# BM8L.net
KiCad netlist of a schematic drawn in EAGLE
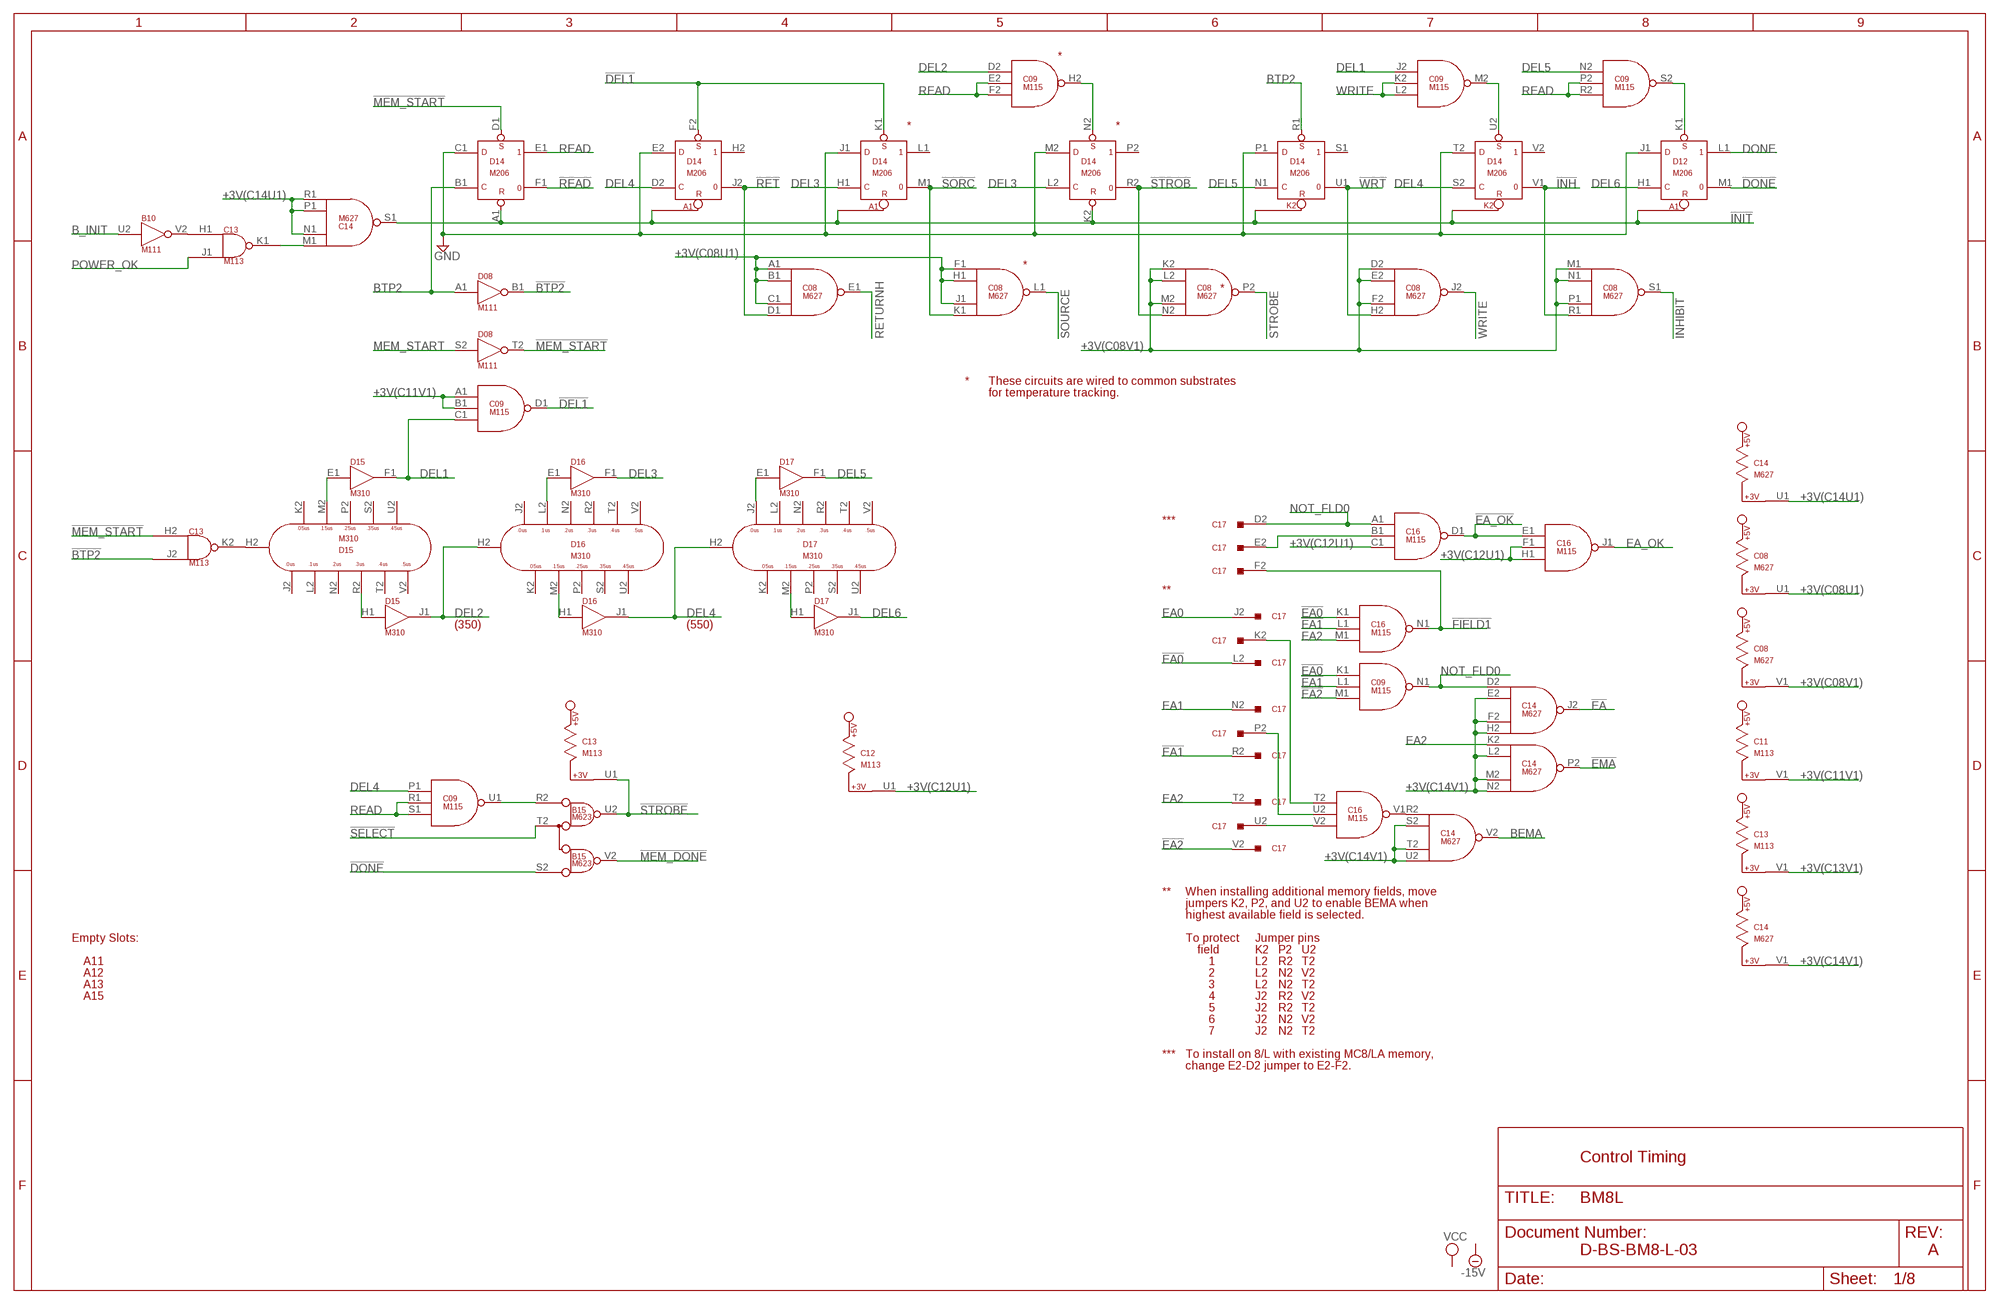
[diagram p0: schematic, sheet 1]
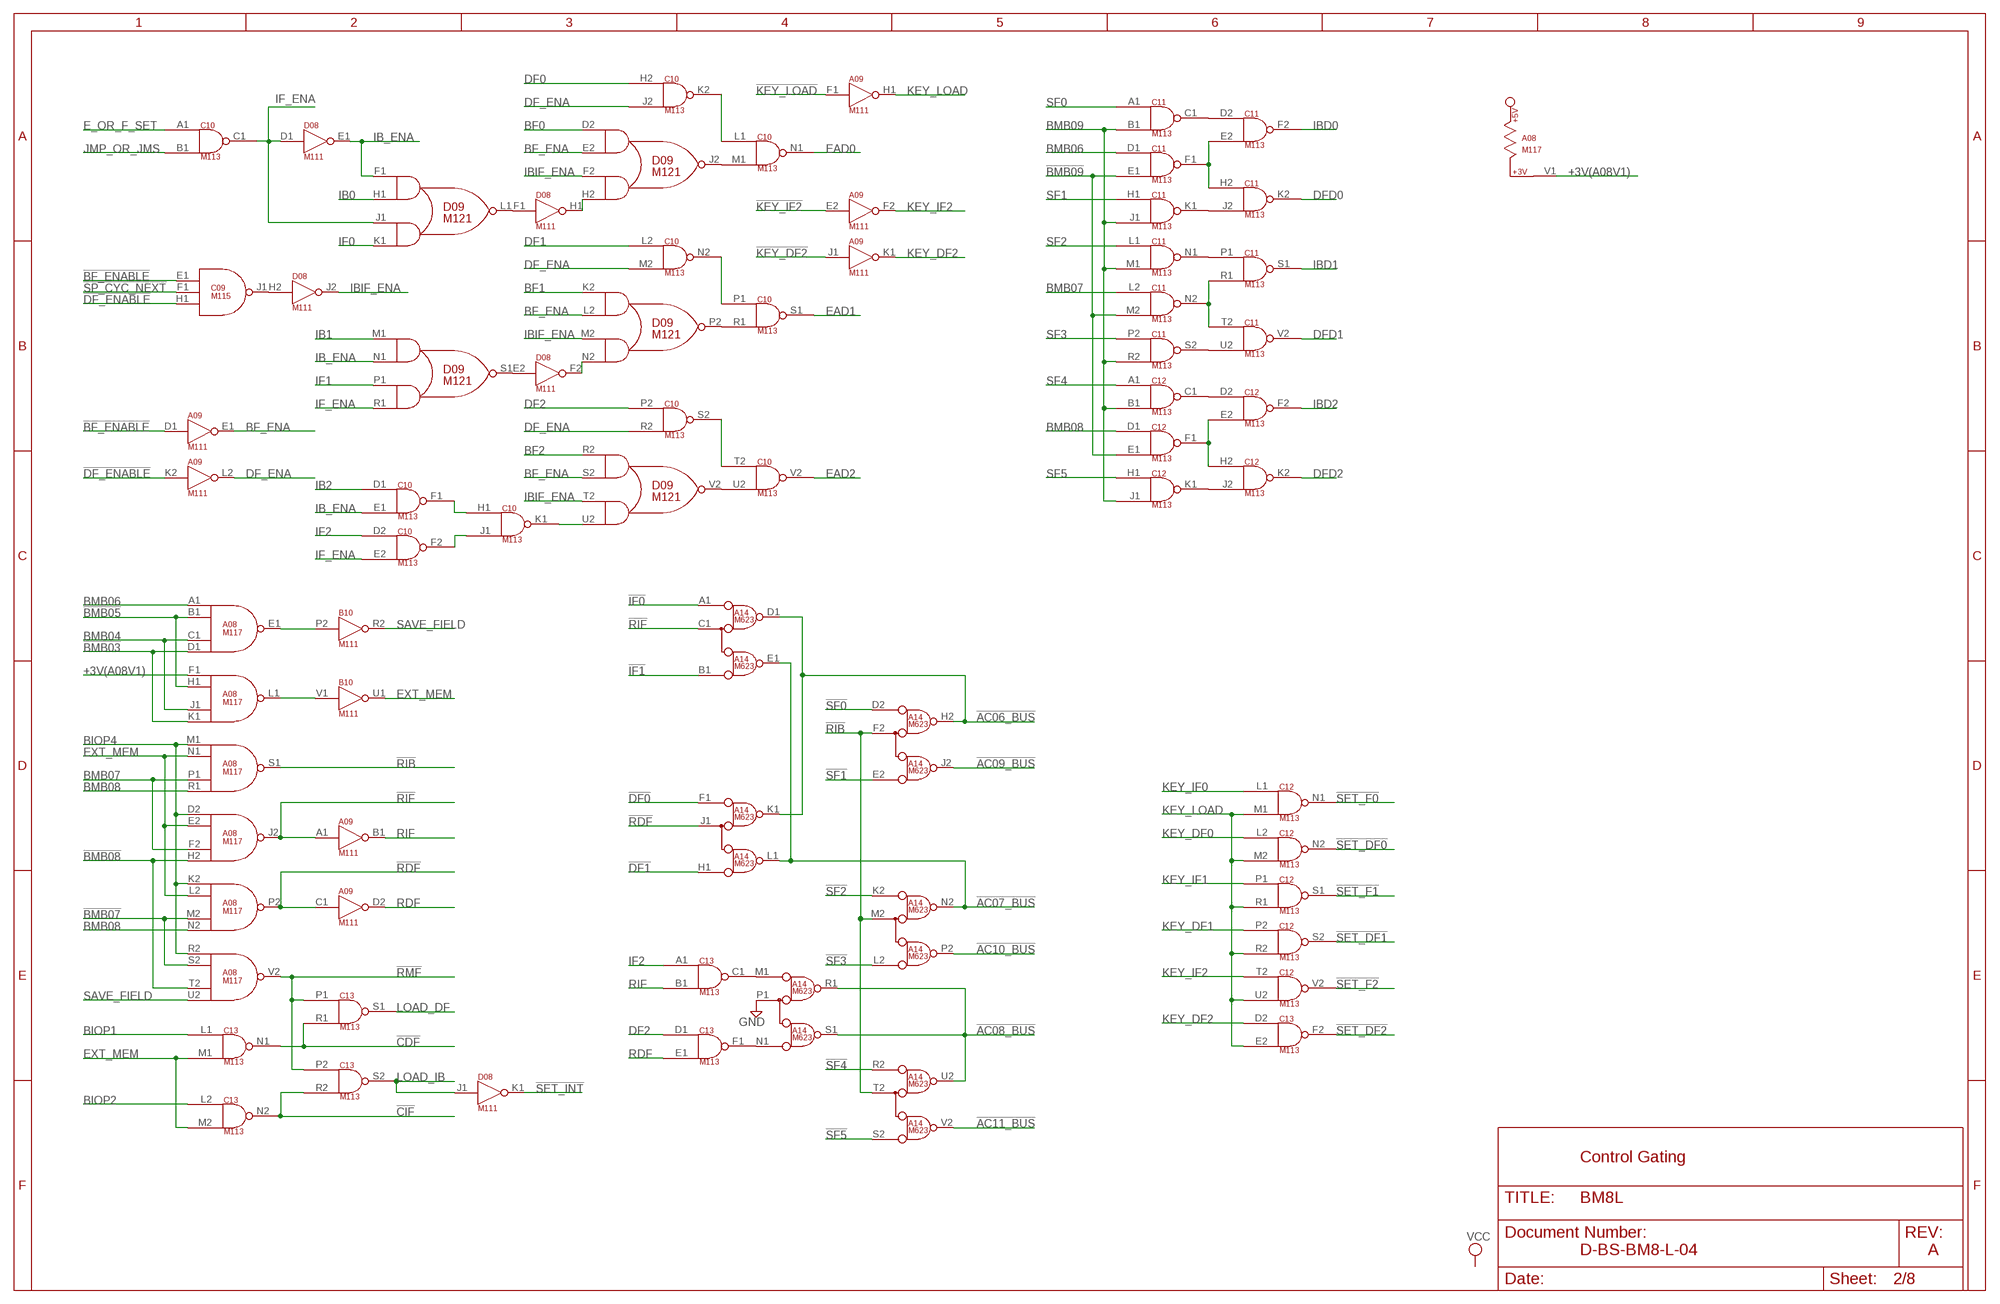
[diagram p1: schematic, sheet 2]
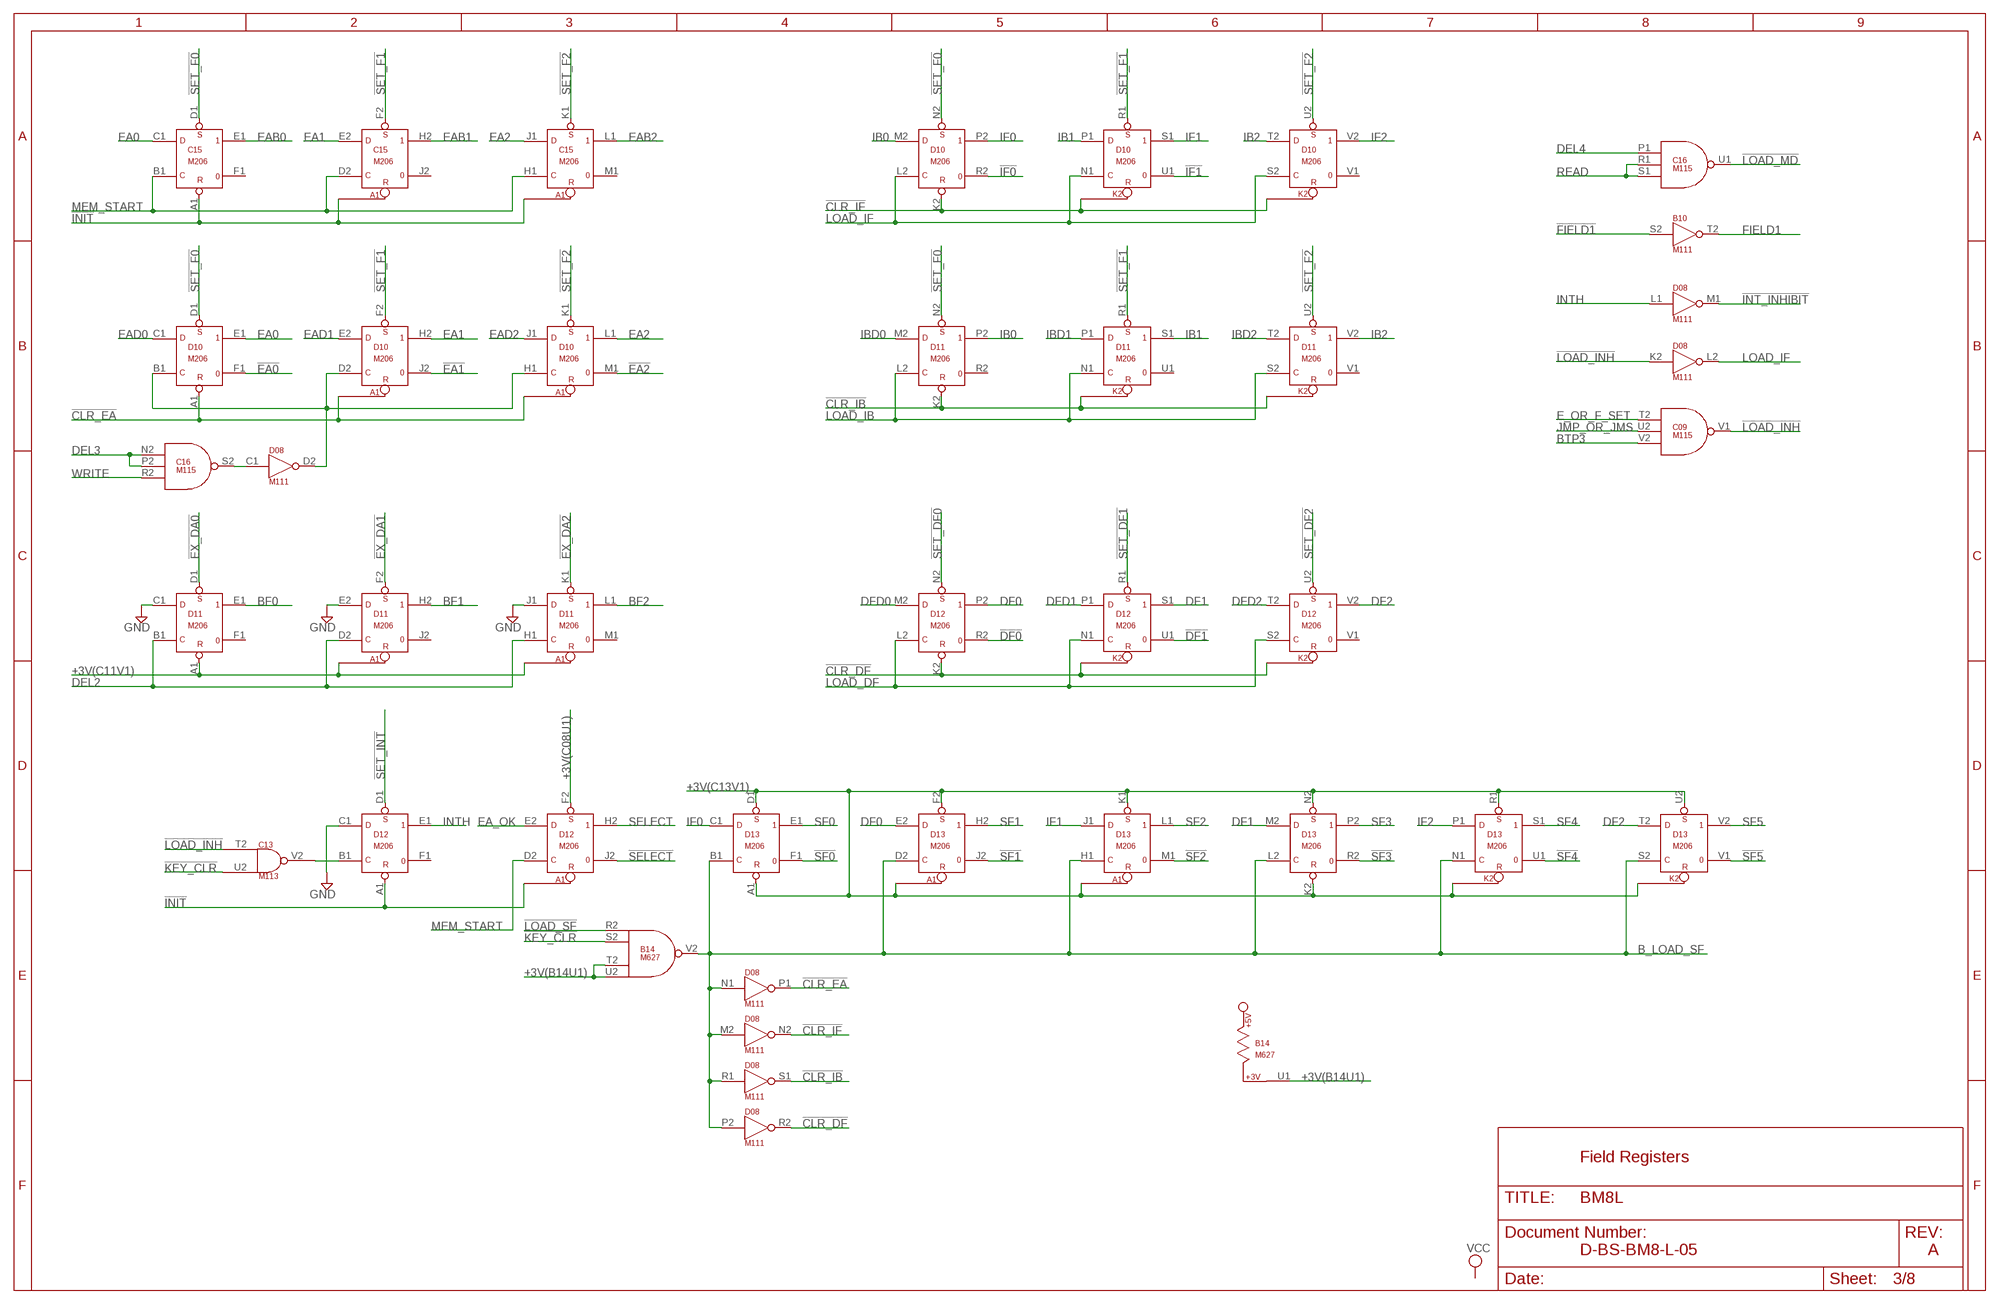
[diagram p2: schematic, sheet 3]
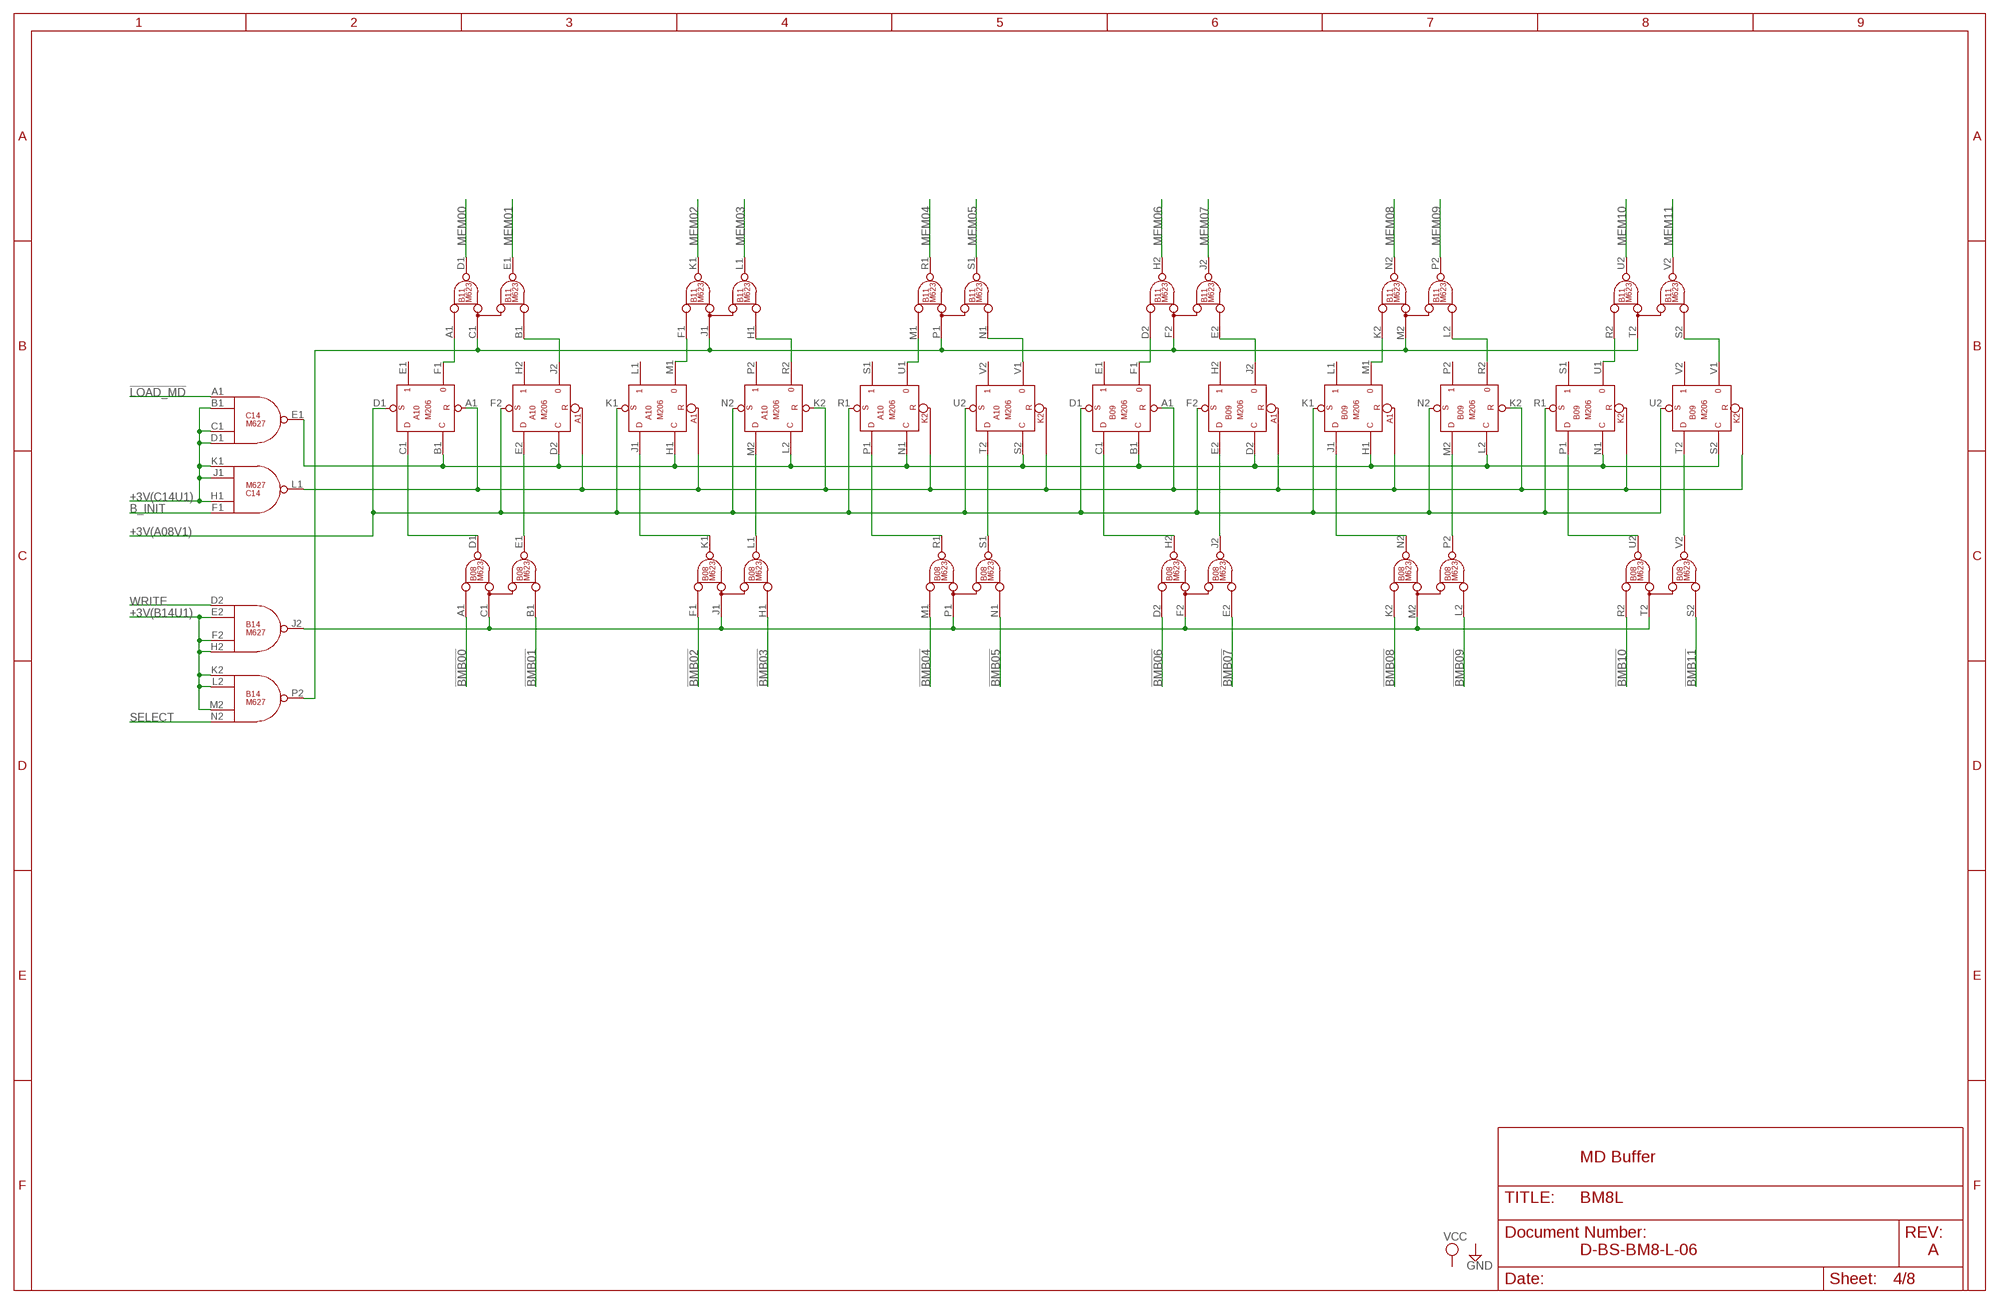
[diagram p3: schematic, sheet 4]
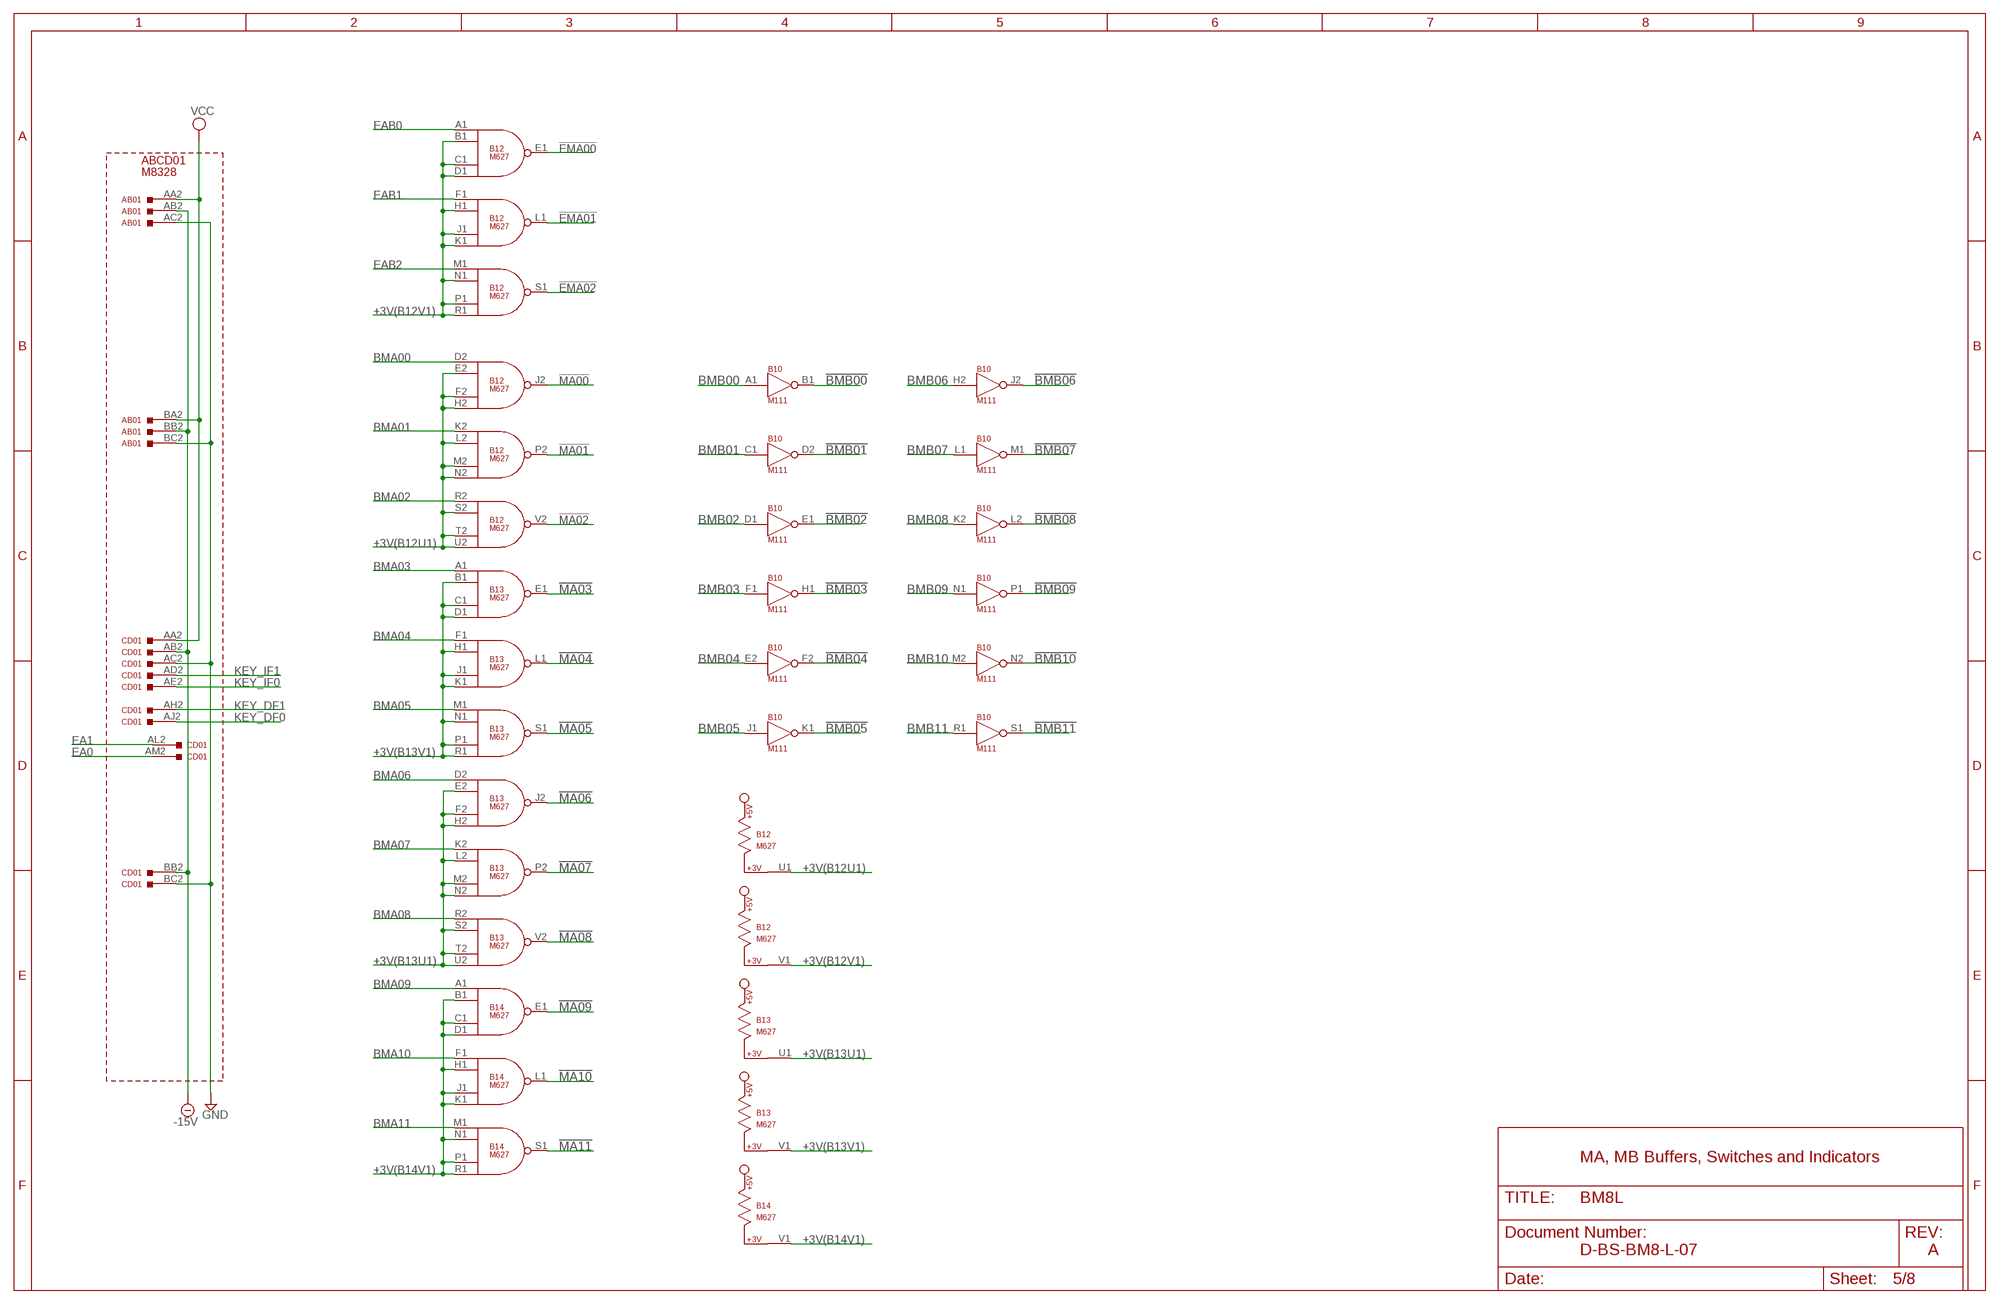
[diagram p4: schematic, sheet 5]
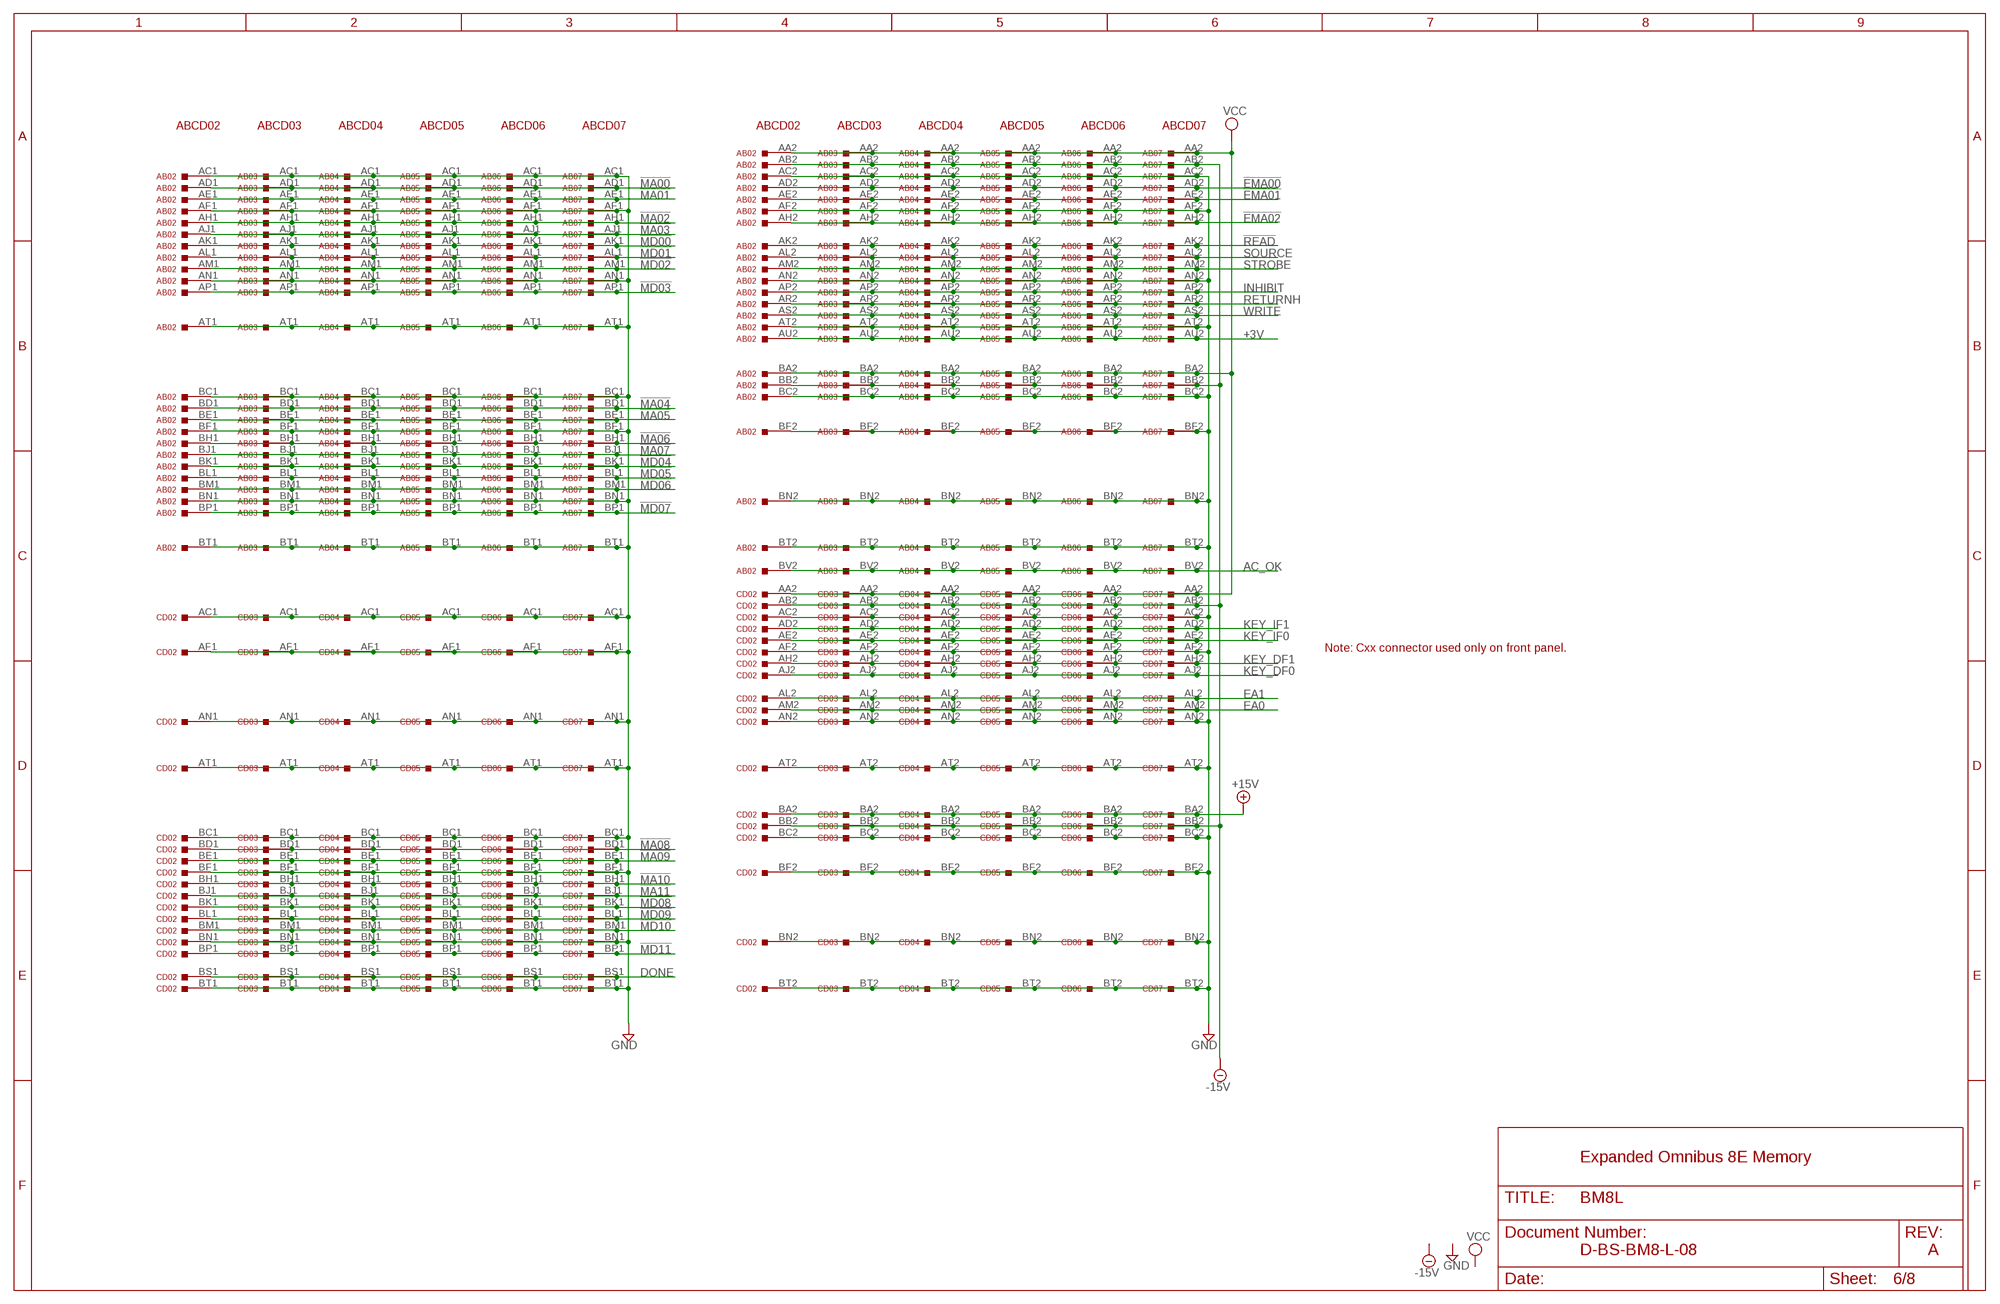
[diagram p5: schematic, sheet 6]
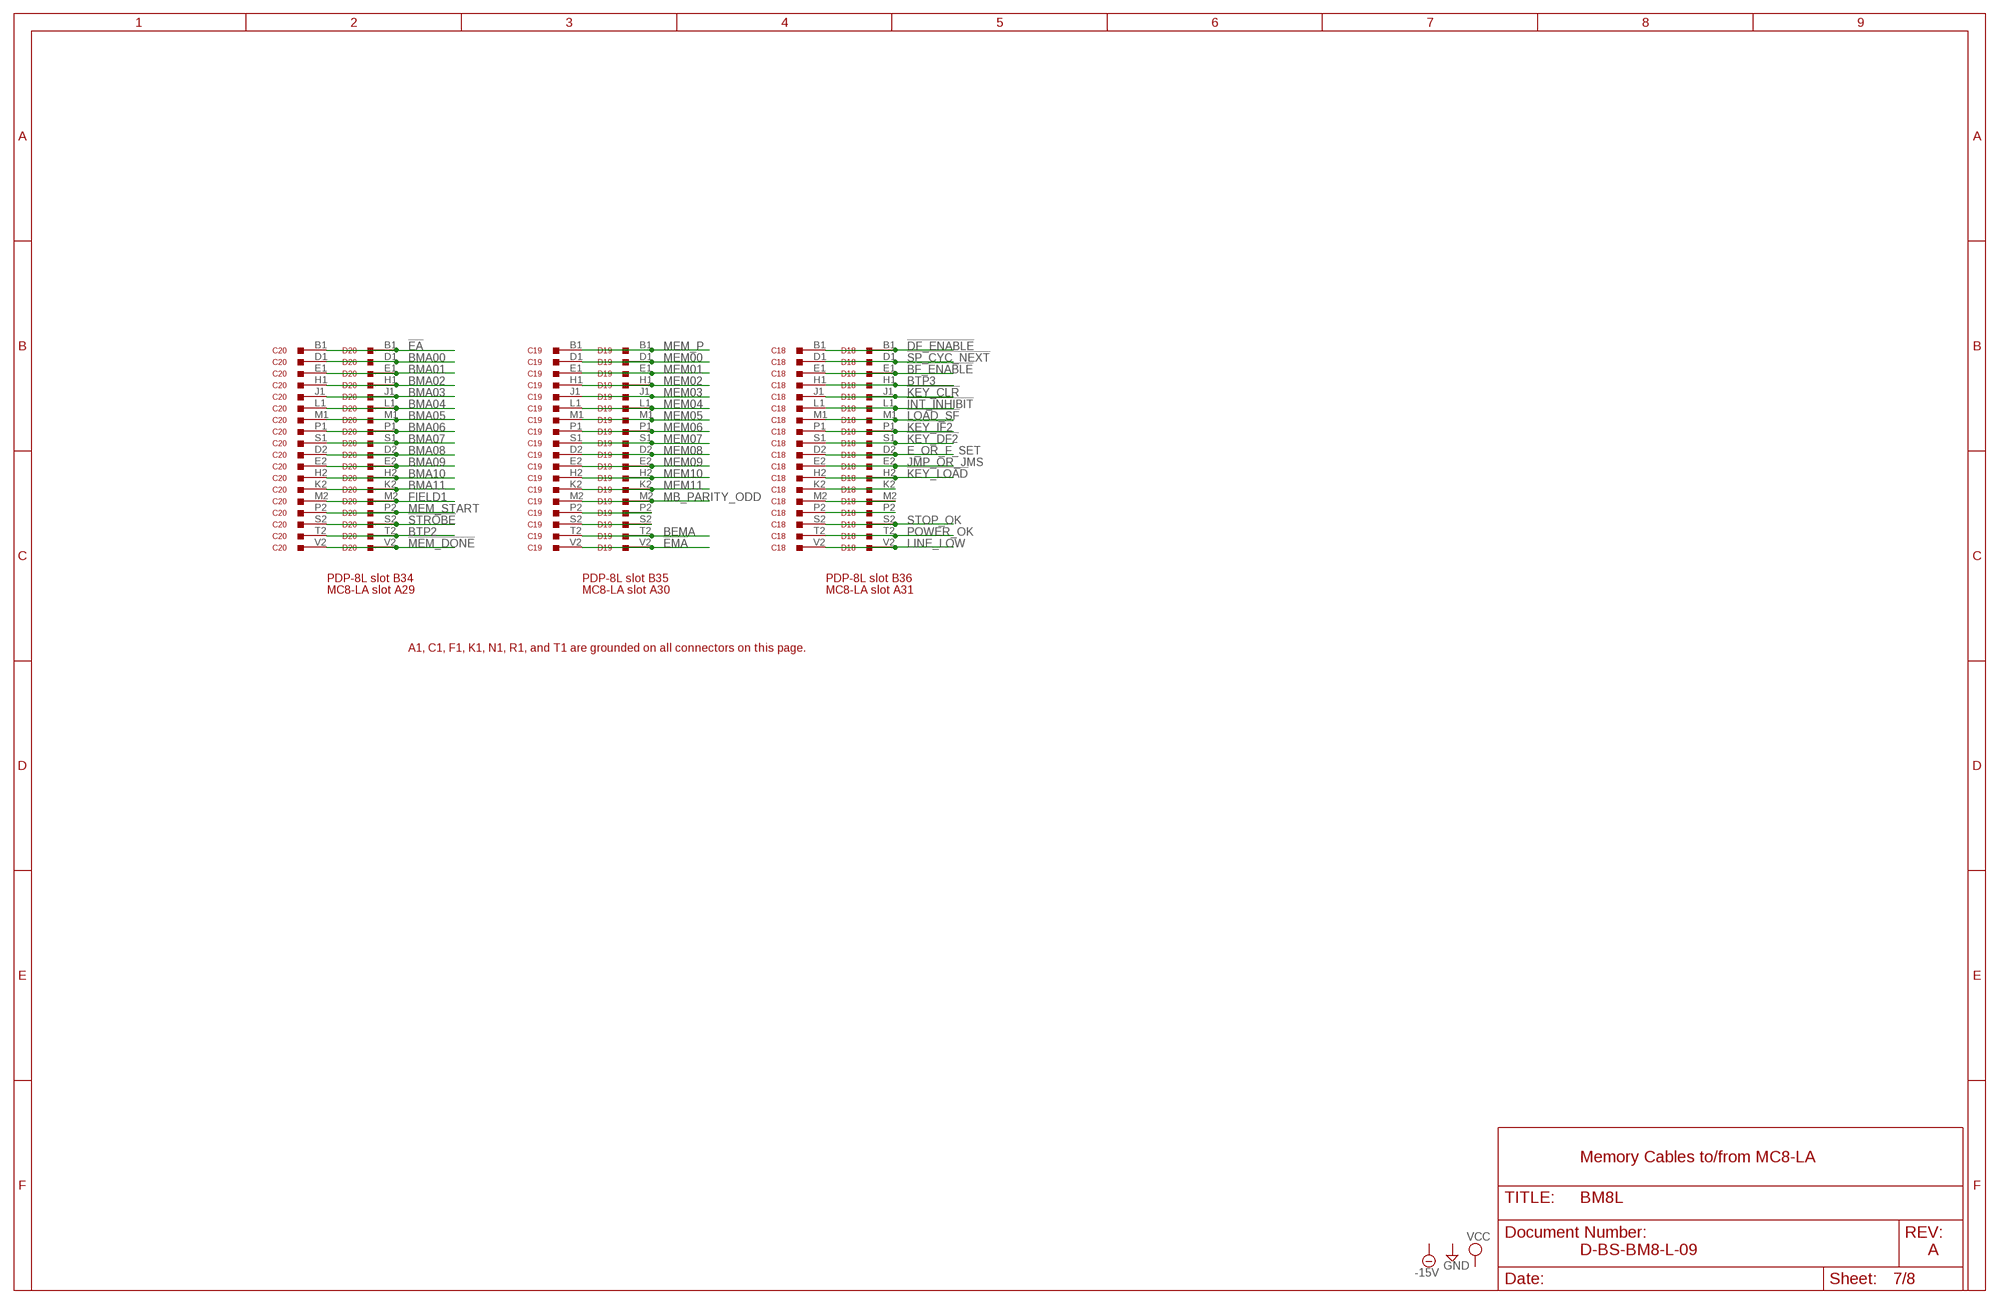
[diagram p6: schematic, sheet 7]
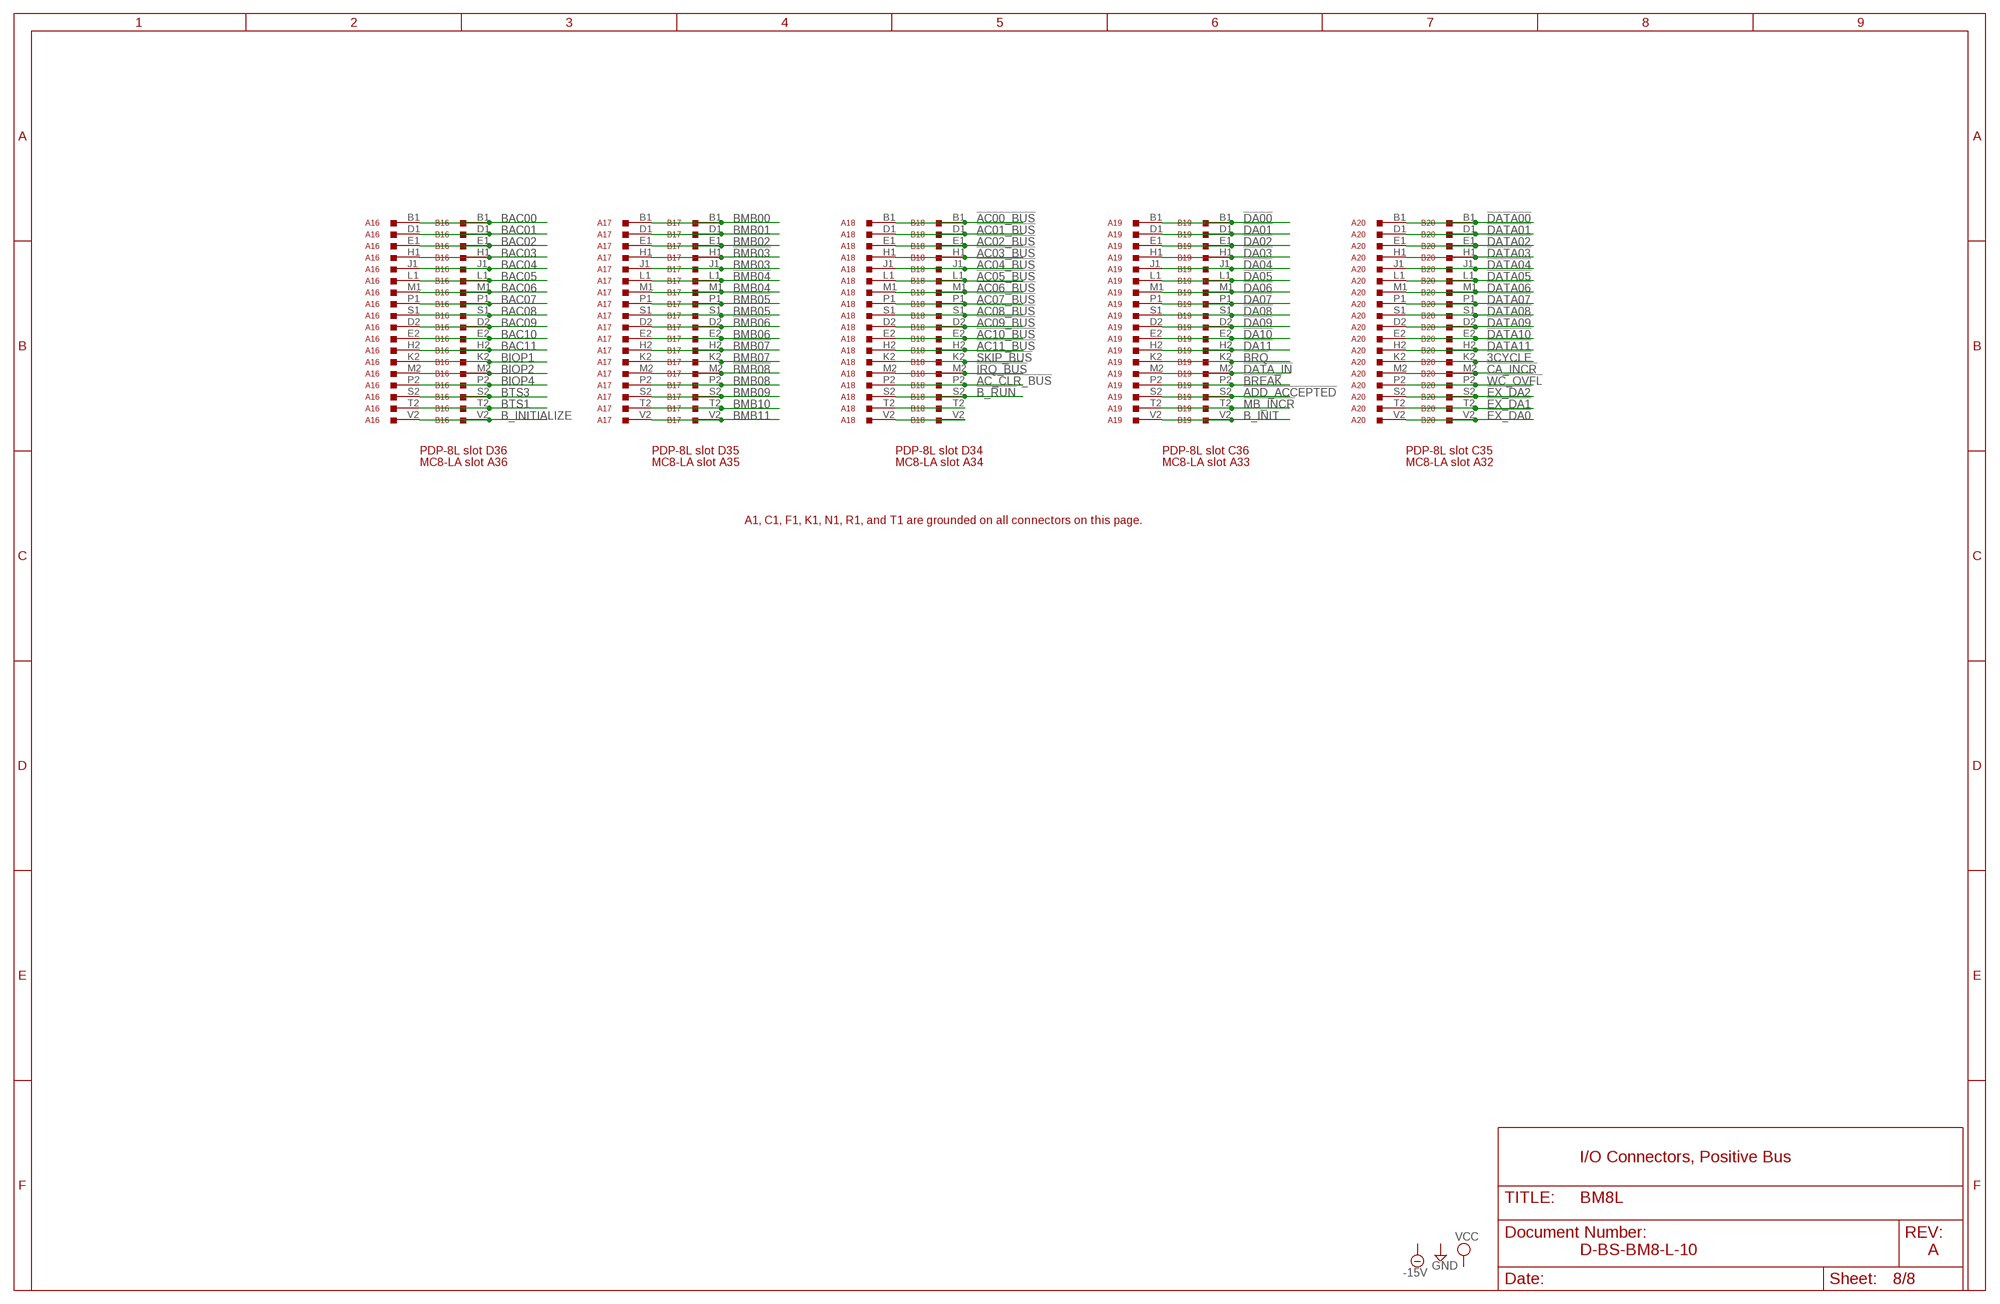
[diagram p7: schematic, sheet 8]

(export (version "E")
  (design (tool "Eeschema 10.0.6"))
  (components
    (comp (ref "B10")
      (value "M111")
      (footprint "eagle-import:H807")
      (libsource (lib "eagle-import") (part "M111"))
    )
    (comp (ref "B14")
      (value "M627")
      (footprint "eagle-import:H807")
      (libsource (lib "eagle-import") (part "M627"))
    )
    (comp (ref "C09")
      (value "M115")
      (footprint "eagle-import:H807")
      (libsource (lib "eagle-import") (part "M115"))
    )
    (comp (ref "C13")
      (value "M113")
      (footprint "eagle-import:H807")
      (libsource (lib "eagle-import") (part "M113"))
    )
    (comp (ref "C15")
      (value "M206")
      (footprint "eagle-import:H807")
      (libsource (lib "eagle-import") (part "M206X"))
    )
    (comp (ref "C16")
      (value "M115")
      (footprint "eagle-import:H807")
      (libsource (lib "eagle-import") (part "M115"))
    )
    (comp (ref "D08")
      (value "M111")
      (footprint "eagle-import:H807")
      (libsource (lib "eagle-import") (part "M111"))
    )
    (comp (ref "D10")
      (value "M206")
      (footprint "eagle-import:H807")
      (libsource (lib "eagle-import") (part "M206X"))
    )
    (comp (ref "D11")
      (value "M206")
      (footprint "eagle-import:H807")
      (libsource (lib "eagle-import") (part "M206X"))
    )
    (comp (ref "D12")
      (value "M206")
      (footprint "eagle-import:H807")
      (libsource (lib "eagle-import") (part "M206X"))
    )
    (comp (ref "D13")
      (value "M206")
      (footprint "eagle-import:H807")
      (libsource (lib "eagle-import") (part "M206X"))
    )
    (comp (ref "A16")
      (value "M903")
      (footprint "eagle-import:H807")
      (libsource (lib "eagle-import") (part "M903"))
    )
    (comp (ref "A17")
      (value "M903")
      (footprint "eagle-import:H807")
      (libsource (lib "eagle-import") (part "M903"))
    )
    (comp (ref "A18")
      (value "M903")
      (footprint "eagle-import:H807")
      (libsource (lib "eagle-import") (part "M903"))
    )
    (comp (ref "A19")
      (value "M903")
      (footprint "eagle-import:H807")
      (libsource (lib "eagle-import") (part "M903"))
    )
    (comp (ref "A20")
      (value "M903")
      (footprint "eagle-import:H807")
      (libsource (lib "eagle-import") (part "M903"))
    )
    (comp (ref "B16")
      (value "M903")
      (footprint "eagle-import:H807")
      (libsource (lib "eagle-import") (part "M903"))
    )
    (comp (ref "B17")
      (value "M903")
      (footprint "eagle-import:H807")
      (libsource (lib "eagle-import") (part "M903"))
    )
    (comp (ref "B18")
      (value "M903")
      (footprint "eagle-import:H807")
      (libsource (lib "eagle-import") (part "M903"))
    )
    (comp (ref "B19")
      (value "M903")
      (footprint "eagle-import:H807")
      (libsource (lib "eagle-import") (part "M903"))
    )
    (comp (ref "B20")
      (value "M903")
      (footprint "eagle-import:H807")
      (libsource (lib "eagle-import") (part "M903"))
    )
    (comp (ref "AB02")
      (value "M935")
      (footprint "eagle-import:H807-2")
      (libsource (lib "eagle-import") (part "W971"))
    )
    (comp (ref "AB03")
      (value "M935")
      (footprint "eagle-import:H807-2")
      (libsource (lib "eagle-import") (part "W971"))
    )
    (comp (ref "AB04")
      (value "M935")
      (footprint "eagle-import:H807-2")
      (libsource (lib "eagle-import") (part "W971"))
    )
    (comp (ref "AB05")
      (value "M935")
      (footprint "eagle-import:H807-2")
      (libsource (lib "eagle-import") (part "W971"))
    )
    (comp (ref "AB06")
      (value "M935")
      (footprint "eagle-import:H807-2")
      (libsource (lib "eagle-import") (part "W971"))
    )
    (comp (ref "AB07")
      (value "M849")
      (footprint "eagle-import:H807-2")
      (libsource (lib "eagle-import") (part "W971"))
    )
    (comp (ref "CD02")
      (value "M935")
      (footprint "eagle-import:H807-2")
      (libsource (lib "eagle-import") (part "W971"))
    )
    (comp (ref "CD03")
      (value "M935")
      (footprint "eagle-import:H807-2")
      (libsource (lib "eagle-import") (part "W971"))
    )
    (comp (ref "CD04")
      (value "M935")
      (footprint "eagle-import:H807-2")
      (libsource (lib "eagle-import") (part "W971"))
    )
    (comp (ref "CD05")
      (value "M935")
      (footprint "eagle-import:H807-2")
      (libsource (lib "eagle-import") (part "W971"))
    )
    (comp (ref "CD06")
      (value "M935")
      (footprint "eagle-import:H807-2")
      (libsource (lib "eagle-import") (part "W971"))
    )
    (comp (ref "CD07")
      (value "M849")
      (footprint "eagle-import:H807-2")
      (libsource (lib "eagle-import") (part "W971"))
    )
    (comp (ref "AB01")
      (value "M935")
      (footprint "eagle-import:H807-2")
      (libsource (lib "eagle-import") (part "W971"))
    )
    (comp (ref "B12")
      (value "M627")
      (footprint "eagle-import:H807")
      (libsource (lib "eagle-import") (part "M627"))
    )
    (comp (ref "B13")
      (value "M627")
      (footprint "eagle-import:H807")
      (libsource (lib "eagle-import") (part "M627"))
    )
    (comp (ref "CD01")
      (value "M935")
      (footprint "eagle-import:H807-2")
      (libsource (lib "eagle-import") (part "W971"))
    )
    (comp (ref "A11")
      (value "EMPTY")
      (footprint "eagle-import:H807")
      (libsource (lib "eagle-import") (part "EMPTY"))
    )
    (comp (ref "A12")
      (value "EMPTY")
      (footprint "eagle-import:H807")
      (libsource (lib "eagle-import") (part "EMPTY"))
    )
    (comp (ref "A13")
      (value "EMPTY")
      (footprint "eagle-import:H807")
      (libsource (lib "eagle-import") (part "EMPTY"))
    )
    (comp (ref "A15")
      (value "EMPTY")
      (footprint "eagle-import:H807")
      (libsource (lib "eagle-import") (part "EMPTY"))
    )
    (comp (ref "B15")
      (value "M623")
      (footprint "eagle-import:H807")
      (libsource (lib "eagle-import") (part "M623"))
    )
    (comp (ref "C08")
      (value "M627")
      (footprint "eagle-import:H807")
      (libsource (lib "eagle-import") (part "M627"))
    )
    (comp (ref "C11")
      (value "M113")
      (footprint "eagle-import:H807")
      (libsource (lib "eagle-import") (part "M113"))
    )
    (comp (ref "C12")
      (value "M113")
      (footprint "eagle-import:H807")
      (libsource (lib "eagle-import") (part "M113"))
    )
    (comp (ref "C14")
      (value "M627")
      (footprint "eagle-import:H807")
      (libsource (lib "eagle-import") (part "M627"))
    )
    (comp (ref "C17")
      (value "M990")
      (footprint "eagle-import:H807")
      (libsource (lib "eagle-import") (part "W023"))
    )
    (comp (ref "D14")
      (value "M206")
      (footprint "eagle-import:H807")
      (libsource (lib "eagle-import") (part "M206X"))
    )
    (comp (ref "D15")
      (value "M310")
      (footprint "eagle-import:H807")
      (libsource (lib "eagle-import") (part "M310"))
    )
    (comp (ref "D16")
      (value "M310")
      (footprint "eagle-import:H807")
      (libsource (lib "eagle-import") (part "M310"))
    )
    (comp (ref "D17")
      (value "M310")
      (footprint "eagle-import:H807")
      (libsource (lib "eagle-import") (part "M310"))
    )
    (comp (ref "C18")
      (value "M903")
      (footprint "eagle-import:H807")
      (libsource (lib "eagle-import") (part "M903"))
    )
    (comp (ref "C19")
      (value "M903")
      (footprint "eagle-import:H807")
      (libsource (lib "eagle-import") (part "M903"))
    )
    (comp (ref "C20")
      (value "M903")
      (footprint "eagle-import:H807")
      (libsource (lib "eagle-import") (part "M903"))
    )
    (comp (ref "D18")
      (value "M903")
      (footprint "eagle-import:H807")
      (libsource (lib "eagle-import") (part "M903"))
    )
    (comp (ref "D19")
      (value "M903")
      (footprint "eagle-import:H807")
      (libsource (lib "eagle-import") (part "M903"))
    )
    (comp (ref "D20")
      (value "M903")
      (footprint "eagle-import:H807")
      (libsource (lib "eagle-import") (part "M903"))
    )
    (comp (ref "A10")
      (value "M206")
      (footprint "eagle-import:H807")
      (libsource (lib "eagle-import") (part "M206X"))
    )
    (comp (ref "B08")
      (value "M623")
      (footprint "eagle-import:H807")
      (libsource (lib "eagle-import") (part "M623"))
    )
    (comp (ref "B09")
      (value "M206")
      (footprint "eagle-import:H807")
      (libsource (lib "eagle-import") (part "M206X"))
    )
    (comp (ref "B11")
      (value "M623")
      (footprint "eagle-import:H807")
      (libsource (lib "eagle-import") (part "M623"))
    )
    (comp (ref "A08")
      (value "M117")
      (footprint "eagle-import:H807")
      (libsource (lib "eagle-import") (part "M117"))
    )
    (comp (ref "A09")
      (value "M111")
      (footprint "eagle-import:H807")
      (libsource (lib "eagle-import") (part "M111"))
    )
    (comp (ref "A14")
      (value "M623")
      (footprint "eagle-import:H807")
      (libsource (lib "eagle-import") (part "M623"))
    )
    (comp (ref "C10")
      (value "M113")
      (footprint "eagle-import:H807")
      (libsource (lib "eagle-import") (part "M113"))
    )
    (comp (ref "D09")
      (value "M121")
      (footprint "eagle-import:H807")
      (libsource (lib "eagle-import") (part "M121"))
    )
  )
  (nets
    (net (code "1") (name "+3V") (class "Default")
      (node (ref "AB02") (pin "AU2") (pinfunction "P$2_AU2") (pintype "bidirectional"))
      (node (ref "AB03") (pin "AU2") (pinfunction "P$2_AU2") (pintype "bidirectional"))
      (node (ref "AB04") (pin "AU2") (pinfunction "P$2_AU2") (pintype "bidirectional"))
      (node (ref "AB05") (pin "AU2") (pinfunction "P$2_AU2") (pintype "bidirectional"))
      (node (ref "AB06") (pin "AU2") (pinfunction "P$2_AU2") (pintype "bidirectional"))
      (node (ref "AB07") (pin "AU2") (pinfunction "P$2_AU2") (pintype "bidirectional"))
    )
    (net (code "2") (name "+3V(A08V1)") (class "Default")
      (node (ref "A08") (pin "F1") (pinfunction "IN1_F1") (pintype "input"))
      (node (ref "A08") (pin "V1") (pinfunction "P$1_V1") (pintype "passive"))
      (node (ref "A10") (pin "D1") (pinfunction "S_D1") (pintype "input"))
      (node (ref "A10") (pin "F2") (pinfunction "S_F2") (pintype "input"))
      (node (ref "A10") (pin "K1") (pinfunction "S_K1") (pintype "input"))
      (node (ref "A10") (pin "N2") (pinfunction "S_N2") (pintype "input"))
      (node (ref "A10") (pin "R1") (pinfunction "S_R1") (pintype "input"))
      (node (ref "A10") (pin "U2") (pinfunction "S_U2") (pintype "input"))
      (node (ref "B09") (pin "D1") (pinfunction "S_D1") (pintype "input"))
      (node (ref "B09") (pin "F2") (pinfunction "S_F2") (pintype "input"))
      (node (ref "B09") (pin "K1") (pinfunction "S_K1") (pintype "input"))
      (node (ref "B09") (pin "N2") (pinfunction "S_N2") (pintype "input"))
      (node (ref "B09") (pin "R1") (pinfunction "S_R1") (pintype "input"))
      (node (ref "B09") (pin "U2") (pinfunction "S_U2") (pintype "input"))
    )
    (net (code "3") (name "+3V(B12U1)") (class "Default")
      (node (ref "B12") (pin "E2") (pinfunction "IN2_E2") (pintype "input"))
      (node (ref "B12") (pin "F2") (pinfunction "IN3_F2") (pintype "input"))
      (node (ref "B12") (pin "H2") (pinfunction "IN4_H2") (pintype "input"))
      (node (ref "B12") (pin "L2") (pinfunction "IN2_L2") (pintype "input"))
      (node (ref "B12") (pin "M2") (pinfunction "IN3_M2") (pintype "input"))
      (node (ref "B12") (pin "N2") (pinfunction "IN4_N2") (pintype "input"))
      (node (ref "B12") (pin "S2") (pinfunction "IN2_S2") (pintype "input"))
      (node (ref "B12") (pin "T2") (pinfunction "IN3_T2") (pintype "input"))
      (node (ref "B12") (pin "U1") (pinfunction "P$1_U1") (pintype "passive"))
      (node (ref "B12") (pin "U2") (pinfunction "IN4_U2") (pintype "input"))
    )
    (net (code "4") (name "+3V(B12V1)") (class "Default")
      (node (ref "B12") (pin "B1") (pinfunction "IN2_B1") (pintype "input"))
      (node (ref "B12") (pin "C1") (pinfunction "IN3_C1") (pintype "input"))
      (node (ref "B12") (pin "D1") (pinfunction "IN4_D1") (pintype "input"))
      (node (ref "B12") (pin "H1") (pinfunction "IN2_H1") (pintype "input"))
      (node (ref "B12") (pin "J1") (pinfunction "IN3_J1") (pintype "input"))
      (node (ref "B12") (pin "K1") (pinfunction "IN4_K1") (pintype "input"))
      (node (ref "B12") (pin "N1") (pinfunction "IN2_N1") (pintype "input"))
      (node (ref "B12") (pin "P1") (pinfunction "IN3_P1") (pintype "input"))
      (node (ref "B12") (pin "R1") (pinfunction "IN4_R1") (pintype "input"))
      (node (ref "B12") (pin "V1") (pinfunction "P$1_V1") (pintype "passive"))
    )
    (net (code "5") (name "+3V(B13U1)") (class "Default")
      (node (ref "B13") (pin "E2") (pinfunction "IN2_E2") (pintype "input"))
      (node (ref "B13") (pin "F2") (pinfunction "IN3_F2") (pintype "input"))
      (node (ref "B13") (pin "H2") (pinfunction "IN4_H2") (pintype "input"))
      (node (ref "B13") (pin "L2") (pinfunction "IN2_L2") (pintype "input"))
      (node (ref "B13") (pin "M2") (pinfunction "IN3_M2") (pintype "input"))
      (node (ref "B13") (pin "N2") (pinfunction "IN4_N2") (pintype "input"))
      (node (ref "B13") (pin "S2") (pinfunction "IN2_S2") (pintype "input"))
      (node (ref "B13") (pin "T2") (pinfunction "IN3_T2") (pintype "input"))
      (node (ref "B13") (pin "U1") (pinfunction "P$1_U1") (pintype "passive"))
      (node (ref "B13") (pin "U2") (pinfunction "IN4_U2") (pintype "input"))
    )
    (net (code "6") (name "+3V(B13V1)") (class "Default")
      (node (ref "B13") (pin "B1") (pinfunction "IN2_B1") (pintype "input"))
      (node (ref "B13") (pin "C1") (pinfunction "IN3_C1") (pintype "input"))
      (node (ref "B13") (pin "D1") (pinfunction "IN4_D1") (pintype "input"))
      (node (ref "B13") (pin "H1") (pinfunction "IN2_H1") (pintype "input"))
      (node (ref "B13") (pin "J1") (pinfunction "IN3_J1") (pintype "input"))
      (node (ref "B13") (pin "K1") (pinfunction "IN4_K1") (pintype "input"))
      (node (ref "B13") (pin "N1") (pinfunction "IN2_N1") (pintype "input"))
      (node (ref "B13") (pin "P1") (pinfunction "IN3_P1") (pintype "input"))
      (node (ref "B13") (pin "R1") (pinfunction "IN4_R1") (pintype "input"))
      (node (ref "B13") (pin "V1") (pinfunction "P$1_V1") (pintype "passive"))
    )
    (net (code "7") (name "+3V(B14U1)") (class "Default")
      (node (ref "B14") (pin "E2") (pinfunction "IN2_E2") (pintype "input"))
      (node (ref "B14") (pin "F2") (pinfunction "IN3_F2") (pintype "input"))
      (node (ref "B14") (pin "H2") (pinfunction "IN4_H2") (pintype "input"))
      (node (ref "B14") (pin "K2") (pinfunction "IN1_K2") (pintype "input"))
      (node (ref "B14") (pin "L2") (pinfunction "IN2_L2") (pintype "input"))
      (node (ref "B14") (pin "M2") (pinfunction "IN3_M2") (pintype "input"))
      (node (ref "B14") (pin "T2") (pinfunction "IN3_T2") (pintype "input"))
      (node (ref "B14") (pin "U1") (pinfunction "P$1_U1") (pintype "passive"))
      (node (ref "B14") (pin "U2") (pinfunction "IN4_U2") (pintype "input"))
    )
    (net (code "8") (name "+3V(B14V1)") (class "Default")
      (node (ref "B14") (pin "B1") (pinfunction "IN2_B1") (pintype "input"))
      (node (ref "B14") (pin "C1") (pinfunction "IN3_C1") (pintype "input"))
      (node (ref "B14") (pin "D1") (pinfunction "IN4_D1") (pintype "input"))
      (node (ref "B14") (pin "H1") (pinfunction "IN2_H1") (pintype "input"))
      (node (ref "B14") (pin "J1") (pinfunction "IN3_J1") (pintype "input"))
      (node (ref "B14") (pin "K1") (pinfunction "IN4_K1") (pintype "input"))
      (node (ref "B14") (pin "N1") (pinfunction "IN2_N1") (pintype "input"))
      (node (ref "B14") (pin "P1") (pinfunction "IN3_P1") (pintype "input"))
      (node (ref "B14") (pin "R1") (pinfunction "IN4_R1") (pintype "input"))
      (node (ref "B14") (pin "V1") (pinfunction "P$1_V1") (pintype "passive"))
    )
    (net (code "9") (name "+3V(C08U1)") (class "Default")
      (node (ref "C08") (pin "A1") (pinfunction "IN1_A1") (pintype "input"))
      (node (ref "C08") (pin "B1") (pinfunction "IN2_B1") (pintype "input"))
      (node (ref "C08") (pin "C1") (pinfunction "IN3_C1") (pintype "input"))
      (node (ref "C08") (pin "F1") (pinfunction "IN1_F1") (pintype "input"))
      (node (ref "C08") (pin "H1") (pinfunction "IN2_H1") (pintype "input"))
      (node (ref "C08") (pin "J1") (pinfunction "IN3_J1") (pintype "input"))
      (node (ref "C08") (pin "U1") (pinfunction "P$1_U1") (pintype "passive"))
      (node (ref "D12") (pin "F2") (pinfunction "S_F2") (pintype "input"))
    )
    (net (code "10") (name "+3V(C08V1)") (class "Default")
      (node (ref "C08") (pin "D2") (pinfunction "IN1_D2") (pintype "input"))
      (node (ref "C08") (pin "E2") (pinfunction "IN2_E2") (pintype "input"))
      (node (ref "C08") (pin "F2") (pinfunction "IN3_F2") (pintype "input"))
      (node (ref "C08") (pin "K2") (pinfunction "IN1_K2") (pintype "input"))
      (node (ref "C08") (pin "L2") (pinfunction "IN2_L2") (pintype "input"))
      (node (ref "C08") (pin "M1") (pinfunction "IN1_M1") (pintype "input"))
      (node (ref "C08") (pin "M2") (pinfunction "IN3_M2") (pintype "input"))
      (node (ref "C08") (pin "N1") (pinfunction "IN2_N1") (pintype "input"))
      (node (ref "C08") (pin "P1") (pinfunction "IN3_P1") (pintype "input"))
      (node (ref "C08") (pin "V1") (pinfunction "P$1_V1") (pintype "passive"))
    )
    (net (code "11") (name "+3V(C11V1)") (class "Default")
      (node (ref "C09") (pin "A1") (pinfunction "IN1_A1") (pintype "input"))
      (node (ref "C09") (pin "B1") (pinfunction "IN2_B1") (pintype "input"))
      (node (ref "C11") (pin "V1") (pinfunction "P$1_V1") (pintype "passive"))
      (node (ref "D11") (pin "A1") (pinfunction "R_A1") (pintype "input"))
    )
    (net (code "12") (name "+3V(C12U1)") (class "Default")
      (node (ref "C12") (pin "U1") (pinfunction "P$1_U1") (pintype "passive"))
      (node (ref "C16") (pin "C1") (pinfunction "IN3_C1") (pintype "input"))
      (node (ref "C16") (pin "F1") (pinfunction "IN2_F1") (pintype "input"))
      (node (ref "C16") (pin "H1") (pinfunction "IN3_H1") (pintype "input"))
    )
    (net (code "13") (name "+3V(C13V1)") (class "Default")
      (node (ref "C13") (pin "V1") (pinfunction "P$1_V1") (pintype "passive"))
      (node (ref "D13") (pin "A1") (pinfunction "R_A1") (pintype "input"))
      (node (ref "D13") (pin "D1") (pinfunction "S_D1") (pintype "input"))
      (node (ref "D13") (pin "F2") (pinfunction "S_F2") (pintype "input"))
      (node (ref "D13") (pin "K1") (pinfunction "S_K1") (pintype "input"))
      (node (ref "D13") (pin "K2") (pinfunction "R_K2") (pintype "input"))
      (node (ref "D13") (pin "N2") (pinfunction "S_N2") (pintype "input"))
      (node (ref "D13") (pin "R1") (pinfunction "S_R1") (pintype "input"))
      (node (ref "D13") (pin "U2") (pinfunction "S_U2") (pintype "input"))
    )
    (net (code "14") (name "+3V(C14U1)") (class "Default")
      (node (ref "C14") (pin "B1") (pinfunction "IN2_B1") (pintype "input"))
      (node (ref "C14") (pin "C1") (pinfunction "IN3_C1") (pintype "input"))
      (node (ref "C14") (pin "D1") (pinfunction "IN4_D1") (pintype "input"))
      (node (ref "C14") (pin "H1") (pinfunction "IN2_H1") (pintype "input"))
      (node (ref "C14") (pin "J1") (pinfunction "IN3_J1") (pintype "input"))
      (node (ref "C14") (pin "K1") (pinfunction "IN4_K1") (pintype "input"))
      (node (ref "C14") (pin "N1") (pinfunction "IN2_N1") (pintype "input"))
      (node (ref "C14") (pin "P1") (pinfunction "IN3_P1") (pintype "input"))
      (node (ref "C14") (pin "R1") (pinfunction "IN4_R1") (pintype "input"))
      (node (ref "C14") (pin "U1") (pinfunction "P$1_U1") (pintype "passive"))
    )
    (net (code "15") (name "+3V(C14V1)") (class "Default")
      (node (ref "C14") (pin "E2") (pinfunction "IN2_E2") (pintype "input"))
      (node (ref "C14") (pin "F2") (pinfunction "IN3_F2") (pintype "input"))
      (node (ref "C14") (pin "H2") (pinfunction "IN4_H2") (pintype "input"))
      (node (ref "C14") (pin "L2") (pinfunction "IN2_L2") (pintype "input"))
      (node (ref "C14") (pin "M2") (pinfunction "IN3_M2") (pintype "input"))
      (node (ref "C14") (pin "N2") (pinfunction "IN4_N2") (pintype "input"))
      (node (ref "C14") (pin "S2") (pinfunction "IN2_S2") (pintype "input"))
      (node (ref "C14") (pin "T2") (pinfunction "IN3_T2") (pintype "input"))
      (node (ref "C14") (pin "U2") (pinfunction "IN4_U2") (pintype "input"))
      (node (ref "C14") (pin "V1") (pinfunction "P$1_V1") (pintype "passive"))
    )
    (net (code "16") (name "+15V") (class "Default")
      (node (ref "CD02") (pin "BA2") (pinfunction "P$2_BA2") (pintype "bidirectional"))
      (node (ref "CD03") (pin "BA2") (pinfunction "P$2_BA2") (pintype "bidirectional"))
      (node (ref "CD04") (pin "BA2") (pinfunction "P$2_BA2") (pintype "bidirectional"))
      (node (ref "CD05") (pin "BA2") (pinfunction "P$2_BA2") (pintype "bidirectional"))
      (node (ref "CD06") (pin "BA2") (pinfunction "P$2_BA2") (pintype "bidirectional"))
      (node (ref "CD07") (pin "BA2") (pinfunction "P$2_BA2") (pintype "bidirectional"))
    )
    (net (code "17") (name "-15V") (class "Default")
      (node (ref "AB01") (pin "AB2") (pinfunction "P$2_AB2") (pintype "bidirectional"))
      (node (ref "AB01") (pin "BB2") (pinfunction "P$2_BB2") (pintype "bidirectional"))
      (node (ref "AB02") (pin "AB2") (pinfunction "P$2_AB2") (pintype "bidirectional"))
      (node (ref "AB02") (pin "BB2") (pinfunction "P$2_BB2") (pintype "bidirectional"))
      (node (ref "AB03") (pin "AB2") (pinfunction "P$2_AB2") (pintype "bidirectional"))
      (node (ref "AB03") (pin "BB2") (pinfunction "P$2_BB2") (pintype "bidirectional"))
      (node (ref "AB04") (pin "AB2") (pinfunction "P$2_AB2") (pintype "bidirectional"))
      (node (ref "AB04") (pin "BB2") (pinfunction "P$2_BB2") (pintype "bidirectional"))
      (node (ref "AB05") (pin "AB2") (pinfunction "P$2_AB2") (pintype "bidirectional"))
      (node (ref "AB05") (pin "BB2") (pinfunction "P$2_BB2") (pintype "bidirectional"))
      (node (ref "AB06") (pin "AB2") (pinfunction "P$2_AB2") (pintype "bidirectional"))
      (node (ref "AB06") (pin "BB2") (pinfunction "P$2_BB2") (pintype "bidirectional"))
      (node (ref "AB07") (pin "AB2") (pinfunction "P$2_AB2") (pintype "bidirectional"))
      (node (ref "AB07") (pin "BB2") (pinfunction "P$2_BB2") (pintype "bidirectional"))
      (node (ref "CD01") (pin "AB2") (pinfunction "P$2_AB2") (pintype "bidirectional"))
      (node (ref "CD01") (pin "BB2") (pinfunction "P$2_BB2") (pintype "bidirectional"))
      (node (ref "CD02") (pin "AB2") (pinfunction "P$2_AB2") (pintype "bidirectional"))
      (node (ref "CD02") (pin "BB2") (pinfunction "P$2_BB2") (pintype "bidirectional"))
      (node (ref "CD03") (pin "AB2") (pinfunction "P$2_AB2") (pintype "bidirectional"))
      (node (ref "CD03") (pin "BB2") (pinfunction "P$2_BB2") (pintype "bidirectional"))
      (node (ref "CD04") (pin "AB2") (pinfunction "P$2_AB2") (pintype "bidirectional"))
      (node (ref "CD04") (pin "BB2") (pinfunction "P$2_BB2") (pintype "bidirectional"))
      (node (ref "CD05") (pin "AB2") (pinfunction "P$2_AB2") (pintype "bidirectional"))
      (node (ref "CD05") (pin "BB2") (pinfunction "P$2_BB2") (pintype "bidirectional"))
      (node (ref "CD06") (pin "AB2") (pinfunction "P$2_AB2") (pintype "bidirectional"))
      (node (ref "CD06") (pin "BB2") (pinfunction "P$2_BB2") (pintype "bidirectional"))
      (node (ref "CD07") (pin "AB2") (pinfunction "P$2_AB2") (pintype "bidirectional"))
      (node (ref "CD07") (pin "BB2") (pinfunction "P$2_BB2") (pintype "bidirectional"))
    )
    (net (code "18") (name "AC_OK") (class "Default")
      (node (ref "AB02") (pin "BV2") (pinfunction "P$2_BV2") (pintype "bidirectional"))
      (node (ref "AB03") (pin "BV2") (pinfunction "P$2_BV2") (pintype "bidirectional"))
      (node (ref "AB04") (pin "BV2") (pinfunction "P$2_BV2") (pintype "bidirectional"))
      (node (ref "AB05") (pin "BV2") (pinfunction "P$2_BV2") (pintype "bidirectional"))
      (node (ref "AB06") (pin "BV2") (pinfunction "P$2_BV2") (pintype "bidirectional"))
      (node (ref "AB07") (pin "BV2") (pinfunction "P$2_BV2") (pintype "bidirectional"))
    )
    (net (code "19") (name "BAC00") (class "Default")
      (node (ref "A16") (pin "B1") (pinfunction "P$2_B1") (pintype "bidirectional"))
      (node (ref "B16") (pin "B1") (pinfunction "P$2_B1") (pintype "bidirectional"))
    )
    (net (code "20") (name "BAC01") (class "Default")
      (node (ref "A16") (pin "D1") (pinfunction "P$2_D1") (pintype "bidirectional"))
      (node (ref "B16") (pin "D1") (pinfunction "P$2_D1") (pintype "bidirectional"))
    )
    (net (code "21") (name "BAC02") (class "Default")
      (node (ref "A16") (pin "E1") (pinfunction "P$2_E1") (pintype "bidirectional"))
      (node (ref "B16") (pin "E1") (pinfunction "P$2_E1") (pintype "bidirectional"))
    )
    (net (code "22") (name "BAC03") (class "Default")
      (node (ref "A16") (pin "H1") (pinfunction "P$2_H1") (pintype "bidirectional"))
      (node (ref "B16") (pin "H1") (pinfunction "P$2_H1") (pintype "bidirectional"))
    )
    (net (code "23") (name "BAC04") (class "Default")
      (node (ref "A16") (pin "J1") (pinfunction "P$2_J1") (pintype "bidirectional"))
      (node (ref "B16") (pin "J1") (pinfunction "P$2_J1") (pintype "bidirectional"))
    )
    (net (code "24") (name "BAC05") (class "Default")
      (node (ref "A16") (pin "L1") (pinfunction "P$2_L1") (pintype "bidirectional"))
      (node (ref "B16") (pin "L1") (pinfunction "P$2_L1") (pintype "bidirectional"))
    )
    (net (code "25") (name "BAC06") (class "Default")
      (node (ref "A16") (pin "M1") (pinfunction "P$2_M1") (pintype "bidirectional"))
      (node (ref "B16") (pin "M1") (pinfunction "P$2_M1") (pintype "bidirectional"))
    )
    (net (code "26") (name "BAC07") (class "Default")
      (node (ref "A16") (pin "P1") (pinfunction "P$2_P1") (pintype "bidirectional"))
      (node (ref "B16") (pin "P1") (pinfunction "P$2_P1") (pintype "bidirectional"))
    )
    (net (code "27") (name "BAC08") (class "Default")
      (node (ref "A16") (pin "S1") (pinfunction "P$2_S1") (pintype "bidirectional"))
      (node (ref "B16") (pin "S1") (pinfunction "P$2_S1") (pintype "bidirectional"))
    )
    (net (code "28") (name "BAC09") (class "Default")
      (node (ref "A16") (pin "D2") (pinfunction "P$2_D2") (pintype "bidirectional"))
      (node (ref "B16") (pin "D2") (pinfunction "P$2_D2") (pintype "bidirectional"))
    )
    (net (code "29") (name "BAC10") (class "Default")
      (node (ref "A16") (pin "E2") (pinfunction "P$2_E2") (pintype "bidirectional"))
      (node (ref "B16") (pin "E2") (pinfunction "P$2_E2") (pintype "bidirectional"))
    )
    (net (code "30") (name "BAC11") (class "Default")
      (node (ref "A16") (pin "H2") (pinfunction "P$2_H2") (pintype "bidirectional"))
      (node (ref "B16") (pin "H2") (pinfunction "P$2_H2") (pintype "bidirectional"))
    )
    (net (code "31") (name "BEMA") (class "Default")
      (node (ref "C14") (pin "V2") (pinfunction "OUT_V2") (pintype "output"))
      (node (ref "C19") (pin "T2") (pinfunction "P$2_T2") (pintype "bidirectional"))
      (node (ref "D19") (pin "T2") (pinfunction "P$2_T2") (pintype "bidirectional"))
    )
    (net (code "32") (name "BF0") (class "Default")
      (node (ref "D09") (pin "D2") (pinfunction "IN1A_D2") (pintype "input"))
      (node (ref "D11") (pin "E1") (pinfunction "1_E1") (pintype "output"))
    )
    (net (code "33") (name "BF1") (class "Default")
      (node (ref "D09") (pin "K2") (pinfunction "IN1A_K2") (pintype "input"))
      (node (ref "D11") (pin "H2") (pinfunction "1_H2") (pintype "output"))
    )
    (net (code "34") (name "BF2") (class "Default")
      (node (ref "D09") (pin "R2") (pinfunction "IN1A_R2") (pintype "input"))
      (node (ref "D11") (pin "L1") (pinfunction "1_L1") (pintype "output"))
    )
    (net (code "35") (name "BF_ENA") (class "Default")
      (node (ref "A09") (pin "E1") (pinfunction "OUT_E1") (pintype "output"))
      (node (ref "D09") (pin "E2") (pinfunction "IN1B_E2") (pintype "input"))
      (node (ref "D09") (pin "L2") (pinfunction "IN1B_L2") (pintype "input"))
      (node (ref "D09") (pin "S2") (pinfunction "IN1B_S2") (pintype "input"))
    )
    (net (code "36") (name "BIOP1") (class "Default")
      (node (ref "A16") (pin "K2") (pinfunction "P$2_K2") (pintype "bidirectional"))
      (node (ref "B16") (pin "K2") (pinfunction "P$2_K2") (pintype "bidirectional"))
      (node (ref "C13") (pin "L1") (pinfunction "IN1_L1") (pintype "input"))
    )
    (net (code "37") (name "BIOP2") (class "Default")
      (node (ref "A16") (pin "M2") (pinfunction "P$2_M2") (pintype "bidirectional"))
      (node (ref "B16") (pin "M2") (pinfunction "P$2_M2") (pintype "bidirectional"))
      (node (ref "C13") (pin "L2") (pinfunction "IN1_L2") (pintype "input"))
    )
    (net (code "38") (name "BIOP4") (class "Default")
      (node (ref "A08") (pin "D2") (pinfunction "IN1_D2") (pintype "input"))
      (node (ref "A08") (pin "K2") (pinfunction "IN1_K2") (pintype "input"))
      (node (ref "A08") (pin "M1") (pinfunction "IN1_M1") (pintype "input"))
      (node (ref "A08") (pin "R2") (pinfunction "IN1_R2") (pintype "input"))
      (node (ref "A16") (pin "P2") (pinfunction "P$2_P2") (pintype "bidirectional"))
      (node (ref "B16") (pin "P2") (pinfunction "P$2_P2") (pintype "bidirectional"))
    )
    (net (code "39") (name "BMA00") (class "Default")
      (node (ref "B12") (pin "D2") (pinfunction "IN1_D2") (pintype "input"))
      (node (ref "C20") (pin "D1") (pinfunction "P$2_D1") (pintype "bidirectional"))
      (node (ref "D20") (pin "D1") (pinfunction "P$2_D1") (pintype "bidirectional"))
    )
    (net (code "40") (name "BMA01") (class "Default")
      (node (ref "B12") (pin "K2") (pinfunction "IN1_K2") (pintype "input"))
      (node (ref "C20") (pin "E1") (pinfunction "P$2_E1") (pintype "bidirectional"))
      (node (ref "D20") (pin "E1") (pinfunction "P$2_E1") (pintype "bidirectional"))
    )
    (net (code "41") (name "BMA02") (class "Default")
      (node (ref "B12") (pin "R2") (pinfunction "IN1_R2") (pintype "input"))
      (node (ref "C20") (pin "H1") (pinfunction "P$2_H1") (pintype "bidirectional"))
      (node (ref "D20") (pin "H1") (pinfunction "P$2_H1") (pintype "bidirectional"))
    )
    (net (code "42") (name "BMA03") (class "Default")
      (node (ref "B13") (pin "A1") (pinfunction "IN1_A1") (pintype "input"))
      (node (ref "C20") (pin "J1") (pinfunction "P$2_J1") (pintype "bidirectional"))
      (node (ref "D20") (pin "J1") (pinfunction "P$2_J1") (pintype "bidirectional"))
    )
    (net (code "43") (name "BMA04") (class "Default")
      (node (ref "B13") (pin "F1") (pinfunction "IN1_F1") (pintype "input"))
      (node (ref "C20") (pin "L1") (pinfunction "P$2_L1") (pintype "bidirectional"))
      (node (ref "D20") (pin "L1") (pinfunction "P$2_L1") (pintype "bidirectional"))
    )
    (net (code "44") (name "BMA05") (class "Default")
      (node (ref "B13") (pin "M1") (pinfunction "IN1_M1") (pintype "input"))
      (node (ref "C20") (pin "M1") (pinfunction "P$2_M1") (pintype "bidirectional"))
      (node (ref "D20") (pin "M1") (pinfunction "P$2_M1") (pintype "bidirectional"))
    )
    (net (code "45") (name "BMA06") (class "Default")
      (node (ref "B13") (pin "D2") (pinfunction "IN1_D2") (pintype "input"))
      (node (ref "C20") (pin "P1") (pinfunction "P$2_P1") (pintype "bidirectional"))
      (node (ref "D20") (pin "P1") (pinfunction "P$2_P1") (pintype "bidirectional"))
    )
    (net (code "46") (name "BMA07") (class "Default")
      (node (ref "B13") (pin "K2") (pinfunction "IN1_K2") (pintype "input"))
      (node (ref "C20") (pin "S1") (pinfunction "P$2_S1") (pintype "bidirectional"))
      (node (ref "D20") (pin "S1") (pinfunction "P$2_S1") (pintype "bidirectional"))
    )
    (net (code "47") (name "BMA08") (class "Default")
      (node (ref "B13") (pin "R2") (pinfunction "IN1_R2") (pintype "input"))
      (node (ref "C20") (pin "D2") (pinfunction "P$2_D2") (pintype "bidirectional"))
      (node (ref "D20") (pin "D2") (pinfunction "P$2_D2") (pintype "bidirectional"))
    )
    (net (code "48") (name "BMA09") (class "Default")
      (node (ref "B14") (pin "A1") (pinfunction "IN1_A1") (pintype "input"))
      (node (ref "C20") (pin "E2") (pinfunction "P$2_E2") (pintype "bidirectional"))
      (node (ref "D20") (pin "E2") (pinfunction "P$2_E2") (pintype "bidirectional"))
    )
    (net (code "49") (name "BMA10") (class "Default")
      (node (ref "B14") (pin "F1") (pinfunction "IN1_F1") (pintype "input"))
      (node (ref "C20") (pin "H2") (pinfunction "P$2_H2") (pintype "bidirectional"))
      (node (ref "D20") (pin "H2") (pinfunction "P$2_H2") (pintype "bidirectional"))
    )
    (net (code "50") (name "BMA11") (class "Default")
      (node (ref "B14") (pin "M1") (pinfunction "IN1_M1") (pintype "input"))
      (node (ref "C20") (pin "K2") (pinfunction "P$2_K2") (pintype "bidirectional"))
      (node (ref "D20") (pin "K2") (pinfunction "P$2_K2") (pintype "bidirectional"))
    )
    (net (code "51") (name "BMB00") (class "Default")
      (node (ref "A17") (pin "B1") (pinfunction "P$2_B1") (pintype "bidirectional"))
      (node (ref "B10") (pin "A1") (pinfunction "IN_A1") (pintype "input"))
      (node (ref "B17") (pin "B1") (pinfunction "P$2_B1") (pintype "bidirectional"))
    )
    (net (code "52") (name "BMB01") (class "Default")
      (node (ref "A17") (pin "D1") (pinfunction "P$2_D1") (pintype "bidirectional"))
      (node (ref "B10") (pin "C1") (pinfunction "IN_C1") (pintype "input"))
      (node (ref "B17") (pin "D1") (pinfunction "P$2_D1") (pintype "bidirectional"))
    )
    (net (code "53") (name "BMB02") (class "Default")
      (node (ref "A17") (pin "E1") (pinfunction "P$2_E1") (pintype "bidirectional"))
      (node (ref "B10") (pin "D1") (pinfunction "IN_D1") (pintype "input"))
      (node (ref "B17") (pin "E1") (pinfunction "P$2_E1") (pintype "bidirectional"))
    )
    (net (code "54") (name "BMB03") (class "Default")
      (node (ref "A17") (pin "J1") (pinfunction "P$2_J1") (pintype "bidirectional"))
      (node (ref "B10") (pin "F1") (pinfunction "IN_F1") (pintype "input"))
      (node (ref "B17") (pin "J1") (pinfunction "P$2_J1") (pintype "bidirectional"))
    )
    (net (code "55") (name "BMB04") (class "Default")
      (node (ref "A08") (pin "C1") (pinfunction "IN3_C1") (pintype "input"))
      (node (ref "A08") (pin "J1") (pinfunction "IN3_J1") (pintype "input"))
      (node (ref "A17") (pin "M1") (pinfunction "P$2_M1") (pintype "bidirectional"))
      (node (ref "B10") (pin "E2") (pinfunction "IN_E2") (pintype "input"))
      (node (ref "B17") (pin "M1") (pinfunction "P$2_M1") (pintype "bidirectional"))
    )
    (net (code "56") (name "BMB05") (class "Default")
      (node (ref "A17") (pin "S1") (pinfunction "P$2_S1") (pintype "bidirectional"))
      (node (ref "B10") (pin "J1") (pinfunction "IN_J1") (pintype "input"))
      (node (ref "B17") (pin "S1") (pinfunction "P$2_S1") (pintype "bidirectional"))
    )
    (net (code "57") (name "BMB06") (class "Default")
      (node (ref "A08") (pin "A1") (pinfunction "IN1_A1") (pintype "input"))
      (node (ref "A17") (pin "E2") (pinfunction "P$2_E2") (pintype "bidirectional"))
      (node (ref "B10") (pin "H2") (pinfunction "IN_H2") (pintype "input"))
      (node (ref "B17") (pin "E2") (pinfunction "P$2_E2") (pintype "bidirectional"))
      (node (ref "C11") (pin "D1") (pinfunction "IN1_D1") (pintype "input"))
    )
    (net (code "58") (name "BMB07") (class "Default")
      (node (ref "A08") (pin "F2") (pinfunction "IN3_F2") (pintype "input"))
      (node (ref "A08") (pin "P1") (pinfunction "IN3_P1") (pintype "input"))
      (node (ref "A17") (pin "K2") (pinfunction "P$2_K2") (pintype "bidirectional"))
      (node (ref "B10") (pin "L1") (pinfunction "IN_L1") (pintype "input"))
      (node (ref "B17") (pin "K2") (pinfunction "P$2_K2") (pintype "bidirectional"))
      (node (ref "C11") (pin "L2") (pinfunction "IN1_L2") (pintype "input"))
    )
    (net (code "59") (name "BMB08") (class "Default")
      (node (ref "A08") (pin "N2") (pinfunction "IN4_N2") (pintype "input"))
      (node (ref "A08") (pin "R1") (pinfunction "IN4_R1") (pintype "input"))
      (node (ref "A17") (pin "P2") (pinfunction "P$2_P2") (pintype "bidirectional"))
      (node (ref "B10") (pin "K2") (pinfunction "IN_K2") (pintype "input"))
      (node (ref "B17") (pin "P2") (pinfunction "P$2_P2") (pintype "bidirectional"))
      (node (ref "C12") (pin "D1") (pinfunction "IN1_D1") (pintype "input"))
    )
    (net (code "60") (name "BMB09") (class "Default")
      (node (ref "A17") (pin "S2") (pinfunction "P$2_S2") (pintype "bidirectional"))
      (node (ref "B10") (pin "N1") (pinfunction "IN_N1") (pintype "input"))
      (node (ref "B17") (pin "S2") (pinfunction "P$2_S2") (pintype "bidirectional"))
      (node (ref "C11") (pin "B1") (pinfunction "IN2_B1") (pintype "input"))
      (node (ref "C11") (pin "J1") (pinfunction "IN2_J1") (pintype "input"))
      (node (ref "C11") (pin "M1") (pinfunction "IN2_M1") (pintype "input"))
      (node (ref "C11") (pin "R2") (pinfunction "IN2_R2") (pintype "input"))
      (node (ref "C12") (pin "B1") (pinfunction "IN2_B1") (pintype "input"))
      (node (ref "C12") (pin "J1") (pinfunction "IN2_J1") (pintype "input"))
    )
    (net (code "61") (name "BMB10") (class "Default")
      (node (ref "A17") (pin "T2") (pinfunction "P$2_T2") (pintype "bidirectional"))
      (node (ref "B10") (pin "M2") (pinfunction "IN_M2") (pintype "input"))
      (node (ref "B17") (pin "T2") (pinfunction "P$2_T2") (pintype "bidirectional"))
    )
    (net (code "62") (name "BMB11") (class "Default")
      (node (ref "A17") (pin "V2") (pinfunction "P$2_V2") (pintype "bidirectional"))
      (node (ref "B10") (pin "R1") (pinfunction "IN_R1") (pintype "input"))
      (node (ref "B17") (pin "V2") (pinfunction "P$2_V2") (pintype "bidirectional"))
    )
    (net (code "63") (name "BTP2") (class "Default")
      (node (ref "C20") (pin "T2") (pinfunction "P$2_T2") (pintype "bidirectional"))
      (node (ref "D08") (pin "A1") (pinfunction "IN_A1") (pintype "input"))
      (node (ref "D14") (pin "B1") (pinfunction "C_B1") (pintype "input"))
      (node (ref "D14") (pin "R1") (pinfunction "S_R1") (pintype "input"))
      (node (ref "D20") (pin "T2") (pinfunction "P$2_T2") (pintype "bidirectional"))
    )
    (net (code "64") (name "BTP3") (class "Default")
      (node (ref "C09") (pin "V2") (pinfunction "IN3_V2") (pintype "input"))
      (node (ref "C18") (pin "H1") (pinfunction "P$2_H1") (pintype "bidirectional"))
      (node (ref "D18") (pin "H1") (pinfunction "P$2_H1") (pintype "bidirectional"))
    )
    (net (code "65") (name "BTS1") (class "Default")
      (node (ref "A16") (pin "T2") (pinfunction "P$2_T2") (pintype "bidirectional"))
      (node (ref "B16") (pin "T2") (pinfunction "P$2_T2") (pintype "bidirectional"))
    )
    (net (code "66") (name "BTS3") (class "Default")
      (node (ref "A16") (pin "S2") (pinfunction "P$2_S2") (pintype "bidirectional"))
      (node (ref "B16") (pin "S2") (pinfunction "P$2_S2") (pintype "bidirectional"))
    )
    (net (code "67") (name "B_INIT") (class "Default")
      (node (ref "A19") (pin "V2") (pinfunction "P$2_V2") (pintype "bidirectional"))
      (node (ref "B10") (pin "U2") (pinfunction "IN_U2") (pintype "input"))
      (node (ref "B19") (pin "V2") (pinfunction "P$2_V2") (pintype "bidirectional"))
      (node (ref "C14") (pin "F1") (pinfunction "IN1_F1") (pintype "input"))
    )
    (net (code "68") (name "B_INITIALIZE") (class "Default")
      (node (ref "A16") (pin "V2") (pinfunction "P$2_V2") (pintype "bidirectional"))
      (node (ref "B16") (pin "V2") (pinfunction "P$2_V2") (pintype "bidirectional"))
    )
    (net (code "69") (name "B_LOAD_SF") (class "Default")
      (node (ref "B14") (pin "V2") (pinfunction "OUT_V2") (pintype "output"))
      (node (ref "D08") (pin "M2") (pinfunction "IN_M2") (pintype "input"))
      (node (ref "D08") (pin "N1") (pinfunction "IN_N1") (pintype "input"))
      (node (ref "D08") (pin "P2") (pinfunction "IN_P2") (pintype "input"))
      (node (ref "D08") (pin "R1") (pinfunction "IN_R1") (pintype "input"))
      (node (ref "D13") (pin "B1") (pinfunction "C_B1") (pintype "input"))
      (node (ref "D13") (pin "D2") (pinfunction "C_D2") (pintype "input"))
      (node (ref "D13") (pin "H1") (pinfunction "C_H1") (pintype "input"))
      (node (ref "D13") (pin "L2") (pinfunction "C_L2") (pintype "input"))
      (node (ref "D13") (pin "N1") (pinfunction "C_N1") (pintype "input"))
      (node (ref "D13") (pin "S2") (pinfunction "C_S2") (pintype "input"))
    )
    (net (code "70") (name "DEL1") (class "Default")
      (node (ref "C09") (pin "C1") (pinfunction "IN3_C1") (pintype "input"))
      (node (ref "C09") (pin "J2") (pinfunction "IN1_J2") (pintype "input"))
      (node (ref "D15") (pin "F1") (pinfunction "OUT_F1") (pintype "output"))
    )
    (net (code "71") (name "DEL2") (class "Default")
      (node (ref "C09") (pin "D2") (pinfunction "IN1_D2") (pintype "input"))
      (node (ref "D11") (pin "B1") (pinfunction "C_B1") (pintype "input"))
      (node (ref "D11") (pin "D2") (pinfunction "C_D2") (pintype "input"))
      (node (ref "D11") (pin "H1") (pinfunction "C_H1") (pintype "input"))
      (node (ref "D15") (pin "J1") (pinfunction "OUT_J1") (pintype "output"))
      (node (ref "D16") (pin "H2") (pinfunction "H2_H2") (pintype "input"))
    )
    (net (code "72") (name "DEL3") (class "Default")
      (node (ref "C16") (pin "N2") (pinfunction "IN1_N2") (pintype "input"))
      (node (ref "C16") (pin "P2") (pinfunction "IN2_P2") (pintype "input"))
      (node (ref "D14") (pin "H1") (pinfunction "C_H1") (pintype "input"))
      (node (ref "D14") (pin "L2") (pinfunction "C_L2") (pintype "input"))
      (node (ref "D16") (pin "F1") (pinfunction "OUT_F1") (pintype "output"))
    )
    (net (code "73") (name "DEL4") (class "Default")
      (node (ref "C09") (pin "P1") (pinfunction "IN1_P1") (pintype "input"))
      (node (ref "C16") (pin "P1") (pinfunction "IN1_P1") (pintype "input"))
      (node (ref "D14") (pin "D2") (pinfunction "C_D2") (pintype "input"))
      (node (ref "D14") (pin "S2") (pinfunction "C_S2") (pintype "input"))
      (node (ref "D16") (pin "J1") (pinfunction "OUT_J1") (pintype "output"))
      (node (ref "D17") (pin "H2") (pinfunction "H2_H2") (pintype "input"))
    )
    (net (code "74") (name "DEL5") (class "Default")
      (node (ref "C09") (pin "N2") (pinfunction "IN1_N2") (pintype "input"))
      (node (ref "D14") (pin "N1") (pinfunction "C_N1") (pintype "input"))
      (node (ref "D17") (pin "F1") (pinfunction "OUT_F1") (pintype "output"))
    )
    (net (code "75") (name "DEL6") (class "Default")
      (node (ref "D12") (pin "H1") (pinfunction "C_H1") (pintype "input"))
      (node (ref "D17") (pin "J1") (pinfunction "OUT_J1") (pintype "output"))
    )
    (net (code "76") (name "DF0") (class "Default")
      (node (ref "C10") (pin "H2") (pinfunction "IN1_H2") (pintype "input"))
      (node (ref "D12") (pin "P2") (pinfunction "1_P2") (pintype "output"))
      (node (ref "D13") (pin "E2") (pinfunction "D_E2") (pintype "input"))
    )
    (net (code "77") (name "DF1") (class "Default")
      (node (ref "C10") (pin "L2") (pinfunction "IN1_L2") (pintype "input"))
      (node (ref "D12") (pin "S1") (pinfunction "1_S1") (pintype "output"))
      (node (ref "D13") (pin "M2") (pinfunction "D_M2") (pintype "input"))
    )
    (net (code "78") (name "DF2") (class "Default")
      (node (ref "C10") (pin "P2") (pinfunction "IN1_P2") (pintype "input"))
      (node (ref "C13") (pin "D1") (pinfunction "IN1_D1") (pintype "input"))
      (node (ref "D12") (pin "V2") (pinfunction "1_V2") (pintype "output"))
      (node (ref "D13") (pin "T2") (pinfunction "D_T2") (pintype "input"))
    )
    (net (code "79") (name "DFD0") (class "Default")
      (node (ref "C11") (pin "K2") (pinfunction "OUT_K2") (pintype "output"))
      (node (ref "D12") (pin "M2") (pinfunction "D_M2") (pintype "input"))
    )
    (net (code "80") (name "DFD1") (class "Default")
      (node (ref "C11") (pin "V2") (pinfunction "OUT_V2") (pintype "output"))
      (node (ref "D12") (pin "P1") (pinfunction "D_P1") (pintype "input"))
    )
    (net (code "81") (name "DFD2") (class "Default")
      (node (ref "C12") (pin "K2") (pinfunction "OUT_K2") (pintype "output"))
      (node (ref "D12") (pin "T2") (pinfunction "D_T2") (pintype "input"))
    )
    (net (code "82") (name "DF_ENA") (class "Default")
      (node (ref "A09") (pin "L2") (pinfunction "OUT_L2") (pintype "output"))
      (node (ref "C10") (pin "J2") (pinfunction "IN2_J2") (pintype "input"))
      (node (ref "C10") (pin "M2") (pinfunction "IN2_M2") (pintype "input"))
      (node (ref "C10") (pin "R2") (pinfunction "IN2_R2") (pintype "input"))
    )
    (net (code "83") (name "DONE") (class "Default")
      (node (ref "CD02") (pin "BS1") (pinfunction "P$2_BS1") (pintype "bidirectional"))
      (node (ref "CD03") (pin "BS1") (pinfunction "P$2_BS1") (pintype "bidirectional"))
      (node (ref "CD04") (pin "BS1") (pinfunction "P$2_BS1") (pintype "bidirectional"))
      (node (ref "CD05") (pin "BS1") (pinfunction "P$2_BS1") (pintype "bidirectional"))
      (node (ref "CD06") (pin "BS1") (pinfunction "P$2_BS1") (pintype "bidirectional"))
      (node (ref "CD07") (pin "BS1") (pinfunction "P$2_BS1") (pintype "bidirectional"))
      (node (ref "D12") (pin "L1") (pinfunction "1_L1") (pintype "output"))
    )
    (net (code "84") (name "EA0") (class "Default")
      (node (ref "C15") (pin "C1") (pinfunction "D_C1") (pintype "input"))
      (node (ref "C17") (pin "J2") (pinfunction "P$2_J2") (pintype "bidirectional"))
      (node (ref "CD01") (pin "AM2") (pinfunction "P$2_AM2") (pintype "bidirectional"))
      (node (ref "CD02") (pin "AM2") (pinfunction "P$2_AM2") (pintype "bidirectional"))
      (node (ref "CD03") (pin "AM2") (pinfunction "P$2_AM2") (pintype "bidirectional"))
      (node (ref "CD04") (pin "AM2") (pinfunction "P$2_AM2") (pintype "bidirectional"))
      (node (ref "CD05") (pin "AM2") (pinfunction "P$2_AM2") (pintype "bidirectional"))
      (node (ref "CD06") (pin "AM2") (pinfunction "P$2_AM2") (pintype "bidirectional"))
      (node (ref "CD07") (pin "AM2") (pinfunction "P$2_AM2") (pintype "bidirectional"))
      (node (ref "D10") (pin "E1") (pinfunction "1_E1") (pintype "output"))
    )
    (net (code "85") (name "EA1") (class "Default")
      (node (ref "C15") (pin "E2") (pinfunction "D_E2") (pintype "input"))
      (node (ref "C17") (pin "N2") (pinfunction "P$2_N2") (pintype "bidirectional"))
      (node (ref "CD01") (pin "AL2") (pinfunction "P$2_AL2") (pintype "bidirectional"))
      (node (ref "CD02") (pin "AL2") (pinfunction "P$2_AL2") (pintype "bidirectional"))
      (node (ref "CD03") (pin "AL2") (pinfunction "P$2_AL2") (pintype "bidirectional"))
      (node (ref "CD04") (pin "AL2") (pinfunction "P$2_AL2") (pintype "bidirectional"))
      (node (ref "CD05") (pin "AL2") (pinfunction "P$2_AL2") (pintype "bidirectional"))
      (node (ref "CD06") (pin "AL2") (pinfunction "P$2_AL2") (pintype "bidirectional"))
      (node (ref "CD07") (pin "AL2") (pinfunction "P$2_AL2") (pintype "bidirectional"))
      (node (ref "D10") (pin "H2") (pinfunction "1_H2") (pintype "output"))
    )
    (net (code "86") (name "EA2") (class "Default")
      (node (ref "C14") (pin "K2") (pinfunction "IN1_K2") (pintype "input"))
      (node (ref "C15") (pin "J1") (pinfunction "D_J1") (pintype "input"))
      (node (ref "C16") (pin "M1") (pinfunction "IN3_M1") (pintype "input"))
      (node (ref "C17") (pin "T2") (pinfunction "P$2_T2") (pintype "bidirectional"))
      (node (ref "D10") (pin "L1") (pinfunction "1_L1") (pintype "output"))
    )
    (net (code "87") (name "EAB0") (class "Default")
      (node (ref "B12") (pin "A1") (pinfunction "IN1_A1") (pintype "input"))
      (node (ref "C15") (pin "E1") (pinfunction "1_E1") (pintype "output"))
    )
    (net (code "88") (name "EAB1") (class "Default")
      (node (ref "B12") (pin "F1") (pinfunction "IN1_F1") (pintype "input"))
      (node (ref "C15") (pin "H2") (pinfunction "1_H2") (pintype "output"))
    )
    (net (code "89") (name "EAB2") (class "Default")
      (node (ref "B12") (pin "M1") (pinfunction "IN1_M1") (pintype "input"))
      (node (ref "C15") (pin "L1") (pinfunction "1_L1") (pintype "output"))
    )
    (net (code "90") (name "EAD0") (class "Default")
      (node (ref "C10") (pin "N1") (pinfunction "OUT_N1") (pintype "output"))
      (node (ref "D10") (pin "C1") (pinfunction "D_C1") (pintype "input"))
    )
    (net (code "91") (name "EAD1") (class "Default")
      (node (ref "C10") (pin "S1") (pinfunction "OUT_S1") (pintype "output"))
      (node (ref "D10") (pin "E2") (pinfunction "D_E2") (pintype "input"))
    )
    (net (code "92") (name "EAD2") (class "Default")
      (node (ref "C10") (pin "V2") (pinfunction "OUT_V2") (pintype "output"))
      (node (ref "D10") (pin "J1") (pinfunction "D_J1") (pintype "input"))
    )
    (net (code "93") (name "EA_OK") (class "Default")
      (node (ref "C16") (pin "J1") (pinfunction "OUT_J1") (pintype "output"))
      (node (ref "D12") (pin "E2") (pinfunction "D_E2") (pintype "input"))
    )
    (net (code "94") (name "EXT_MEM") (class "Default")
      (node (ref "A08") (pin "E2") (pinfunction "IN2_E2") (pintype "input"))
      (node (ref "A08") (pin "L2") (pinfunction "IN2_L2") (pintype "input"))
      (node (ref "A08") (pin "N1") (pinfunction "IN2_N1") (pintype "input"))
      (node (ref "B10") (pin "U1") (pinfunction "OUT_U1") (pintype "output"))
      (node (ref "C13") (pin "M1") (pinfunction "IN2_M1") (pintype "input"))
      (node (ref "C13") (pin "M2") (pinfunction "IN2_M2") (pintype "input"))
    )
    (net (code "95") (name "E_OR_F_SET") (class "Default")
      (node (ref "C09") (pin "T2") (pinfunction "IN1_T2") (pintype "input"))
      (node (ref "C10") (pin "A1") (pinfunction "IN1_A1") (pintype "input"))
      (node (ref "C18") (pin "D2") (pinfunction "P$2_D2") (pintype "bidirectional"))
      (node (ref "D18") (pin "D2") (pinfunction "P$2_D2") (pintype "bidirectional"))
    )
    (net (code "96") (name "FIELD1") (class "Default")
      (node (ref "B10") (pin "T2") (pinfunction "OUT_T2") (pintype "output"))
      (node (ref "C20") (pin "M2") (pinfunction "P$2_M2") (pintype "bidirectional"))
      (node (ref "D20") (pin "M2") (pinfunction "P$2_M2") (pintype "bidirectional"))
    )
    (net (code "97") (name "GND") (class "Default")
      (node (ref "A14") (pin "P1") (pinfunction "C_P1") (pintype "input"))
      (node (ref "AB01") (pin "AC2") (pinfunction "P$2_AC2") (pintype "bidirectional"))
      (node (ref "AB01") (pin "BC2") (pinfunction "P$2_BC2") (pintype "bidirectional"))
      (node (ref "AB02") (pin "AC1") (pinfunction "P$2_AC1") (pintype "bidirectional"))
      (node (ref "AB02") (pin "AC2") (pinfunction "P$2_AC2") (pintype "bidirectional"))
      (node (ref "AB02") (pin "AF1") (pinfunction "P$2_AF1") (pintype "bidirectional"))
      (node (ref "AB02") (pin "AF2") (pinfunction "P$2_AF2") (pintype "bidirectional"))
      (node (ref "AB02") (pin "AN1") (pinfunction "P$2_AN1") (pintype "bidirectional"))
      (node (ref "AB02") (pin "AN2") (pinfunction "P$2_AN2") (pintype "bidirectional"))
      (node (ref "AB02") (pin "AT1") (pinfunction "P$2_AT1") (pintype "bidirectional"))
      (node (ref "AB02") (pin "AT2") (pinfunction "P$2_AT2") (pintype "bidirectional"))
      (node (ref "AB02") (pin "BC1") (pinfunction "P$2_BC1") (pintype "bidirectional"))
      (node (ref "AB02") (pin "BC2") (pinfunction "P$2_BC2") (pintype "bidirectional"))
      (node (ref "AB02") (pin "BF1") (pinfunction "P$2_BF1") (pintype "bidirectional"))
      (node (ref "AB02") (pin "BF2") (pinfunction "P$2_BF2") (pintype "bidirectional"))
      (node (ref "AB02") (pin "BN1") (pinfunction "P$2_BN1") (pintype "bidirectional"))
      (node (ref "AB02") (pin "BN2") (pinfunction "P$2_BN2") (pintype "bidirectional"))
      (node (ref "AB02") (pin "BT1") (pinfunction "P$2_BT1") (pintype "bidirectional"))
      (node (ref "AB02") (pin "BT2") (pinfunction "P$2_BT2") (pintype "bidirectional"))
      (node (ref "AB03") (pin "AC1") (pinfunction "P$2_AC1") (pintype "bidirectional"))
      (node (ref "AB03") (pin "AC2") (pinfunction "P$2_AC2") (pintype "bidirectional"))
      (node (ref "AB03") (pin "AF1") (pinfunction "P$2_AF1") (pintype "bidirectional"))
      (node (ref "AB03") (pin "AF2") (pinfunction "P$2_AF2") (pintype "bidirectional"))
      (node (ref "AB03") (pin "AN1") (pinfunction "P$2_AN1") (pintype "bidirectional"))
      (node (ref "AB03") (pin "AN2") (pinfunction "P$2_AN2") (pintype "bidirectional"))
      (node (ref "AB03") (pin "AT1") (pinfunction "P$2_AT1") (pintype "bidirectional"))
      (node (ref "AB03") (pin "AT2") (pinfunction "P$2_AT2") (pintype "bidirectional"))
      (node (ref "AB03") (pin "BC1") (pinfunction "P$2_BC1") (pintype "bidirectional"))
      (node (ref "AB03") (pin "BC2") (pinfunction "P$2_BC2") (pintype "bidirectional"))
      (node (ref "AB03") (pin "BF1") (pinfunction "P$2_BF1") (pintype "bidirectional"))
      (node (ref "AB03") (pin "BF2") (pinfunction "P$2_BF2") (pintype "bidirectional"))
      (node (ref "AB03") (pin "BN1") (pinfunction "P$2_BN1") (pintype "bidirectional"))
      (node (ref "AB03") (pin "BN2") (pinfunction "P$2_BN2") (pintype "bidirectional"))
      (node (ref "AB03") (pin "BT1") (pinfunction "P$2_BT1") (pintype "bidirectional"))
      (node (ref "AB03") (pin "BT2") (pinfunction "P$2_BT2") (pintype "bidirectional"))
      (node (ref "AB04") (pin "AC1") (pinfunction "P$2_AC1") (pintype "bidirectional"))
      (node (ref "AB04") (pin "AC2") (pinfunction "P$2_AC2") (pintype "bidirectional"))
      (node (ref "AB04") (pin "AF1") (pinfunction "P$2_AF1") (pintype "bidirectional"))
      (node (ref "AB04") (pin "AF2") (pinfunction "P$2_AF2") (pintype "bidirectional"))
      (node (ref "AB04") (pin "AN1") (pinfunction "P$2_AN1") (pintype "bidirectional"))
      (node (ref "AB04") (pin "AN2") (pinfunction "P$2_AN2") (pintype "bidirectional"))
      (node (ref "AB04") (pin "AT1") (pinfunction "P$2_AT1") (pintype "bidirectional"))
      (node (ref "AB04") (pin "AT2") (pinfunction "P$2_AT2") (pintype "bidirectional"))
      (node (ref "AB04") (pin "BC1") (pinfunction "P$2_BC1") (pintype "bidirectional"))
      (node (ref "AB04") (pin "BC2") (pinfunction "P$2_BC2") (pintype "bidirectional"))
      (node (ref "AB04") (pin "BF1") (pinfunction "P$2_BF1") (pintype "bidirectional"))
      (node (ref "AB04") (pin "BF2") (pinfunction "P$2_BF2") (pintype "bidirectional"))
      (node (ref "AB04") (pin "BN1") (pinfunction "P$2_BN1") (pintype "bidirectional"))
      (node (ref "AB04") (pin "BN2") (pinfunction "P$2_BN2") (pintype "bidirectional"))
      (node (ref "AB04") (pin "BT1") (pinfunction "P$2_BT1") (pintype "bidirectional"))
      (node (ref "AB04") (pin "BT2") (pinfunction "P$2_BT2") (pintype "bidirectional"))
      (node (ref "AB05") (pin "AC1") (pinfunction "P$2_AC1") (pintype "bidirectional"))
      (node (ref "AB05") (pin "AC2") (pinfunction "P$2_AC2") (pintype "bidirectional"))
      (node (ref "AB05") (pin "AF1") (pinfunction "P$2_AF1") (pintype "bidirectional"))
      (node (ref "AB05") (pin "AF2") (pinfunction "P$2_AF2") (pintype "bidirectional"))
      (node (ref "AB05") (pin "AN1") (pinfunction "P$2_AN1") (pintype "bidirectional"))
      (node (ref "AB05") (pin "AN2") (pinfunction "P$2_AN2") (pintype "bidirectional"))
      (node (ref "AB05") (pin "AT1") (pinfunction "P$2_AT1") (pintype "bidirectional"))
      (node (ref "AB05") (pin "AT2") (pinfunction "P$2_AT2") (pintype "bidirectional"))
      (node (ref "AB05") (pin "BC1") (pinfunction "P$2_BC1") (pintype "bidirectional"))
      (node (ref "AB05") (pin "BC2") (pinfunction "P$2_BC2") (pintype "bidirectional"))
      (node (ref "AB05") (pin "BF1") (pinfunction "P$2_BF1") (pintype "bidirectional"))
      (node (ref "AB05") (pin "BF2") (pinfunction "P$2_BF2") (pintype "bidirectional"))
      (node (ref "AB05") (pin "BN1") (pinfunction "P$2_BN1") (pintype "bidirectional"))
      (node (ref "AB05") (pin "BN2") (pinfunction "P$2_BN2") (pintype "bidirectional"))
      (node (ref "AB05") (pin "BT1") (pinfunction "P$2_BT1") (pintype "bidirectional"))
      (node (ref "AB05") (pin "BT2") (pinfunction "P$2_BT2") (pintype "bidirectional"))
      (node (ref "AB06") (pin "AC1") (pinfunction "P$2_AC1") (pintype "bidirectional"))
      (node (ref "AB06") (pin "AC2") (pinfunction "P$2_AC2") (pintype "bidirectional"))
      (node (ref "AB06") (pin "AF1") (pinfunction "P$2_AF1") (pintype "bidirectional"))
      (node (ref "AB06") (pin "AF2") (pinfunction "P$2_AF2") (pintype "bidirectional"))
      (node (ref "AB06") (pin "AN1") (pinfunction "P$2_AN1") (pintype "bidirectional"))
      (node (ref "AB06") (pin "AN2") (pinfunction "P$2_AN2") (pintype "bidirectional"))
      (node (ref "AB06") (pin "AT1") (pinfunction "P$2_AT1") (pintype "bidirectional"))
      (node (ref "AB06") (pin "AT2") (pinfunction "P$2_AT2") (pintype "bidirectional"))
      (node (ref "AB06") (pin "BC1") (pinfunction "P$2_BC1") (pintype "bidirectional"))
      (node (ref "AB06") (pin "BC2") (pinfunction "P$2_BC2") (pintype "bidirectional"))
      (node (ref "AB06") (pin "BF1") (pinfunction "P$2_BF1") (pintype "bidirectional"))
      (node (ref "AB06") (pin "BF2") (pinfunction "P$2_BF2") (pintype "bidirectional"))
      (node (ref "AB06") (pin "BN1") (pinfunction "P$2_BN1") (pintype "bidirectional"))
      (node (ref "AB06") (pin "BN2") (pinfunction "P$2_BN2") (pintype "bidirectional"))
      (node (ref "AB06") (pin "BT1") (pinfunction "P$2_BT1") (pintype "bidirectional"))
      (node (ref "AB06") (pin "BT2") (pinfunction "P$2_BT2") (pintype "bidirectional"))
      (node (ref "AB07") (pin "AC1") (pinfunction "P$2_AC1") (pintype "bidirectional"))
      (node (ref "AB07") (pin "AC2") (pinfunction "P$2_AC2") (pintype "bidirectional"))
      (node (ref "AB07") (pin "AF1") (pinfunction "P$2_AF1") (pintype "bidirectional"))
      (node (ref "AB07") (pin "AF2") (pinfunction "P$2_AF2") (pintype "bidirectional"))
      (node (ref "AB07") (pin "AN1") (pinfunction "P$2_AN1") (pintype "bidirectional"))
      (node (ref "AB07") (pin "AN2") (pinfunction "P$2_AN2") (pintype "bidirectional"))
      (node (ref "AB07") (pin "AT1") (pinfunction "P$2_AT1") (pintype "bidirectional"))
      (node (ref "AB07") (pin "AT2") (pinfunction "P$2_AT2") (pintype "bidirectional"))
      (node (ref "AB07") (pin "BC1") (pinfunction "P$2_BC1") (pintype "bidirectional"))
      (node (ref "AB07") (pin "BC2") (pinfunction "P$2_BC2") (pintype "bidirectional"))
      (node (ref "AB07") (pin "BF1") (pinfunction "P$2_BF1") (pintype "bidirectional"))
      (node (ref "AB07") (pin "BF2") (pinfunction "P$2_BF2") (pintype "bidirectional"))
      (node (ref "AB07") (pin "BN1") (pinfunction "P$2_BN1") (pintype "bidirectional"))
      (node (ref "AB07") (pin "BN2") (pinfunction "P$2_BN2") (pintype "bidirectional"))
      (node (ref "AB07") (pin "BT1") (pinfunction "P$2_BT1") (pintype "bidirectional"))
      (node (ref "AB07") (pin "BT2") (pinfunction "P$2_BT2") (pintype "bidirectional"))
      (node (ref "CD01") (pin "AC2") (pinfunction "P$2_AC2") (pintype "bidirectional"))
      (node (ref "CD01") (pin "BC2") (pinfunction "P$2_BC2") (pintype "bidirectional"))
      (node (ref "CD02") (pin "AC1") (pinfunction "P$2_AC1") (pintype "bidirectional"))
      (node (ref "CD02") (pin "AC2") (pinfunction "P$2_AC2") (pintype "bidirectional"))
      (node (ref "CD02") (pin "AF1") (pinfunction "P$2_AF1") (pintype "bidirectional"))
      (node (ref "CD02") (pin "AF2") (pinfunction "P$2_AF2") (pintype "bidirectional"))
      (node (ref "CD02") (pin "AN1") (pinfunction "P$2_AN1") (pintype "bidirectional"))
      (node (ref "CD02") (pin "AN2") (pinfunction "P$2_AN2") (pintype "bidirectional"))
      (node (ref "CD02") (pin "AT1") (pinfunction "P$2_AT1") (pintype "bidirectional"))
      (node (ref "CD02") (pin "AT2") (pinfunction "P$2_AT2") (pintype "bidirectional"))
      (node (ref "CD02") (pin "BC1") (pinfunction "P$2_BC1") (pintype "bidirectional"))
      (node (ref "CD02") (pin "BC2") (pinfunction "P$2_BC2") (pintype "bidirectional"))
      (node (ref "CD02") (pin "BF1") (pinfunction "P$2_BF1") (pintype "bidirectional"))
      (node (ref "CD02") (pin "BF2") (pinfunction "P$2_BF2") (pintype "bidirectional"))
      (node (ref "CD02") (pin "BN1") (pinfunction "P$2_BN1") (pintype "bidirectional"))
      (node (ref "CD02") (pin "BN2") (pinfunction "P$2_BN2") (pintype "bidirectional"))
      (node (ref "CD02") (pin "BT1") (pinfunction "P$2_BT1") (pintype "bidirectional"))
      (node (ref "CD02") (pin "BT2") (pinfunction "P$2_BT2") (pintype "bidirectional"))
      (node (ref "CD03") (pin "AC1") (pinfunction "P$2_AC1") (pintype "bidirectional"))
      (node (ref "CD03") (pin "AC2") (pinfunction "P$2_AC2") (pintype "bidirectional"))
      (node (ref "CD03") (pin "AF1") (pinfunction "P$2_AF1") (pintype "bidirectional"))
      (node (ref "CD03") (pin "AF2") (pinfunction "P$2_AF2") (pintype "bidirectional"))
      (node (ref "CD03") (pin "AN1") (pinfunction "P$2_AN1") (pintype "bidirectional"))
      (node (ref "CD03") (pin "AN2") (pinfunction "P$2_AN2") (pintype "bidirectional"))
      (node (ref "CD03") (pin "AT1") (pinfunction "P$2_AT1") (pintype "bidirectional"))
      (node (ref "CD03") (pin "AT2") (pinfunction "P$2_AT2") (pintype "bidirectional"))
      (node (ref "CD03") (pin "BC1") (pinfunction "P$2_BC1") (pintype "bidirectional"))
      (node (ref "CD03") (pin "BC2") (pinfunction "P$2_BC2") (pintype "bidirectional"))
      (node (ref "CD03") (pin "BF1") (pinfunction "P$2_BF1") (pintype "bidirectional"))
      (node (ref "CD03") (pin "BF2") (pinfunction "P$2_BF2") (pintype "bidirectional"))
      (node (ref "CD03") (pin "BN1") (pinfunction "P$2_BN1") (pintype "bidirectional"))
      (node (ref "CD03") (pin "BN2") (pinfunction "P$2_BN2") (pintype "bidirectional"))
      (node (ref "CD03") (pin "BT1") (pinfunction "P$2_BT1") (pintype "bidirectional"))
      (node (ref "CD03") (pin "BT2") (pinfunction "P$2_BT2") (pintype "bidirectional"))
      (node (ref "CD04") (pin "AC1") (pinfunction "P$2_AC1") (pintype "bidirectional"))
      (node (ref "CD04") (pin "AC2") (pinfunction "P$2_AC2") (pintype "bidirectional"))
      (node (ref "CD04") (pin "AF1") (pinfunction "P$2_AF1") (pintype "bidirectional"))
      (node (ref "CD04") (pin "AF2") (pinfunction "P$2_AF2") (pintype "bidirectional"))
      (node (ref "CD04") (pin "AN1") (pinfunction "P$2_AN1") (pintype "bidirectional"))
      (node (ref "CD04") (pin "AN2") (pinfunction "P$2_AN2") (pintype "bidirectional"))
      (node (ref "CD04") (pin "AT1") (pinfunction "P$2_AT1") (pintype "bidirectional"))
      (node (ref "CD04") (pin "AT2") (pinfunction "P$2_AT2") (pintype "bidirectional"))
      (node (ref "CD04") (pin "BC1") (pinfunction "P$2_BC1") (pintype "bidirectional"))
      (node (ref "CD04") (pin "BC2") (pinfunction "P$2_BC2") (pintype "bidirectional"))
      (node (ref "CD04") (pin "BF1") (pinfunction "P$2_BF1") (pintype "bidirectional"))
      (node (ref "CD04") (pin "BF2") (pinfunction "P$2_BF2") (pintype "bidirectional"))
      (node (ref "CD04") (pin "BN1") (pinfunction "P$2_BN1") (pintype "bidirectional"))
      (node (ref "CD04") (pin "BN2") (pinfunction "P$2_BN2") (pintype "bidirectional"))
      (node (ref "CD04") (pin "BT1") (pinfunction "P$2_BT1") (pintype "bidirectional"))
      (node (ref "CD04") (pin "BT2") (pinfunction "P$2_BT2") (pintype "bidirectional"))
      (node (ref "CD05") (pin "AC1") (pinfunction "P$2_AC1") (pintype "bidirectional"))
      (node (ref "CD05") (pin "AC2") (pinfunction "P$2_AC2") (pintype "bidirectional"))
      (node (ref "CD05") (pin "AF1") (pinfunction "P$2_AF1") (pintype "bidirectional"))
      (node (ref "CD05") (pin "AF2") (pinfunction "P$2_AF2") (pintype "bidirectional"))
      (node (ref "CD05") (pin "AN1") (pinfunction "P$2_AN1") (pintype "bidirectional"))
      (node (ref "CD05") (pin "AN2") (pinfunction "P$2_AN2") (pintype "bidirectional"))
      (node (ref "CD05") (pin "AT1") (pinfunction "P$2_AT1") (pintype "bidirectional"))
      (node (ref "CD05") (pin "AT2") (pinfunction "P$2_AT2") (pintype "bidirectional"))
      (node (ref "CD05") (pin "BC1") (pinfunction "P$2_BC1") (pintype "bidirectional"))
      (node (ref "CD05") (pin "BC2") (pinfunction "P$2_BC2") (pintype "bidirectional"))
      (node (ref "CD05") (pin "BF1") (pinfunction "P$2_BF1") (pintype "bidirectional"))
      (node (ref "CD05") (pin "BF2") (pinfunction "P$2_BF2") (pintype "bidirectional"))
      (node (ref "CD05") (pin "BN1") (pinfunction "P$2_BN1") (pintype "bidirectional"))
      (node (ref "CD05") (pin "BN2") (pinfunction "P$2_BN2") (pintype "bidirectional"))
      (node (ref "CD05") (pin "BT1") (pinfunction "P$2_BT1") (pintype "bidirectional"))
      (node (ref "CD05") (pin "BT2") (pinfunction "P$2_BT2") (pintype "bidirectional"))
      (node (ref "CD06") (pin "AC1") (pinfunction "P$2_AC1") (pintype "bidirectional"))
      (node (ref "CD06") (pin "AC2") (pinfunction "P$2_AC2") (pintype "bidirectional"))
      (node (ref "CD06") (pin "AF1") (pinfunction "P$2_AF1") (pintype "bidirectional"))
      (node (ref "CD06") (pin "AF2") (pinfunction "P$2_AF2") (pintype "bidirectional"))
      (node (ref "CD06") (pin "AN1") (pinfunction "P$2_AN1") (pintype "bidirectional"))
      (node (ref "CD06") (pin "AN2") (pinfunction "P$2_AN2") (pintype "bidirectional"))
      (node (ref "CD06") (pin "AT1") (pinfunction "P$2_AT1") (pintype "bidirectional"))
      (node (ref "CD06") (pin "AT2") (pinfunction "P$2_AT2") (pintype "bidirectional"))
      (node (ref "CD06") (pin "BC1") (pinfunction "P$2_BC1") (pintype "bidirectional"))
      (node (ref "CD06") (pin "BC2") (pinfunction "P$2_BC2") (pintype "bidirectional"))
      (node (ref "CD06") (pin "BF1") (pinfunction "P$2_BF1") (pintype "bidirectional"))
      (node (ref "CD06") (pin "BF2") (pinfunction "P$2_BF2") (pintype "bidirectional"))
      (node (ref "CD06") (pin "BN1") (pinfunction "P$2_BN1") (pintype "bidirectional"))
      (node (ref "CD06") (pin "BN2") (pinfunction "P$2_BN2") (pintype "bidirectional"))
      (node (ref "CD06") (pin "BT1") (pinfunction "P$2_BT1") (pintype "bidirectional"))
      (node (ref "CD06") (pin "BT2") (pinfunction "P$2_BT2") (pintype "bidirectional"))
      (node (ref "CD07") (pin "AC1") (pinfunction "P$2_AC1") (pintype "bidirectional"))
      (node (ref "CD07") (pin "AC2") (pinfunction "P$2_AC2") (pintype "bidirectional"))
      (node (ref "CD07") (pin "AF1") (pinfunction "P$2_AF1") (pintype "bidirectional"))
      (node (ref "CD07") (pin "AF2") (pinfunction "P$2_AF2") (pintype "bidirectional"))
      (node (ref "CD07") (pin "AN1") (pinfunction "P$2_AN1") (pintype "bidirectional"))
      (node (ref "CD07") (pin "AN2") (pinfunction "P$2_AN2") (pintype "bidirectional"))
      (node (ref "CD07") (pin "AT1") (pinfunction "P$2_AT1") (pintype "bidirectional"))
      (node (ref "CD07") (pin "AT2") (pinfunction "P$2_AT2") (pintype "bidirectional"))
      (node (ref "CD07") (pin "BC1") (pinfunction "P$2_BC1") (pintype "bidirectional"))
      (node (ref "CD07") (pin "BC2") (pinfunction "P$2_BC2") (pintype "bidirectional"))
      (node (ref "CD07") (pin "BF1") (pinfunction "P$2_BF1") (pintype "bidirectional"))
      (node (ref "CD07") (pin "BF2") (pinfunction "P$2_BF2") (pintype "bidirectional"))
      (node (ref "CD07") (pin "BN1") (pinfunction "P$2_BN1") (pintype "bidirectional"))
      (node (ref "CD07") (pin "BN2") (pinfunction "P$2_BN2") (pintype "bidirectional"))
      (node (ref "CD07") (pin "BT1") (pinfunction "P$2_BT1") (pintype "bidirectional"))
      (node (ref "CD07") (pin "BT2") (pinfunction "P$2_BT2") (pintype "bidirectional"))
      (node (ref "D11") (pin "C1") (pinfunction "D_C1") (pintype "input"))
      (node (ref "D11") (pin "E2") (pinfunction "D_E2") (pintype "input"))
      (node (ref "D11") (pin "J1") (pinfunction "D_J1") (pintype "input"))
      (node (ref "D12") (pin "C1") (pinfunction "D_C1") (pintype "input"))
      (node (ref "D12") (pin "J1") (pinfunction "D_J1") (pintype "input"))
      (node (ref "D14") (pin "C1") (pinfunction "D_C1") (pintype "input"))
      (node (ref "D14") (pin "E2") (pinfunction "D_E2") (pintype "input"))
      (node (ref "D14") (pin "J1") (pinfunction "D_J1") (pintype "input"))
      (node (ref "D14") (pin "M2") (pinfunction "D_M2") (pintype "input"))
      (node (ref "D14") (pin "P1") (pinfunction "D_P1") (pintype "input"))
      (node (ref "D14") (pin "T2") (pinfunction "D_T2") (pintype "input"))
    )
    (net (code "98") (name "IB0") (class "Default")
      (node (ref "D09") (pin "H1") (pinfunction "IN1B_H1") (pintype "input"))
      (node (ref "D10") (pin "M2") (pinfunction "D_M2") (pintype "input"))
      (node (ref "D11") (pin "P2") (pinfunction "1_P2") (pintype "output"))
    )
    (net (code "99") (name "IB1") (class "Default")
      (node (ref "D09") (pin "M1") (pinfunction "IN1A_M1") (pintype "input"))
      (node (ref "D10") (pin "P1") (pinfunction "D_P1") (pintype "input"))
      (node (ref "D11") (pin "S1") (pinfunction "1_S1") (pintype "output"))
    )
    (net (code "100") (name "IB2") (class "Default")
      (node (ref "C10") (pin "D1") (pinfunction "IN1_D1") (pintype "input"))
      (node (ref "D10") (pin "T2") (pinfunction "D_T2") (pintype "input"))
      (node (ref "D11") (pin "V2") (pinfunction "1_V2") (pintype "output"))
    )
    (net (code "101") (name "IBD0") (class "Default")
      (node (ref "C11") (pin "F2") (pinfunction "OUT_F2") (pintype "output"))
      (node (ref "D11") (pin "M2") (pinfunction "D_M2") (pintype "input"))
    )
    (net (code "102") (name "IBD1") (class "Default")
      (node (ref "C11") (pin "S1") (pinfunction "OUT_S1") (pintype "output"))
      (node (ref "D11") (pin "P1") (pinfunction "D_P1") (pintype "input"))
    )
    (net (code "103") (name "IBD2") (class "Default")
      (node (ref "C12") (pin "F2") (pinfunction "OUT_F2") (pintype "output"))
      (node (ref "D11") (pin "T2") (pinfunction "D_T2") (pintype "input"))
    )
    (net (code "104") (name "IBIF_ENA") (class "Default")
      (node (ref "D08") (pin "J2") (pinfunction "OUT_J2") (pintype "output"))
      (node (ref "D09") (pin "F2") (pinfunction "IN2A_F2") (pintype "input"))
      (node (ref "D09") (pin "M2") (pinfunction "IN2A_M2") (pintype "input"))
      (node (ref "D09") (pin "T2") (pinfunction "IN2A_T2") (pintype "input"))
    )
    (net (code "105") (name "IB_ENA") (class "Default")
      (node (ref "C10") (pin "E1") (pinfunction "IN2_E1") (pintype "input"))
      (node (ref "D08") (pin "E1") (pinfunction "OUT_E1") (pintype "output"))
      (node (ref "D09") (pin "F1") (pinfunction "IN1A_F1") (pintype "input"))
      (node (ref "D09") (pin "N1") (pinfunction "IN1B_N1") (pintype "input"))
    )
    (net (code "106") (name "IF0") (class "Default")
      (node (ref "D09") (pin "K1") (pinfunction "IN2B_K1") (pintype "input"))
      (node (ref "D10") (pin "P2") (pinfunction "1_P2") (pintype "output"))
      (node (ref "D13") (pin "C1") (pinfunction "D_C1") (pintype "input"))
    )
    (net (code "107") (name "IF1") (class "Default")
      (node (ref "D09") (pin "P1") (pinfunction "IN2A_P1") (pintype "input"))
      (node (ref "D10") (pin "S1") (pinfunction "1_S1") (pintype "output"))
      (node (ref "D13") (pin "J1") (pinfunction "D_J1") (pintype "input"))
    )
    (net (code "108") (name "IF2") (class "Default")
      (node (ref "C10") (pin "D2") (pinfunction "IN1_D2") (pintype "input"))
      (node (ref "C13") (pin "A1") (pinfunction "IN1_A1") (pintype "input"))
      (node (ref "D10") (pin "V2") (pinfunction "1_V2") (pintype "output"))
      (node (ref "D13") (pin "P1") (pinfunction "D_P1") (pintype "input"))
    )
    (net (code "109") (name "IF_ENA") (class "Default")
      (node (ref "C10") (pin "C1") (pinfunction "OUT_C1") (pintype "output"))
      (node (ref "C10") (pin "E2") (pinfunction "IN2_E2") (pintype "input"))
      (node (ref "D08") (pin "D1") (pinfunction "IN_D1") (pintype "input"))
      (node (ref "D09") (pin "J1") (pinfunction "IN2A_J1") (pintype "input"))
      (node (ref "D09") (pin "R1") (pinfunction "IN2B_R1") (pintype "input"))
    )
    (net (code "110") (name "INHIBIT") (class "Default")
      (node (ref "AB02") (pin "AP2") (pinfunction "P$2_AP2") (pintype "bidirectional"))
      (node (ref "AB03") (pin "AP2") (pinfunction "P$2_AP2") (pintype "bidirectional"))
      (node (ref "AB04") (pin "AP2") (pinfunction "P$2_AP2") (pintype "bidirectional"))
      (node (ref "AB05") (pin "AP2") (pinfunction "P$2_AP2") (pintype "bidirectional"))
      (node (ref "AB06") (pin "AP2") (pinfunction "P$2_AP2") (pintype "bidirectional"))
      (node (ref "AB07") (pin "AP2") (pinfunction "P$2_AP2") (pintype "bidirectional"))
      (node (ref "C08") (pin "S1") (pinfunction "OUT_S1") (pintype "output"))
    )
    (net (code "111") (name "INTH") (class "Default")
      (node (ref "D08") (pin "L1") (pinfunction "IN_L1") (pintype "input"))
      (node (ref "D12") (pin "E1") (pinfunction "1_E1") (pintype "output"))
    )
    (net (code "112") (name "JMP_OR_JMS") (class "Default")
      (node (ref "C09") (pin "U2") (pinfunction "IN2_U2") (pintype "input"))
      (node (ref "C10") (pin "B1") (pinfunction "IN2_B1") (pintype "input"))
      (node (ref "C18") (pin "E2") (pinfunction "P$2_E2") (pintype "bidirectional"))
      (node (ref "D18") (pin "E2") (pinfunction "P$2_E2") (pintype "bidirectional"))
    )
    (net (code "113") (name "KEY_DF0") (class "Default")
      (node (ref "C12") (pin "L2") (pinfunction "IN1_L2") (pintype "input"))
      (node (ref "CD01") (pin "AJ2") (pinfunction "P$2_AJ2") (pintype "bidirectional"))
      (node (ref "CD02") (pin "AJ2") (pinfunction "P$2_AJ2") (pintype "bidirectional"))
      (node (ref "CD03") (pin "AJ2") (pinfunction "P$2_AJ2") (pintype "bidirectional"))
      (node (ref "CD04") (pin "AJ2") (pinfunction "P$2_AJ2") (pintype "bidirectional"))
      (node (ref "CD05") (pin "AJ2") (pinfunction "P$2_AJ2") (pintype "bidirectional"))
      (node (ref "CD06") (pin "AJ2") (pinfunction "P$2_AJ2") (pintype "bidirectional"))
      (node (ref "CD07") (pin "AJ2") (pinfunction "P$2_AJ2") (pintype "bidirectional"))
    )
    (net (code "114") (name "KEY_DF1") (class "Default")
      (node (ref "C12") (pin "P2") (pinfunction "IN1_P2") (pintype "input"))
      (node (ref "CD01") (pin "AH2") (pinfunction "P$2_AH2") (pintype "bidirectional"))
      (node (ref "CD02") (pin "AH2") (pinfunction "P$2_AH2") (pintype "bidirectional"))
      (node (ref "CD03") (pin "AH2") (pinfunction "P$2_AH2") (pintype "bidirectional"))
      (node (ref "CD04") (pin "AH2") (pinfunction "P$2_AH2") (pintype "bidirectional"))
      (node (ref "CD05") (pin "AH2") (pinfunction "P$2_AH2") (pintype "bidirectional"))
      (node (ref "CD06") (pin "AH2") (pinfunction "P$2_AH2") (pintype "bidirectional"))
      (node (ref "CD07") (pin "AH2") (pinfunction "P$2_AH2") (pintype "bidirectional"))
    )
    (net (code "115") (name "KEY_DF2") (class "Default")
      (node (ref "A09") (pin "K1") (pinfunction "OUT_K1") (pintype "output"))
      (node (ref "C13") (pin "D2") (pinfunction "IN1_D2") (pintype "input"))
    )
    (net (code "116") (name "KEY_IF0") (class "Default")
      (node (ref "C12") (pin "L1") (pinfunction "IN1_L1") (pintype "input"))
      (node (ref "CD01") (pin "AE2") (pinfunction "P$2_AE2") (pintype "bidirectional"))
      (node (ref "CD02") (pin "AE2") (pinfunction "P$2_AE2") (pintype "bidirectional"))
      (node (ref "CD03") (pin "AE2") (pinfunction "P$2_AE2") (pintype "bidirectional"))
      (node (ref "CD04") (pin "AE2") (pinfunction "P$2_AE2") (pintype "bidirectional"))
      (node (ref "CD05") (pin "AE2") (pinfunction "P$2_AE2") (pintype "bidirectional"))
      (node (ref "CD06") (pin "AE2") (pinfunction "P$2_AE2") (pintype "bidirectional"))
      (node (ref "CD07") (pin "AE2") (pinfunction "P$2_AE2") (pintype "bidirectional"))
    )
    (net (code "117") (name "KEY_IF1") (class "Default")
      (node (ref "C12") (pin "P1") (pinfunction "IN1_P1") (pintype "input"))
      (node (ref "CD01") (pin "AD2") (pinfunction "P$2_AD2") (pintype "bidirectional"))
      (node (ref "CD02") (pin "AD2") (pinfunction "P$2_AD2") (pintype "bidirectional"))
      (node (ref "CD03") (pin "AD2") (pinfunction "P$2_AD2") (pintype "bidirectional"))
      (node (ref "CD04") (pin "AD2") (pinfunction "P$2_AD2") (pintype "bidirectional"))
      (node (ref "CD05") (pin "AD2") (pinfunction "P$2_AD2") (pintype "bidirectional"))
      (node (ref "CD06") (pin "AD2") (pinfunction "P$2_AD2") (pintype "bidirectional"))
      (node (ref "CD07") (pin "AD2") (pinfunction "P$2_AD2") (pintype "bidirectional"))
    )
    (net (code "118") (name "KEY_IF2") (class "Default")
      (node (ref "A09") (pin "F2") (pinfunction "OUT_F2") (pintype "output"))
      (node (ref "C12") (pin "T2") (pinfunction "IN1_T2") (pintype "input"))
    )
    (net (code "119") (name "KEY_LOAD") (class "Default")
      (node (ref "A09") (pin "H1") (pinfunction "OUT_H1") (pintype "output"))
      (node (ref "C12") (pin "M1") (pinfunction "IN2_M1") (pintype "input"))
      (node (ref "C12") (pin "M2") (pinfunction "IN2_M2") (pintype "input"))
      (node (ref "C12") (pin "R1") (pinfunction "IN2_R1") (pintype "input"))
      (node (ref "C12") (pin "R2") (pinfunction "IN2_R2") (pintype "input"))
      (node (ref "C12") (pin "U2") (pinfunction "IN2_U2") (pintype "input"))
      (node (ref "C13") (pin "E2") (pinfunction "IN2_E2") (pintype "input"))
    )
    (net (code "120") (name "LINE_LOW") (class "Default")
      (node (ref "C18") (pin "V2") (pinfunction "P$2_V2") (pintype "bidirectional"))
      (node (ref "D18") (pin "V2") (pinfunction "P$2_V2") (pintype "bidirectional"))
    )
    (net (code "121") (name "LOAD_DF") (class "Default")
      (node (ref "C13") (pin "S1") (pinfunction "OUT_S1") (pintype "output"))
      (node (ref "D12") (pin "L2") (pinfunction "C_L2") (pintype "input"))
      (node (ref "D12") (pin "N1") (pinfunction "C_N1") (pintype "input"))
      (node (ref "D12") (pin "S2") (pinfunction "C_S2") (pintype "input"))
    )
    (net (code "122") (name "LOAD_IB") (class "Default")
      (node (ref "C13") (pin "S2") (pinfunction "OUT_S2") (pintype "output"))
      (node (ref "D08") (pin "J1") (pinfunction "IN_J1") (pintype "input"))
      (node (ref "D11") (pin "L2") (pinfunction "C_L2") (pintype "input"))
      (node (ref "D11") (pin "N1") (pinfunction "C_N1") (pintype "input"))
      (node (ref "D11") (pin "S2") (pinfunction "C_S2") (pintype "input"))
    )
    (net (code "123") (name "LOAD_IF") (class "Default")
      (node (ref "D08") (pin "L2") (pinfunction "OUT_L2") (pintype "output"))
      (node (ref "D10") (pin "L2") (pinfunction "C_L2") (pintype "input"))
      (node (ref "D10") (pin "N1") (pinfunction "C_N1") (pintype "input"))
      (node (ref "D10") (pin "S2") (pinfunction "C_S2") (pintype "input"))
    )
    (net (code "124") (name "MB_PARITY_ODD") (class "Default")
      (node (ref "C19") (pin "M2") (pinfunction "P$2_M2") (pintype "bidirectional"))
      (node (ref "D19") (pin "M2") (pinfunction "P$2_M2") (pintype "bidirectional"))
    )
    (net (code "125") (name "MEM00") (class "Default")
      (node (ref "B11") (pin "D1") (pinfunction "D_D1") (pintype "open_collector"))
      (node (ref "C19") (pin "D1") (pinfunction "P$2_D1") (pintype "bidirectional"))
      (node (ref "D19") (pin "D1") (pinfunction "P$2_D1") (pintype "bidirectional"))
    )
    (net (code "126") (name "MEM01") (class "Default")
      (node (ref "B11") (pin "E1") (pinfunction "E_E1") (pintype "open_collector"))
      (node (ref "C19") (pin "E1") (pinfunction "P$2_E1") (pintype "bidirectional"))
      (node (ref "D19") (pin "E1") (pinfunction "P$2_E1") (pintype "bidirectional"))
    )
    (net (code "127") (name "MEM02") (class "Default")
      (node (ref "B11") (pin "K1") (pinfunction "D_K1") (pintype "open_collector"))
      (node (ref "C19") (pin "H1") (pinfunction "P$2_H1") (pintype "bidirectional"))
      (node (ref "D19") (pin "H1") (pinfunction "P$2_H1") (pintype "bidirectional"))
    )
    (net (code "128") (name "MEM03") (class "Default")
      (node (ref "B11") (pin "L1") (pinfunction "E_L1") (pintype "open_collector"))
      (node (ref "C19") (pin "J1") (pinfunction "P$2_J1") (pintype "bidirectional"))
      (node (ref "D19") (pin "J1") (pinfunction "P$2_J1") (pintype "bidirectional"))
    )
    (net (code "129") (name "MEM04") (class "Default")
      (node (ref "B11") (pin "R1") (pinfunction "D_R1") (pintype "open_collector"))
      (node (ref "C19") (pin "L1") (pinfunction "P$2_L1") (pintype "bidirectional"))
      (node (ref "D19") (pin "L1") (pinfunction "P$2_L1") (pintype "bidirectional"))
    )
    (net (code "130") (name "MEM05") (class "Default")
      (node (ref "B11") (pin "S1") (pinfunction "E_S1") (pintype "open_collector"))
      (node (ref "C19") (pin "M1") (pinfunction "P$2_M1") (pintype "bidirectional"))
      (node (ref "D19") (pin "M1") (pinfunction "P$2_M1") (pintype "bidirectional"))
    )
    (net (code "131") (name "MEM06") (class "Default")
      (node (ref "B11") (pin "H2") (pinfunction "D_H2") (pintype "open_collector"))
      (node (ref "C19") (pin "P1") (pinfunction "P$2_P1") (pintype "bidirectional"))
      (node (ref "D19") (pin "P1") (pinfunction "P$2_P1") (pintype "bidirectional"))
    )
    (net (code "132") (name "MEM07") (class "Default")
      (node (ref "B11") (pin "J2") (pinfunction "E_J2") (pintype "open_collector"))
      (node (ref "C19") (pin "S1") (pinfunction "P$2_S1") (pintype "bidirectional"))
      (node (ref "D19") (pin "S1") (pinfunction "P$2_S1") (pintype "bidirectional"))
    )
    (net (code "133") (name "MEM08") (class "Default")
      (node (ref "B11") (pin "N2") (pinfunction "D_N2") (pintype "open_collector"))
      (node (ref "C19") (pin "D2") (pinfunction "P$2_D2") (pintype "bidirectional"))
      (node (ref "D19") (pin "D2") (pinfunction "P$2_D2") (pintype "bidirectional"))
    )
    (net (code "134") (name "MEM09") (class "Default")
      (node (ref "B11") (pin "P2") (pinfunction "E_P2") (pintype "open_collector"))
      (node (ref "C19") (pin "E2") (pinfunction "P$2_E2") (pintype "bidirectional"))
      (node (ref "D19") (pin "E2") (pinfunction "P$2_E2") (pintype "bidirectional"))
    )
    (net (code "135") (name "MEM10") (class "Default")
      (node (ref "B11") (pin "U2") (pinfunction "D_U2") (pintype "open_collector"))
      (node (ref "C19") (pin "H2") (pinfunction "P$2_H2") (pintype "bidirectional"))
      (node (ref "D19") (pin "H2") (pinfunction "P$2_H2") (pintype "bidirectional"))
    )
    (net (code "136") (name "MEM11") (class "Default")
      (node (ref "B11") (pin "V2") (pinfunction "E_V2") (pintype "open_collector"))
      (node (ref "C19") (pin "K2") (pinfunction "P$2_K2") (pintype "bidirectional"))
      (node (ref "D19") (pin "K2") (pinfunction "P$2_K2") (pintype "bidirectional"))
    )
    (net (code "137") (name "MEM_P") (class "Default")
      (node (ref "C19") (pin "B1") (pinfunction "P$2_B1") (pintype "bidirectional"))
      (node (ref "D19") (pin "B1") (pinfunction "P$2_B1") (pintype "bidirectional"))
    )
    (net (code "138") (name "MEM_START") (class "Default")
      (node (ref "C15") (pin "B1") (pinfunction "C_B1") (pintype "input"))
      (node (ref "C15") (pin "D2") (pinfunction "C_D2") (pintype "input"))
      (node (ref "C15") (pin "H1") (pinfunction "C_H1") (pintype "input"))
      (node (ref "C20") (pin "P2") (pinfunction "P$2_P2") (pintype "bidirectional"))
      (node (ref "D08") (pin "S2") (pinfunction "IN_S2") (pintype "input"))
      (node (ref "D12") (pin "D2") (pinfunction "C_D2") (pintype "input"))
      (node (ref "D20") (pin "P2") (pinfunction "P$2_P2") (pintype "bidirectional"))
    )
    (net (code "139") (name "NOT_FLD0") (class "Default")
      (node (ref "C09") (pin "N1") (pinfunction "OUT_N1") (pintype "output"))
      (node (ref "C14") (pin "D2") (pinfunction "IN1_D2") (pintype "input"))
      (node (ref "C16") (pin "A1") (pinfunction "IN1_A1") (pintype "input"))
      (node (ref "C17") (pin "D2") (pinfunction "P$2_D2") (pintype "bidirectional"))
    )
    (net (code "140") (name "Net-(A08A-OUT)") (class "Default")
      (node (ref "A08") (pin "E1") (pinfunction "OUT_E1") (pintype "output"))
      (node (ref "B10") (pin "P2") (pinfunction "IN_P2") (pintype "input"))
    )
    (net (code "141") (name "Net-(A08E-OUT)") (class "Default")
      (node (ref "A08") (pin "L1") (pinfunction "OUT_L1") (pintype "output"))
      (node (ref "B10") (pin "V1") (pinfunction "IN_V1") (pintype "input"))
    )
    (net (code "142") (name "Net-(A10A-0)") (class "Default")
      (node (ref "A10") (pin "F1") (pinfunction "0_F1") (pintype "output"))
      (node (ref "B11") (pin "A1") (pinfunction "A_A1") (pintype "input"))
    )
    (net (code "143") (name "Net-(A10A-C)") (class "Default")
      (node (ref "A10") (pin "B1") (pinfunction "C_B1") (pintype "input"))
      (node (ref "A10") (pin "D2") (pinfunction "C_D2") (pintype "input"))
      (node (ref "A10") (pin "H1") (pinfunction "C_H1") (pintype "input"))
      (node (ref "A10") (pin "L2") (pinfunction "C_L2") (pintype "input"))
      (node (ref "A10") (pin "N1") (pinfunction "C_N1") (pintype "input"))
      (node (ref "A10") (pin "S2") (pinfunction "C_S2") (pintype "input"))
      (node (ref "B09") (pin "B1") (pinfunction "C_B1") (pintype "input"))
      (node (ref "B09") (pin "D2") (pinfunction "C_D2") (pintype "input"))
      (node (ref "B09") (pin "H1") (pinfunction "C_H1") (pintype "input"))
      (node (ref "B09") (pin "L2") (pinfunction "C_L2") (pintype "input"))
      (node (ref "B09") (pin "N1") (pinfunction "C_N1") (pintype "input"))
      (node (ref "B09") (pin "S2") (pinfunction "C_S2") (pintype "input"))
      (node (ref "C14") (pin "E1") (pinfunction "OUT_E1") (pintype "output"))
    )
    (net (code "144") (name "Net-(A10A-D)") (class "Default")
      (node (ref "A10") (pin "C1") (pinfunction "D_C1") (pintype "input"))
      (node (ref "B08") (pin "D1") (pinfunction "D_D1") (pintype "open_collector"))
    )
    (net (code "145") (name "Net-(A10A-R)") (class "Default")
      (node (ref "A10") (pin "A1") (pinfunction "R_A1") (pintype "input"))
      (node (ref "A10") (pin "K2") (pinfunction "R_K2") (pintype "input"))
      (node (ref "B09") (pin "A1") (pinfunction "R_A1") (pintype "input"))
      (node (ref "B09") (pin "K2") (pinfunction "R_K2") (pintype "input"))
      (node (ref "C14") (pin "L1") (pinfunction "OUT_L1") (pintype "output"))
    )
    (net (code "146") (name "Net-(A10D-0)") (class "Default")
      (node (ref "A10") (pin "J2") (pinfunction "0_J2") (pintype "output"))
      (node (ref "B11") (pin "B1") (pinfunction "B_B1") (pintype "input"))
    )
    (net (code "147") (name "Net-(A10D-D)") (class "Default")
      (node (ref "A10") (pin "E2") (pinfunction "D_E2") (pintype "input"))
      (node (ref "B08") (pin "E1") (pinfunction "E_E1") (pintype "open_collector"))
    )
    (net (code "148") (name "Net-(A10E-0)") (class "Default")
      (node (ref "A10") (pin "M1") (pinfunction "0_M1") (pintype "output"))
      (node (ref "B11") (pin "F1") (pinfunction "A_F1") (pintype "input"))
    )
    (net (code "149") (name "Net-(A10E-D)") (class "Default")
      (node (ref "A10") (pin "J1") (pinfunction "D_J1") (pintype "input"))
      (node (ref "B08") (pin "K1") (pinfunction "D_K1") (pintype "open_collector"))
    )
    (net (code "150") (name "Net-(A10F-0)") (class "Default")
      (node (ref "A10") (pin "R2") (pinfunction "0_R2") (pintype "output"))
      (node (ref "B11") (pin "H1") (pinfunction "B_H1") (pintype "input"))
    )
    (net (code "151") (name "Net-(A10F-D)") (class "Default")
      (node (ref "A10") (pin "M2") (pinfunction "D_M2") (pintype "input"))
      (node (ref "B08") (pin "L1") (pinfunction "E_L1") (pintype "open_collector"))
    )
    (net (code "152") (name "Net-(A10G-0)") (class "Default")
      (node (ref "A10") (pin "U1") (pinfunction "0_U1") (pintype "output"))
      (node (ref "B11") (pin "M1") (pinfunction "A_M1") (pintype "input"))
    )
    (net (code "153") (name "Net-(A10G-D)") (class "Default")
      (node (ref "A10") (pin "P1") (pinfunction "D_P1") (pintype "input"))
      (node (ref "B08") (pin "R1") (pinfunction "D_R1") (pintype "open_collector"))
    )
    (net (code "154") (name "Net-(A10H-0)") (class "Default")
      (node (ref "A10") (pin "V1") (pinfunction "0_V1") (pintype "output"))
      (node (ref "B11") (pin "N1") (pinfunction "B_N1") (pintype "input"))
    )
    (net (code "155") (name "Net-(A10H-D)") (class "Default")
      (node (ref "A10") (pin "T2") (pinfunction "D_T2") (pintype "input"))
      (node (ref "B08") (pin "S1") (pinfunction "E_S1") (pintype "open_collector"))
    )
    (net (code "156") (name "Net-(A14I-A)") (class "Default")
      (node (ref "A14") (pin "M1") (pinfunction "A_M1") (pintype "input"))
      (node (ref "C13") (pin "C1") (pinfunction "OUT_C1") (pintype "output"))
    )
    (net (code "157") (name "Net-(A14I-B)") (class "Default")
      (node (ref "A14") (pin "N1") (pinfunction "B_N1") (pintype "input"))
      (node (ref "C13") (pin "F1") (pinfunction "OUT_F1") (pintype "output"))
    )
    (net (code "158") (name "Net-(A18AD-P$2)") (class "Default")
      (node (ref "A18") (pin "T2") (pinfunction "P$2_T2") (pintype "bidirectional"))
      (node (ref "B18") (pin "T2") (pinfunction "P$2_T2") (pintype "bidirectional"))
    )
    (net (code "159") (name "Net-(A18AF-P$2)") (class "Default")
      (node (ref "A18") (pin "V2") (pinfunction "P$2_V2") (pintype "bidirectional"))
      (node (ref "B18") (pin "V2") (pinfunction "P$2_V2") (pintype "bidirectional"))
    )
    (net (code "160") (name "Net-(B08A-C)") (class "Default")
      (node (ref "B08") (pin "C1") (pinfunction "C_C1") (pintype "input"))
      (node (ref "B08") (pin "F2") (pinfunction "C_F2") (pintype "input"))
      (node (ref "B08") (pin "J1") (pinfunction "C_J1") (pintype "input"))
      (node (ref "B08") (pin "M2") (pinfunction "C_M2") (pintype "input"))
      (node (ref "B08") (pin "P1") (pinfunction "C_P1") (pintype "input"))
      (node (ref "B08") (pin "T2") (pinfunction "C_T2") (pintype "input"))
      (node (ref "B14") (pin "J2") (pinfunction "OUT_J2") (pintype "output"))
    )
    (net (code "161") (name "Net-(B08F-D)") (class "Default")
      (node (ref "B08") (pin "H2") (pinfunction "D_H2") (pintype "open_collector"))
      (node (ref "B09") (pin "C1") (pinfunction "D_C1") (pintype "input"))
    )
    (net (code "162") (name "Net-(B08F-E)") (class "Default")
      (node (ref "B08") (pin "J2") (pinfunction "E_J2") (pintype "open_collector"))
      (node (ref "B09") (pin "E2") (pinfunction "D_E2") (pintype "input"))
    )
    (net (code "163") (name "Net-(B08H-D)") (class "Default")
      (node (ref "B08") (pin "N2") (pinfunction "D_N2") (pintype "open_collector"))
      (node (ref "B09") (pin "J1") (pinfunction "D_J1") (pintype "input"))
    )
    (net (code "164") (name "Net-(B08H-E)") (class "Default")
      (node (ref "B08") (pin "P2") (pinfunction "E_P2") (pintype "open_collector"))
      (node (ref "B09") (pin "M2") (pinfunction "D_M2") (pintype "input"))
    )
    (net (code "165") (name "Net-(B08J-D)") (class "Default")
      (node (ref "B08") (pin "U2") (pinfunction "D_U2") (pintype "open_collector"))
      (node (ref "B09") (pin "P1") (pinfunction "D_P1") (pintype "input"))
    )
    (net (code "166") (name "Net-(B08J-E)") (class "Default")
      (node (ref "B08") (pin "V2") (pinfunction "E_V2") (pintype "open_collector"))
      (node (ref "B09") (pin "T2") (pinfunction "D_T2") (pintype "input"))
    )
    (net (code "167") (name "Net-(B09A-0)") (class "Default")
      (node (ref "B09") (pin "F1") (pinfunction "0_F1") (pintype "output"))
      (node (ref "B11") (pin "D2") (pinfunction "A_D2") (pintype "input"))
    )
    (net (code "168") (name "Net-(B09D-0)") (class "Default")
      (node (ref "B09") (pin "J2") (pinfunction "0_J2") (pintype "output"))
      (node (ref "B11") (pin "E2") (pinfunction "B_E2") (pintype "input"))
    )
    (net (code "169") (name "Net-(B09E-0)") (class "Default")
      (node (ref "B09") (pin "M1") (pinfunction "0_M1") (pintype "output"))
      (node (ref "B11") (pin "K2") (pinfunction "A_K2") (pintype "input"))
    )
    (net (code "170") (name "Net-(B09F-0)") (class "Default")
      (node (ref "B09") (pin "R2") (pinfunction "0_R2") (pintype "output"))
      (node (ref "B11") (pin "L2") (pinfunction "B_L2") (pintype "input"))
    )
    (net (code "171") (name "Net-(B09G-0)") (class "Default")
      (node (ref "B09") (pin "U1") (pinfunction "0_U1") (pintype "output"))
      (node (ref "B11") (pin "R2") (pinfunction "A_R2") (pintype "input"))
    )
    (net (code "172") (name "Net-(B09H-0)") (class "Default")
      (node (ref "B09") (pin "V1") (pinfunction "0_V1") (pintype "output"))
      (node (ref "B11") (pin "S2") (pinfunction "B_S2") (pintype "input"))
    )
    (net (code "173") (name "Net-(B10R-OUT)") (class "Default")
      (node (ref "B10") (pin "V2") (pinfunction "OUT_V2") (pintype "output"))
      (node (ref "C13") (pin "H1") (pinfunction "IN1_H1") (pintype "input"))
    )
    (net (code "174") (name "Net-(B11A-C)") (class "Default")
      (node (ref "B11") (pin "C1") (pinfunction "C_C1") (pintype "input"))
      (node (ref "B11") (pin "F2") (pinfunction "C_F2") (pintype "input"))
      (node (ref "B11") (pin "J1") (pinfunction "C_J1") (pintype "input"))
      (node (ref "B11") (pin "M2") (pinfunction "C_M2") (pintype "input"))
      (node (ref "B11") (pin "P1") (pinfunction "C_P1") (pintype "input"))
      (node (ref "B11") (pin "T2") (pinfunction "C_T2") (pintype "input"))
      (node (ref "B14") (pin "P2") (pinfunction "OUT_P2") (pintype "output"))
    )
    (net (code "175") (name "Net-(B15J-A)") (class "Default")
      (node (ref "B15") (pin "R2") (pinfunction "A_R2") (pintype "input"))
      (node (ref "C09") (pin "U1") (pinfunction "OUT_U1") (pintype "output"))
    )
    (net (code "176") (name "Net-(C09D-OUT)") (class "Default")
      (node (ref "C09") (pin "H2") (pinfunction "OUT_H2") (pintype "output"))
      (node (ref "D14") (pin "N2") (pinfunction "S_N2") (pintype "input"))
    )
    (net (code "177") (name "Net-(C09E-OUT)") (class "Default")
      (node (ref "C09") (pin "J1") (pinfunction "OUT_J1") (pintype "output"))
      (node (ref "D08") (pin "H2") (pinfunction "IN_H2") (pintype "input"))
    )
    (net (code "178") (name "Net-(C09F-OUT)") (class "Default")
      (node (ref "C09") (pin "M2") (pinfunction "OUT_M2") (pintype "output"))
      (node (ref "D14") (pin "U2") (pinfunction "S_U2") (pintype "input"))
    )
    (net (code "179") (name "Net-(C09H-OUT)") (class "Default")
      (node (ref "C09") (pin "S2") (pinfunction "OUT_S2") (pintype "output"))
      (node (ref "D12") (pin "K1") (pinfunction "S_K1") (pintype "input"))
    )
    (net (code "180") (name "Net-(C10B-OUT)") (class "Default")
      (node (ref "C10") (pin "F1") (pinfunction "OUT_F1") (pintype "output"))
      (node (ref "C10") (pin "H1") (pinfunction "IN1_H1") (pintype "input"))
    )
    (net (code "181") (name "Net-(C10C-OUT)") (class "Default")
      (node (ref "C10") (pin "F2") (pinfunction "OUT_F2") (pintype "output"))
      (node (ref "C10") (pin "J1") (pinfunction "IN2_J1") (pintype "input"))
    )
    (net (code "182") (name "Net-(C10F-OUT)") (class "Default")
      (node (ref "C10") (pin "K1") (pinfunction "OUT_K1") (pintype "output"))
      (node (ref "D09") (pin "U2") (pinfunction "IN2B_U2") (pintype "input"))
    )
    (net (code "183") (name "Net-(C10G-OUT)") (class "Default")
      (node (ref "C10") (pin "K2") (pinfunction "OUT_K2") (pintype "output"))
      (node (ref "C10") (pin "L1") (pinfunction "IN1_L1") (pintype "input"))
    )
    (net (code "184") (name "Net-(C10H-IN2)") (class "Default")
      (node (ref "C10") (pin "M1") (pinfunction "IN2_M1") (pintype "input"))
      (node (ref "D09") (pin "J2") (pinfunction "OUT_J2") (pintype "output"))
    )
    (net (code "185") (name "Net-(C10I-OUT)") (class "Default")
      (node (ref "C10") (pin "N2") (pinfunction "OUT_N2") (pintype "output"))
      (node (ref "C10") (pin "P1") (pinfunction "IN1_P1") (pintype "input"))
    )
    (net (code "186") (name "Net-(C10J-IN2)") (class "Default")
      (node (ref "C10") (pin "R1") (pinfunction "IN2_R1") (pintype "input"))
      (node (ref "D09") (pin "P2") (pinfunction "OUT_P2") (pintype "output"))
    )
    (net (code "187") (name "Net-(C10K-OUT)") (class "Default")
      (node (ref "C10") (pin "S2") (pinfunction "OUT_S2") (pintype "output"))
      (node (ref "C10") (pin "T2") (pinfunction "IN1_T2") (pintype "input"))
    )
    (net (code "188") (name "Net-(C10N-IN2)") (class "Default")
      (node (ref "C10") (pin "U2") (pinfunction "IN2_U2") (pintype "input"))
      (node (ref "D09") (pin "V2") (pinfunction "OUT_V2") (pintype "output"))
    )
    (net (code "189") (name "Net-(C11A-OUT)") (class "Default")
      (node (ref "C11") (pin "C1") (pinfunction "OUT_C1") (pintype "output"))
      (node (ref "C11") (pin "D2") (pinfunction "IN1_D2") (pintype "input"))
    )
    (net (code "190") (name "Net-(C11B-OUT)") (class "Default")
      (node (ref "C11") (pin "E2") (pinfunction "IN2_E2") (pintype "input"))
      (node (ref "C11") (pin "F1") (pinfunction "OUT_F1") (pintype "output"))
      (node (ref "C11") (pin "H2") (pinfunction "IN1_H2") (pintype "input"))
    )
    (net (code "191") (name "Net-(C11F-OUT)") (class "Default")
      (node (ref "C11") (pin "J2") (pinfunction "IN2_J2") (pintype "input"))
      (node (ref "C11") (pin "K1") (pinfunction "OUT_K1") (pintype "output"))
    )
    (net (code "192") (name "Net-(C11H-OUT)") (class "Default")
      (node (ref "C11") (pin "N1") (pinfunction "OUT_N1") (pintype "output"))
      (node (ref "C11") (pin "P1") (pinfunction "IN1_P1") (pintype "input"))
    )
    (net (code "193") (name "Net-(C11I-OUT)") (class "Default")
      (node (ref "C11") (pin "N2") (pinfunction "OUT_N2") (pintype "output"))
      (node (ref "C11") (pin "R1") (pinfunction "IN2_R1") (pintype "input"))
      (node (ref "C11") (pin "T2") (pinfunction "IN1_T2") (pintype "input"))
    )
    (net (code "194") (name "Net-(C11K-OUT)") (class "Default")
      (node (ref "C11") (pin "S2") (pinfunction "OUT_S2") (pintype "output"))
      (node (ref "C11") (pin "U2") (pinfunction "IN2_U2") (pintype "input"))
    )
    (net (code "195") (name "Net-(C12A-OUT)") (class "Default")
      (node (ref "C12") (pin "C1") (pinfunction "OUT_C1") (pintype "output"))
      (node (ref "C12") (pin "D2") (pinfunction "IN1_D2") (pintype "input"))
    )
    (net (code "196") (name "Net-(C12B-OUT)") (class "Default")
      (node (ref "C12") (pin "E2") (pinfunction "IN2_E2") (pintype "input"))
      (node (ref "C12") (pin "F1") (pinfunction "OUT_F1") (pintype "output"))
      (node (ref "C12") (pin "H2") (pinfunction "IN1_H2") (pintype "input"))
    )
    (net (code "197") (name "Net-(C12F-OUT)") (class "Default")
      (node (ref "C12") (pin "J2") (pinfunction "IN2_J2") (pintype "input"))
      (node (ref "C12") (pin "K1") (pinfunction "OUT_K1") (pintype "output"))
    )
    (net (code "198") (name "Net-(C13F-OUT)") (class "Default")
      (node (ref "C13") (pin "K1") (pinfunction "OUT_K1") (pintype "output"))
      (node (ref "C14") (pin "M1") (pinfunction "IN1_M1") (pintype "input"))
    )
    (net (code "199") (name "Net-(C13G-OUT)") (class "Default")
      (node (ref "C13") (pin "K2") (pinfunction "OUT_K2") (pintype "output"))
      (node (ref "D15") (pin "H2") (pinfunction "H2_H2") (pintype "input"))
    )
    (net (code "200") (name "Net-(C13N-OUT)") (class "Default")
      (node (ref "C13") (pin "V2") (pinfunction "OUT_V2") (pintype "output"))
      (node (ref "D12") (pin "B1") (pinfunction "C_B1") (pintype "input"))
    )
    (net (code "201") (name "Net-(C14J-IN1)") (class "Default")
      (node (ref "C14") (pin "R2") (pinfunction "IN1_R2") (pintype "input"))
      (node (ref "C16") (pin "V1") (pinfunction "OUT_V1") (pintype "output"))
    )
    (net (code "202") (name "Net-(C16A-IN2)") (class "Default")
      (node (ref "C16") (pin "B1") (pinfunction "IN2_B1") (pintype "input"))
      (node (ref "C17") (pin "E2") (pinfunction "P$2_E2") (pintype "bidirectional"))
    )
    (net (code "203") (name "Net-(C16H-OUT)") (class "Default")
      (node (ref "C16") (pin "S2") (pinfunction "OUT_S2") (pintype "output"))
      (node (ref "D08") (pin "C1") (pinfunction "IN_C1") (pintype "input"))
    )
    (net (code "204") (name "Net-(C16J-IN1)") (class "Default")
      (node (ref "C16") (pin "T2") (pinfunction "IN1_T2") (pintype "input"))
      (node (ref "C17") (pin "K2") (pinfunction "P$2_K2") (pintype "bidirectional"))
    )
    (net (code "205") (name "Net-(C16J-IN2)") (class "Default")
      (node (ref "C16") (pin "U2") (pinfunction "IN2_U2") (pintype "input"))
      (node (ref "C17") (pin "P2") (pinfunction "P$2_P2") (pintype "bidirectional"))
    )
    (net (code "206") (name "Net-(C16J-IN3)") (class "Default")
      (node (ref "C16") (pin "V2") (pinfunction "IN3_V2") (pintype "input"))
      (node (ref "C17") (pin "U2") (pinfunction "P$2_U2") (pintype "bidirectional"))
    )
    (net (code "207") (name "Net-(C18P-P$2)") (class "Default")
      (node (ref "C18") (pin "K2") (pinfunction "P$2_K2") (pintype "bidirectional"))
      (node (ref "D18") (pin "K2") (pinfunction "P$2_K2") (pintype "bidirectional"))
    )
    (net (code "208") (name "Net-(C18T-P$2)") (class "Default")
      (node (ref "C18") (pin "M2") (pinfunction "P$2_M2") (pintype "bidirectional"))
      (node (ref "D18") (pin "M2") (pinfunction "P$2_M2") (pintype "bidirectional"))
    )
    (net (code "209") (name "Net-(C18X-P$2)") (class "Default")
      (node (ref "C18") (pin "P2") (pinfunction "P$2_P2") (pintype "bidirectional"))
      (node (ref "D18") (pin "P2") (pinfunction "P$2_P2") (pintype "bidirectional"))
    )
    (net (code "210") (name "Net-(C19AB-P$2)") (class "Default")
      (node (ref "C19") (pin "S2") (pinfunction "P$2_S2") (pintype "bidirectional"))
      (node (ref "D19") (pin "S2") (pinfunction "P$2_S2") (pintype "bidirectional"))
    )
    (net (code "211") (name "Net-(C19X-P$2)") (class "Default")
      (node (ref "C19") (pin "P2") (pinfunction "P$2_P2") (pintype "bidirectional"))
      (node (ref "D19") (pin "P2") (pinfunction "P$2_P2") (pintype "bidirectional"))
    )
    (net (code "212") (name "Net-(D08B-OUT)") (class "Default")
      (node (ref "D08") (pin "D2") (pinfunction "OUT_D2") (pintype "output"))
      (node (ref "D10") (pin "B1") (pinfunction "C_B1") (pintype "input"))
      (node (ref "D10") (pin "D2") (pinfunction "C_D2") (pintype "input"))
      (node (ref "D10") (pin "H1") (pinfunction "C_H1") (pintype "input"))
    )
    (net (code "213") (name "Net-(D08D-IN)") (class "Default")
      (node (ref "D08") (pin "E2") (pinfunction "IN_E2") (pintype "input"))
      (node (ref "D09") (pin "S1") (pinfunction "OUT_S1") (pintype "output"))
    )
    (net (code "214") (name "Net-(D08D-OUT)") (class "Default")
      (node (ref "D08") (pin "F2") (pinfunction "OUT_F2") (pintype "output"))
      (node (ref "D09") (pin "N2") (pinfunction "IN2B_N2") (pintype "input"))
    )
    (net (code "215") (name "Net-(D08G-IN)") (class "Default")
      (node (ref "D08") (pin "F1") (pinfunction "IN_F1") (pintype "input"))
      (node (ref "D09") (pin "L1") (pinfunction "OUT_L1") (pintype "output"))
    )
    (net (code "216") (name "Net-(D08G-OUT)") (class "Default")
      (node (ref "D08") (pin "H1") (pinfunction "OUT_H1") (pintype "output"))
      (node (ref "D09") (pin "H2") (pinfunction "IN2B_H2") (pintype "input"))
    )
    (net (code "217") (name "Net-(D15A-IN)") (class "Default")
      (node (ref "D15") (pin "E1") (pinfunction "IN_E1") (pintype "input"))
      (node (ref "D15") (pin "M2") (pinfunction "M2_M2") (pintype "output"))
    )
    (net (code "218") (name "Net-(D15E-IN)") (class "Default")
      (node (ref "D15") (pin "H1") (pinfunction "IN_H1") (pintype "input"))
      (node (ref "D15") (pin "R2") (pinfunction "R2_R2") (pintype "output"))
    )
    (net (code "219") (name "Net-(D16A-IN)") (class "Default")
      (node (ref "D16") (pin "E1") (pinfunction "IN_E1") (pintype "input"))
      (node (ref "D16") (pin "L2") (pinfunction "L2_L2") (pintype "output"))
    )
    (net (code "220") (name "Net-(D16E-IN)") (class "Default")
      (node (ref "D16") (pin "H1") (pinfunction "IN_H1") (pintype "input"))
      (node (ref "D16") (pin "M2") (pinfunction "M2_M2") (pintype "output"))
    )
    (net (code "221") (name "Net-(D17A-IN)") (class "Default")
      (node (ref "D17") (pin "E1") (pinfunction "IN_E1") (pintype "input"))
      (node (ref "D17") (pin "J2") (pinfunction "J2_J2") (pintype "output"))
    )
    (net (code "222") (name "Net-(D17E-IN)") (class "Default")
      (node (ref "D17") (pin "H1") (pinfunction "IN_H1") (pintype "input"))
      (node (ref "D17") (pin "M2") (pinfunction "M2_M2") (pintype "output"))
    )
    (net (code "223") (name "POWER_OK") (class "Default")
      (node (ref "C13") (pin "J1") (pinfunction "IN2_J1") (pintype "input"))
      (node (ref "C18") (pin "T2") (pinfunction "P$2_T2") (pintype "bidirectional"))
      (node (ref "D18") (pin "T2") (pinfunction "P$2_T2") (pintype "bidirectional"))
    )
    (net (code "224") (name "RDF") (class "Default")
      (node (ref "A09") (pin "D2") (pinfunction "OUT_D2") (pintype "output"))
      (node (ref "C13") (pin "E1") (pinfunction "IN2_E1") (pintype "input"))
    )
    (net (code "225") (name "READ") (class "Default")
      (node (ref "C09") (pin "E2") (pinfunction "IN2_E2") (pintype "input"))
      (node (ref "C09") (pin "F2") (pinfunction "IN3_F2") (pintype "input"))
      (node (ref "C09") (pin "P2") (pinfunction "IN2_P2") (pintype "input"))
      (node (ref "C09") (pin "R1") (pinfunction "IN2_R1") (pintype "input"))
      (node (ref "C09") (pin "R2") (pinfunction "IN3_R2") (pintype "input"))
      (node (ref "C09") (pin "S1") (pinfunction "IN3_S1") (pintype "input"))
      (node (ref "C16") (pin "R1") (pinfunction "IN2_R1") (pintype "input"))
      (node (ref "C16") (pin "S1") (pinfunction "IN3_S1") (pintype "input"))
      (node (ref "D14") (pin "E1") (pinfunction "1_E1") (pintype "output"))
    )
    (net (code "226") (name "RETURNH") (class "Default")
      (node (ref "AB02") (pin "AR2") (pinfunction "P$2_AR2") (pintype "bidirectional"))
      (node (ref "AB03") (pin "AR2") (pinfunction "P$2_AR2") (pintype "bidirectional"))
      (node (ref "AB04") (pin "AR2") (pinfunction "P$2_AR2") (pintype "bidirectional"))
      (node (ref "AB05") (pin "AR2") (pinfunction "P$2_AR2") (pintype "bidirectional"))
      (node (ref "AB06") (pin "AR2") (pinfunction "P$2_AR2") (pintype "bidirectional"))
      (node (ref "AB07") (pin "AR2") (pinfunction "P$2_AR2") (pintype "bidirectional"))
      (node (ref "C08") (pin "E1") (pinfunction "OUT_E1") (pintype "output"))
    )
    (net (code "227") (name "RIF") (class "Default")
      (node (ref "A09") (pin "B1") (pinfunction "OUT_B1") (pintype "output"))
      (node (ref "C13") (pin "B1") (pinfunction "IN2_B1") (pintype "input"))
    )
    (net (code "228") (name "SAVE_FIELD") (class "Default")
      (node (ref "A08") (pin "U2") (pinfunction "IN4_U2") (pintype "input"))
      (node (ref "B10") (pin "R2") (pinfunction "OUT_R2") (pintype "output"))
    )
    (net (code "229") (name "SELECT") (class "Default")
      (node (ref "B14") (pin "N2") (pinfunction "IN4_N2") (pintype "input"))
      (node (ref "D12") (pin "H2") (pinfunction "1_H2") (pintype "output"))
    )
    (net (code "230") (name "SF0") (class "Default")
      (node (ref "C11") (pin "A1") (pinfunction "IN1_A1") (pintype "input"))
      (node (ref "D13") (pin "E1") (pinfunction "1_E1") (pintype "output"))
    )
    (net (code "231") (name "SF1") (class "Default")
      (node (ref "C11") (pin "H1") (pinfunction "IN1_H1") (pintype "input"))
      (node (ref "D13") (pin "H2") (pinfunction "1_H2") (pintype "output"))
    )
    (net (code "232") (name "SF2") (class "Default")
      (node (ref "C11") (pin "L1") (pinfunction "IN1_L1") (pintype "input"))
      (node (ref "D13") (pin "L1") (pinfunction "1_L1") (pintype "output"))
    )
    (net (code "233") (name "SF3") (class "Default")
      (node (ref "C11") (pin "P2") (pinfunction "IN1_P2") (pintype "input"))
      (node (ref "D13") (pin "P2") (pinfunction "1_P2") (pintype "output"))
    )
    (net (code "234") (name "SF4") (class "Default")
      (node (ref "C12") (pin "A1") (pinfunction "IN1_A1") (pintype "input"))
      (node (ref "D13") (pin "S1") (pinfunction "1_S1") (pintype "output"))
    )
    (net (code "235") (name "SF5") (class "Default")
      (node (ref "C12") (pin "H1") (pinfunction "IN1_H1") (pintype "input"))
      (node (ref "D13") (pin "V2") (pinfunction "1_V2") (pintype "output"))
    )
    (net (code "236") (name "SOURCE") (class "Default")
      (node (ref "AB02") (pin "AL2") (pinfunction "P$2_AL2") (pintype "bidirectional"))
      (node (ref "AB03") (pin "AL2") (pinfunction "P$2_AL2") (pintype "bidirectional"))
      (node (ref "AB04") (pin "AL2") (pinfunction "P$2_AL2") (pintype "bidirectional"))
      (node (ref "AB05") (pin "AL2") (pinfunction "P$2_AL2") (pintype "bidirectional"))
      (node (ref "AB06") (pin "AL2") (pinfunction "P$2_AL2") (pintype "bidirectional"))
      (node (ref "AB07") (pin "AL2") (pinfunction "P$2_AL2") (pintype "bidirectional"))
      (node (ref "C08") (pin "L1") (pinfunction "OUT_L1") (pintype "output"))
    )
    (net (code "237") (name "STOP_OK") (class "Default")
      (node (ref "C18") (pin "S2") (pinfunction "P$2_S2") (pintype "bidirectional"))
      (node (ref "D18") (pin "S2") (pinfunction "P$2_S2") (pintype "bidirectional"))
    )
    (net (code "238") (name "STROBE") (class "Default")
      (node (ref "AB02") (pin "AM2") (pinfunction "P$2_AM2") (pintype "bidirectional"))
      (node (ref "AB03") (pin "AM2") (pinfunction "P$2_AM2") (pintype "bidirectional"))
      (node (ref "AB04") (pin "AM2") (pinfunction "P$2_AM2") (pintype "bidirectional"))
      (node (ref "AB05") (pin "AM2") (pinfunction "P$2_AM2") (pintype "bidirectional"))
      (node (ref "AB06") (pin "AM2") (pinfunction "P$2_AM2") (pintype "bidirectional"))
      (node (ref "AB07") (pin "AM2") (pinfunction "P$2_AM2") (pintype "bidirectional"))
      (node (ref "C08") (pin "P2") (pinfunction "OUT_P2") (pintype "output"))
    )
    (net (code "239") (name "VCC") (class "Default")
      (node (ref "AB01") (pin "AA2") (pinfunction "P$2_AA2") (pintype "bidirectional"))
      (node (ref "AB01") (pin "BA2") (pinfunction "P$2_BA2") (pintype "bidirectional"))
      (node (ref "AB02") (pin "AA2") (pinfunction "P$2_AA2") (pintype "bidirectional"))
      (node (ref "AB02") (pin "BA2") (pinfunction "P$2_BA2") (pintype "bidirectional"))
      (node (ref "AB03") (pin "AA2") (pinfunction "P$2_AA2") (pintype "bidirectional"))
      (node (ref "AB03") (pin "BA2") (pinfunction "P$2_BA2") (pintype "bidirectional"))
      (node (ref "AB04") (pin "AA2") (pinfunction "P$2_AA2") (pintype "bidirectional"))
      (node (ref "AB04") (pin "BA2") (pinfunction "P$2_BA2") (pintype "bidirectional"))
      (node (ref "AB05") (pin "AA2") (pinfunction "P$2_AA2") (pintype "bidirectional"))
      (node (ref "AB05") (pin "BA2") (pinfunction "P$2_BA2") (pintype "bidirectional"))
      (node (ref "AB06") (pin "AA2") (pinfunction "P$2_AA2") (pintype "bidirectional"))
      (node (ref "AB06") (pin "BA2") (pinfunction "P$2_BA2") (pintype "bidirectional"))
      (node (ref "AB07") (pin "AA2") (pinfunction "P$2_AA2") (pintype "bidirectional"))
      (node (ref "AB07") (pin "BA2") (pinfunction "P$2_BA2") (pintype "bidirectional"))
      (node (ref "CD01") (pin "AA2") (pinfunction "P$2_AA2") (pintype "bidirectional"))
      (node (ref "CD02") (pin "AA2") (pinfunction "P$2_AA2") (pintype "bidirectional"))
      (node (ref "CD03") (pin "AA2") (pinfunction "P$2_AA2") (pintype "bidirectional"))
      (node (ref "CD04") (pin "AA2") (pinfunction "P$2_AA2") (pintype "bidirectional"))
      (node (ref "CD05") (pin "AA2") (pinfunction "P$2_AA2") (pintype "bidirectional"))
      (node (ref "CD06") (pin "AA2") (pinfunction "P$2_AA2") (pintype "bidirectional"))
      (node (ref "CD07") (pin "AA2") (pinfunction "P$2_AA2") (pintype "bidirectional"))
    )
    (net (code "240") (name "WRITE") (class "Default")
      (node (ref "AB02") (pin "AS2") (pinfunction "P$2_AS2") (pintype "bidirectional"))
      (node (ref "AB03") (pin "AS2") (pinfunction "P$2_AS2") (pintype "bidirectional"))
      (node (ref "AB04") (pin "AS2") (pinfunction "P$2_AS2") (pintype "bidirectional"))
      (node (ref "AB05") (pin "AS2") (pinfunction "P$2_AS2") (pintype "bidirectional"))
      (node (ref "AB06") (pin "AS2") (pinfunction "P$2_AS2") (pintype "bidirectional"))
      (node (ref "AB07") (pin "AS2") (pinfunction "P$2_AS2") (pintype "bidirectional"))
      (node (ref "B14") (pin "D2") (pinfunction "IN1_D2") (pintype "input"))
      (node (ref "C08") (pin "J2") (pinfunction "OUT_J2") (pintype "output"))
      (node (ref "C09") (pin "K2") (pinfunction "IN2_K2") (pintype "input"))
      (node (ref "C09") (pin "L2") (pinfunction "IN3_L2") (pintype "input"))
      (node (ref "C16") (pin "R2") (pinfunction "IN3_R2") (pintype "input"))
    )
    (net (code "241") (name "unconnected-(A10A-1-PadE1)") (class "Default")
      (node (ref "A10") (pin "E1") (pinfunction "1_E1") (pintype "output"))
    )
    (net (code "242") (name "unconnected-(A10D-1-PadH2)") (class "Default")
      (node (ref "A10") (pin "H2") (pinfunction "1_H2") (pintype "output"))
    )
    (net (code "243") (name "unconnected-(A10E-1-PadL1)") (class "Default")
      (node (ref "A10") (pin "L1") (pinfunction "1_L1") (pintype "output"))
    )
    (net (code "244") (name "unconnected-(A10F-1-PadP2)") (class "Default")
      (node (ref "A10") (pin "P2") (pinfunction "1_P2") (pintype "output"))
    )
    (net (code "245") (name "unconnected-(A10G-1-PadS1)") (class "Default")
      (node (ref "A10") (pin "S1") (pinfunction "1_S1") (pintype "output"))
    )
    (net (code "246") (name "unconnected-(A10H-1-PadV2)") (class "Default")
      (node (ref "A10") (pin "V2") (pinfunction "1_V2") (pintype "output"))
    )
    (net (code "247") (name "unconnected-(B09A-1-PadE1)") (class "Default")
      (node (ref "B09") (pin "E1") (pinfunction "1_E1") (pintype "output"))
    )
    (net (code "248") (name "unconnected-(B09D-1-PadH2)") (class "Default")
      (node (ref "B09") (pin "H2") (pinfunction "1_H2") (pintype "output"))
    )
    (net (code "249") (name "unconnected-(B09E-1-PadL1)") (class "Default")
      (node (ref "B09") (pin "L1") (pinfunction "1_L1") (pintype "output"))
    )
    (net (code "250") (name "unconnected-(B09F-1-PadP2)") (class "Default")
      (node (ref "B09") (pin "P2") (pinfunction "1_P2") (pintype "output"))
    )
    (net (code "251") (name "unconnected-(B09G-1-PadS1)") (class "Default")
      (node (ref "B09") (pin "S1") (pinfunction "1_S1") (pintype "output"))
    )
    (net (code "252") (name "unconnected-(B09H-1-PadV2)") (class "Default")
      (node (ref "B09") (pin "V2") (pinfunction "1_V2") (pintype "output"))
    )
    (net (code "253") (name "unconnected-(C15A-0-PadF1)") (class "Default")
      (node (ref "C15") (pin "F1") (pinfunction "0_F1") (pintype "output"))
    )
    (net (code "254") (name "unconnected-(C15D-0-PadJ2)") (class "Default")
      (node (ref "C15") (pin "J2") (pinfunction "0_J2") (pintype "output"))
    )
    (net (code "255") (name "unconnected-(C15E-0-PadM1)") (class "Default")
      (node (ref "C15") (pin "M1") (pinfunction "0_M1") (pintype "output"))
    )
    (net (code "256") (name "unconnected-(D10H-0-PadV1)") (class "Default")
      (node (ref "D10") (pin "V1") (pinfunction "0_V1") (pintype "output"))
    )
    (net (code "257") (name "unconnected-(D11A-0-PadF1)") (class "Default")
      (node (ref "D11") (pin "F1") (pinfunction "0_F1") (pintype "output"))
    )
    (net (code "258") (name "unconnected-(D11D-0-PadJ2)") (class "Default")
      (node (ref "D11") (pin "J2") (pinfunction "0_J2") (pintype "output"))
    )
    (net (code "259") (name "unconnected-(D11E-0-PadM1)") (class "Default")
      (node (ref "D11") (pin "M1") (pinfunction "0_M1") (pintype "output"))
    )
    (net (code "260") (name "unconnected-(D11F-0-PadR2)") (class "Default")
      (node (ref "D11") (pin "R2") (pinfunction "0_R2") (pintype "output"))
    )
    (net (code "261") (name "unconnected-(D11G-0-PadU1)") (class "Default")
      (node (ref "D11") (pin "U1") (pinfunction "0_U1") (pintype "output"))
    )
    (net (code "262") (name "unconnected-(D11H-0-PadV1)") (class "Default")
      (node (ref "D11") (pin "V1") (pinfunction "0_V1") (pintype "output"))
    )
    (net (code "263") (name "unconnected-(D12A-0-PadF1)") (class "Default")
      (node (ref "D12") (pin "F1") (pinfunction "0_F1") (pintype "output"))
    )
    (net (code "264") (name "unconnected-(D12H-0-PadV1)") (class "Default")
      (node (ref "D12") (pin "V1") (pinfunction "0_V1") (pintype "output"))
    )
    (net (code "265") (name "unconnected-(D14D-1-PadH2)") (class "Default")
      (node (ref "D14") (pin "H2") (pinfunction "1_H2") (pintype "output"))
    )
    (net (code "266") (name "unconnected-(D14E-1-PadL1)") (class "Default")
      (node (ref "D14") (pin "L1") (pinfunction "1_L1") (pintype "output"))
    )
    (net (code "267") (name "unconnected-(D14F-1-PadP2)") (class "Default")
      (node (ref "D14") (pin "P2") (pinfunction "1_P2") (pintype "output"))
    )
    (net (code "268") (name "unconnected-(D14G-1-PadS1)") (class "Default")
      (node (ref "D14") (pin "S1") (pinfunction "1_S1") (pintype "output"))
    )
    (net (code "269") (name "unconnected-(D14H-1-PadV2)") (class "Default")
      (node (ref "D14") (pin "V2") (pinfunction "1_V2") (pintype "output"))
    )
    (net (code "270") (name "unconnected-(D15-PadJ2)") (class "Default")
      (node (ref "D15") (pin "J2") (pinfunction "J2_J2") (pintype "output"))
    )
    (net (code "271") (name "unconnected-(D15-PadK2)") (class "Default")
      (node (ref "D15") (pin "K2") (pinfunction "K2_K2") (pintype "output"))
    )
    (net (code "272") (name "unconnected-(D15-PadL2)") (class "Default")
      (node (ref "D15") (pin "L2") (pinfunction "L2_L2") (pintype "output"))
    )
    (net (code "273") (name "unconnected-(D15-PadN2)") (class "Default")
      (node (ref "D15") (pin "N2") (pinfunction "N2_N2") (pintype "output"))
    )
    (net (code "274") (name "unconnected-(D15-PadP2)") (class "Default")
      (node (ref "D15") (pin "P2") (pinfunction "P2_P2") (pintype "output"))
    )
    (net (code "275") (name "unconnected-(D15-PadS2)") (class "Default")
      (node (ref "D15") (pin "S2") (pinfunction "S2_S2") (pintype "output"))
    )
    (net (code "276") (name "unconnected-(D15-PadT2)") (class "Default")
      (node (ref "D15") (pin "T2") (pinfunction "T2_T2") (pintype "output"))
    )
    (net (code "277") (name "unconnected-(D15-PadU2)") (class "Default")
      (node (ref "D15") (pin "U2") (pinfunction "U2_U2") (pintype "output"))
    )
    (net (code "278") (name "unconnected-(D15-PadV2)") (class "Default")
      (node (ref "D15") (pin "V2") (pinfunction "V2_V2") (pintype "output"))
    )
    (net (code "279") (name "unconnected-(D16-PadJ2)") (class "Default")
      (node (ref "D16") (pin "J2") (pinfunction "J2_J2") (pintype "output"))
    )
    (net (code "280") (name "unconnected-(D16-PadK2)") (class "Default")
      (node (ref "D16") (pin "K2") (pinfunction "K2_K2") (pintype "output"))
    )
    (net (code "281") (name "unconnected-(D16-PadN2)") (class "Default")
      (node (ref "D16") (pin "N2") (pinfunction "N2_N2") (pintype "output"))
    )
    (net (code "282") (name "unconnected-(D16-PadP2)") (class "Default")
      (node (ref "D16") (pin "P2") (pinfunction "P2_P2") (pintype "output"))
    )
    (net (code "283") (name "unconnected-(D16-PadR2)") (class "Default")
      (node (ref "D16") (pin "R2") (pinfunction "R2_R2") (pintype "output"))
    )
    (net (code "284") (name "unconnected-(D16-PadS2)") (class "Default")
      (node (ref "D16") (pin "S2") (pinfunction "S2_S2") (pintype "output"))
    )
    (net (code "285") (name "unconnected-(D16-PadT2)") (class "Default")
      (node (ref "D16") (pin "T2") (pinfunction "T2_T2") (pintype "output"))
    )
    (net (code "286") (name "unconnected-(D16-PadU2)") (class "Default")
      (node (ref "D16") (pin "U2") (pinfunction "U2_U2") (pintype "output"))
    )
    (net (code "287") (name "unconnected-(D16-PadV2)") (class "Default")
      (node (ref "D16") (pin "V2") (pinfunction "V2_V2") (pintype "output"))
    )
    (net (code "288") (name "unconnected-(D17-PadK2)") (class "Default")
      (node (ref "D17") (pin "K2") (pinfunction "K2_K2") (pintype "output"))
    )
    (net (code "289") (name "unconnected-(D17-PadL2)") (class "Default")
      (node (ref "D17") (pin "L2") (pinfunction "L2_L2") (pintype "output"))
    )
    (net (code "290") (name "unconnected-(D17-PadN2)") (class "Default")
      (node (ref "D17") (pin "N2") (pinfunction "N2_N2") (pintype "output"))
    )
    (net (code "291") (name "unconnected-(D17-PadP2)") (class "Default")
      (node (ref "D17") (pin "P2") (pinfunction "P2_P2") (pintype "output"))
    )
    (net (code "292") (name "unconnected-(D17-PadR2)") (class "Default")
      (node (ref "D17") (pin "R2") (pinfunction "R2_R2") (pintype "output"))
    )
    (net (code "293") (name "unconnected-(D17-PadS2)") (class "Default")
      (node (ref "D17") (pin "S2") (pinfunction "S2_S2") (pintype "output"))
    )
    (net (code "294") (name "unconnected-(D17-PadT2)") (class "Default")
      (node (ref "D17") (pin "T2") (pinfunction "T2_T2") (pintype "output"))
    )
    (net (code "295") (name "unconnected-(D17-PadU2)") (class "Default")
      (node (ref "D17") (pin "U2") (pinfunction "U2_U2") (pintype "output"))
    )
    (net (code "296") (name "unconnected-(D17-PadV2)") (class "Default")
      (node (ref "D17") (pin "V2") (pinfunction "V2_V2") (pintype "output"))
    )
    (net (code "297") (name "~{3CYCLE}") (class "Default")
      (node (ref "A20") (pin "K2") (pinfunction "P$2_K2") (pintype "bidirectional"))
      (node (ref "B20") (pin "K2") (pinfunction "P$2_K2") (pintype "bidirectional"))
    )
    (net (code "298") (name "~{AC00_BUS}") (class "Default")
      (node (ref "A18") (pin "B1") (pinfunction "P$2_B1") (pintype "bidirectional"))
      (node (ref "B18") (pin "B1") (pinfunction "P$2_B1") (pintype "bidirectional"))
    )
    (net (code "299") (name "~{AC01_BUS}") (class "Default")
      (node (ref "A18") (pin "D1") (pinfunction "P$2_D1") (pintype "bidirectional"))
      (node (ref "B18") (pin "D1") (pinfunction "P$2_D1") (pintype "bidirectional"))
    )
    (net (code "300") (name "~{AC02_BUS}") (class "Default")
      (node (ref "A18") (pin "E1") (pinfunction "P$2_E1") (pintype "bidirectional"))
      (node (ref "B18") (pin "E1") (pinfunction "P$2_E1") (pintype "bidirectional"))
    )
    (net (code "301") (name "~{AC03_BUS}") (class "Default")
      (node (ref "A18") (pin "H1") (pinfunction "P$2_H1") (pintype "bidirectional"))
      (node (ref "B18") (pin "H1") (pinfunction "P$2_H1") (pintype "bidirectional"))
    )
    (net (code "302") (name "~{AC04_BUS}") (class "Default")
      (node (ref "A18") (pin "J1") (pinfunction "P$2_J1") (pintype "bidirectional"))
      (node (ref "B18") (pin "J1") (pinfunction "P$2_J1") (pintype "bidirectional"))
    )
    (net (code "303") (name "~{AC05_BUS}") (class "Default")
      (node (ref "A18") (pin "L1") (pinfunction "P$2_L1") (pintype "bidirectional"))
      (node (ref "B18") (pin "L1") (pinfunction "P$2_L1") (pintype "bidirectional"))
    )
    (net (code "304") (name "~{AC06_BUS}") (class "Default")
      (node (ref "A14") (pin "D1") (pinfunction "D_D1") (pintype "open_collector"))
      (node (ref "A14") (pin "H2") (pinfunction "D_H2") (pintype "open_collector"))
      (node (ref "A14") (pin "K1") (pinfunction "D_K1") (pintype "open_collector"))
      (node (ref "A18") (pin "M1") (pinfunction "P$2_M1") (pintype "bidirectional"))
      (node (ref "B18") (pin "M1") (pinfunction "P$2_M1") (pintype "bidirectional"))
    )
    (net (code "305") (name "~{AC07_BUS}") (class "Default")
      (node (ref "A14") (pin "E1") (pinfunction "E_E1") (pintype "open_collector"))
      (node (ref "A14") (pin "L1") (pinfunction "E_L1") (pintype "open_collector"))
      (node (ref "A14") (pin "N2") (pinfunction "D_N2") (pintype "open_collector"))
      (node (ref "A18") (pin "P1") (pinfunction "P$2_P1") (pintype "bidirectional"))
      (node (ref "B18") (pin "P1") (pinfunction "P$2_P1") (pintype "bidirectional"))
    )
    (net (code "306") (name "~{AC08_BUS}") (class "Default")
      (node (ref "A14") (pin "R1") (pinfunction "D_R1") (pintype "open_collector"))
      (node (ref "A14") (pin "S1") (pinfunction "E_S1") (pintype "open_collector"))
      (node (ref "A14") (pin "U2") (pinfunction "D_U2") (pintype "open_collector"))
      (node (ref "A18") (pin "S1") (pinfunction "P$2_S1") (pintype "bidirectional"))
      (node (ref "B18") (pin "S1") (pinfunction "P$2_S1") (pintype "bidirectional"))
    )
    (net (code "307") (name "~{AC09_BUS}") (class "Default")
      (node (ref "A14") (pin "J2") (pinfunction "E_J2") (pintype "open_collector"))
      (node (ref "A18") (pin "D2") (pinfunction "P$2_D2") (pintype "bidirectional"))
      (node (ref "B18") (pin "D2") (pinfunction "P$2_D2") (pintype "bidirectional"))
    )
    (net (code "308") (name "~{AC10_BUS}") (class "Default")
      (node (ref "A14") (pin "P2") (pinfunction "E_P2") (pintype "open_collector"))
      (node (ref "A18") (pin "E2") (pinfunction "P$2_E2") (pintype "bidirectional"))
      (node (ref "B18") (pin "E2") (pinfunction "P$2_E2") (pintype "bidirectional"))
    )
    (net (code "309") (name "~{AC11_BUS}") (class "Default")
      (node (ref "A14") (pin "V2") (pinfunction "E_V2") (pintype "open_collector"))
      (node (ref "A18") (pin "H2") (pinfunction "P$2_H2") (pintype "bidirectional"))
      (node (ref "B18") (pin "H2") (pinfunction "P$2_H2") (pintype "bidirectional"))
    )
    (net (code "310") (name "~{AC_CLR_BUS}") (class "Default")
      (node (ref "A18") (pin "P2") (pinfunction "P$2_P2") (pintype "bidirectional"))
      (node (ref "B18") (pin "P2") (pinfunction "P$2_P2") (pintype "bidirectional"))
    )
    (net (code "311") (name "~{ADD_ACCEPTED}") (class "Default")
      (node (ref "A19") (pin "S2") (pinfunction "P$2_S2") (pintype "bidirectional"))
      (node (ref "B19") (pin "S2") (pinfunction "P$2_S2") (pintype "bidirectional"))
    )
    (net (code "312") (name "~{BF_ENABLE}") (class "Default")
      (node (ref "A09") (pin "D1") (pinfunction "IN_D1") (pintype "input"))
      (node (ref "C09") (pin "E1") (pinfunction "IN1_E1") (pintype "input"))
      (node (ref "C18") (pin "E1") (pinfunction "P$2_E1") (pintype "bidirectional"))
      (node (ref "D18") (pin "E1") (pinfunction "P$2_E1") (pintype "bidirectional"))
    )
    (net (code "313") (name "~{BMB00}") (class "Default")
      (node (ref "B08") (pin "A1") (pinfunction "A_A1") (pintype "input"))
      (node (ref "B10") (pin "B1") (pinfunction "OUT_B1") (pintype "output"))
    )
    (net (code "314") (name "~{BMB01}") (class "Default")
      (node (ref "B08") (pin "B1") (pinfunction "B_B1") (pintype "input"))
      (node (ref "B10") (pin "D2") (pinfunction "OUT_D2") (pintype "output"))
    )
    (net (code "315") (name "~{BMB02}") (class "Default")
      (node (ref "B08") (pin "F1") (pinfunction "A_F1") (pintype "input"))
      (node (ref "B10") (pin "E1") (pinfunction "OUT_E1") (pintype "output"))
    )
    (net (code "316") (name "~{BMB03}") (class "Default")
      (node (ref "A08") (pin "D1") (pinfunction "IN4_D1") (pintype "input"))
      (node (ref "A08") (pin "K1") (pinfunction "IN4_K1") (pintype "input"))
      (node (ref "A17") (pin "H1") (pinfunction "P$2_H1") (pintype "bidirectional"))
      (node (ref "B08") (pin "H1") (pinfunction "B_H1") (pintype "input"))
      (node (ref "B10") (pin "H1") (pinfunction "OUT_H1") (pintype "output"))
      (node (ref "B17") (pin "H1") (pinfunction "P$2_H1") (pintype "bidirectional"))
    )
    (net (code "317") (name "~{BMB04}") (class "Default")
      (node (ref "A17") (pin "L1") (pinfunction "P$2_L1") (pintype "bidirectional"))
      (node (ref "B08") (pin "M1") (pinfunction "A_M1") (pintype "input"))
      (node (ref "B10") (pin "F2") (pinfunction "OUT_F2") (pintype "output"))
      (node (ref "B17") (pin "L1") (pinfunction "P$2_L1") (pintype "bidirectional"))
    )
    (net (code "318") (name "~{BMB05}") (class "Default")
      (node (ref "A08") (pin "B1") (pinfunction "IN2_B1") (pintype "input"))
      (node (ref "A08") (pin "H1") (pinfunction "IN2_H1") (pintype "input"))
      (node (ref "A17") (pin "P1") (pinfunction "P$2_P1") (pintype "bidirectional"))
      (node (ref "B08") (pin "N1") (pinfunction "B_N1") (pintype "input"))
      (node (ref "B10") (pin "K1") (pinfunction "OUT_K1") (pintype "output"))
      (node (ref "B17") (pin "P1") (pinfunction "P$2_P1") (pintype "bidirectional"))
    )
    (net (code "319") (name "~{BMB06}") (class "Default")
      (node (ref "A17") (pin "D2") (pinfunction "P$2_D2") (pintype "bidirectional"))
      (node (ref "B08") (pin "D2") (pinfunction "A_D2") (pintype "input"))
      (node (ref "B10") (pin "J2") (pinfunction "OUT_J2") (pintype "output"))
      (node (ref "B17") (pin "D2") (pinfunction "P$2_D2") (pintype "bidirectional"))
    )
    (net (code "320") (name "~{BMB07}") (class "Default")
      (node (ref "A08") (pin "M2") (pinfunction "IN3_M2") (pintype "input"))
      (node (ref "A08") (pin "S2") (pinfunction "IN2_S2") (pintype "input"))
      (node (ref "A17") (pin "H2") (pinfunction "P$2_H2") (pintype "bidirectional"))
      (node (ref "B08") (pin "E2") (pinfunction "B_E2") (pintype "input"))
      (node (ref "B10") (pin "M1") (pinfunction "OUT_M1") (pintype "output"))
      (node (ref "B17") (pin "H2") (pinfunction "P$2_H2") (pintype "bidirectional"))
    )
    (net (code "321") (name "~{BMB08}") (class "Default")
      (node (ref "A08") (pin "H2") (pinfunction "IN4_H2") (pintype "input"))
      (node (ref "A08") (pin "T2") (pinfunction "IN3_T2") (pintype "input"))
      (node (ref "A17") (pin "M2") (pinfunction "P$2_M2") (pintype "bidirectional"))
      (node (ref "B08") (pin "K2") (pinfunction "A_K2") (pintype "input"))
      (node (ref "B10") (pin "L2") (pinfunction "OUT_L2") (pintype "output"))
      (node (ref "B17") (pin "M2") (pinfunction "P$2_M2") (pintype "bidirectional"))
    )
    (net (code "322") (name "~{BMB09}") (class "Default")
      (node (ref "B08") (pin "L2") (pinfunction "B_L2") (pintype "input"))
      (node (ref "B10") (pin "P1") (pinfunction "OUT_P1") (pintype "output"))
      (node (ref "C11") (pin "E1") (pinfunction "IN2_E1") (pintype "input"))
      (node (ref "C11") (pin "M2") (pinfunction "IN2_M2") (pintype "input"))
      (node (ref "C12") (pin "E1") (pinfunction "IN2_E1") (pintype "input"))
    )
    (net (code "323") (name "~{BMB10}") (class "Default")
      (node (ref "B08") (pin "R2") (pinfunction "A_R2") (pintype "input"))
      (node (ref "B10") (pin "N2") (pinfunction "OUT_N2") (pintype "output"))
    )
    (net (code "324") (name "~{BMB11}") (class "Default")
      (node (ref "B08") (pin "S2") (pinfunction "B_S2") (pintype "input"))
      (node (ref "B10") (pin "S1") (pinfunction "OUT_S1") (pintype "output"))
    )
    (net (code "325") (name "~{BREAK}") (class "Default")
      (node (ref "A19") (pin "P2") (pinfunction "P$2_P2") (pintype "bidirectional"))
      (node (ref "B19") (pin "P2") (pinfunction "P$2_P2") (pintype "bidirectional"))
    )
    (net (code "326") (name "~{BRQ}") (class "Default")
      (node (ref "A19") (pin "K2") (pinfunction "P$2_K2") (pintype "bidirectional"))
      (node (ref "B19") (pin "K2") (pinfunction "P$2_K2") (pintype "bidirectional"))
    )
    (net (code "327") (name "~{BTP2}") (class "Default")
      (node (ref "C13") (pin "J2") (pinfunction "IN2_J2") (pintype "input"))
      (node (ref "D08") (pin "B1") (pinfunction "OUT_B1") (pintype "output"))
    )
    (net (code "328") (name "~{B_RUN}") (class "Default")
      (node (ref "A18") (pin "S2") (pinfunction "P$2_S2") (pintype "bidirectional"))
      (node (ref "B18") (pin "S2") (pinfunction "P$2_S2") (pintype "bidirectional"))
    )
    (net (code "329") (name "~{CA_INCR}") (class "Default")
      (node (ref "A20") (pin "M2") (pinfunction "P$2_M2") (pintype "bidirectional"))
      (node (ref "B20") (pin "M2") (pinfunction "P$2_M2") (pintype "bidirectional"))
    )
    (net (code "330") (name "~{CDF}") (class "Default")
      (node (ref "C13") (pin "N1") (pinfunction "OUT_N1") (pintype "output"))
      (node (ref "C13") (pin "R1") (pinfunction "IN2_R1") (pintype "input"))
    )
    (net (code "331") (name "~{CIF}") (class "Default")
      (node (ref "C13") (pin "N2") (pinfunction "OUT_N2") (pintype "output"))
      (node (ref "C13") (pin "R2") (pinfunction "IN2_R2") (pintype "input"))
    )
    (net (code "332") (name "~{CLR_DF}") (class "Default")
      (node (ref "D08") (pin "R2") (pinfunction "OUT_R2") (pintype "output"))
      (node (ref "D12") (pin "K2") (pinfunction "R_K2") (pintype "input"))
    )
    (net (code "333") (name "~{CLR_EA}") (class "Default")
      (node (ref "D08") (pin "P1") (pinfunction "OUT_P1") (pintype "output"))
      (node (ref "D10") (pin "A1") (pinfunction "R_A1") (pintype "input"))
    )
    (net (code "334") (name "~{CLR_IB}") (class "Default")
      (node (ref "D08") (pin "S1") (pinfunction "OUT_S1") (pintype "output"))
      (node (ref "D11") (pin "K2") (pinfunction "R_K2") (pintype "input"))
    )
    (net (code "335") (name "~{CLR_IF}") (class "Default")
      (node (ref "D08") (pin "N2") (pinfunction "OUT_N2") (pintype "output"))
      (node (ref "D10") (pin "K2") (pinfunction "R_K2") (pintype "input"))
    )
    (net (code "336") (name "~{DA00}") (class "Default")
      (node (ref "A19") (pin "B1") (pinfunction "P$2_B1") (pintype "bidirectional"))
      (node (ref "B19") (pin "B1") (pinfunction "P$2_B1") (pintype "bidirectional"))
    )
    (net (code "337") (name "~{DA01}") (class "Default")
      (node (ref "A19") (pin "D1") (pinfunction "P$2_D1") (pintype "bidirectional"))
      (node (ref "B19") (pin "D1") (pinfunction "P$2_D1") (pintype "bidirectional"))
    )
    (net (code "338") (name "~{DA02}") (class "Default")
      (node (ref "A19") (pin "E1") (pinfunction "P$2_E1") (pintype "bidirectional"))
      (node (ref "B19") (pin "E1") (pinfunction "P$2_E1") (pintype "bidirectional"))
    )
    (net (code "339") (name "~{DA03}") (class "Default")
      (node (ref "A19") (pin "H1") (pinfunction "P$2_H1") (pintype "bidirectional"))
      (node (ref "B19") (pin "H1") (pinfunction "P$2_H1") (pintype "bidirectional"))
    )
    (net (code "340") (name "~{DA04}") (class "Default")
      (node (ref "A19") (pin "J1") (pinfunction "P$2_J1") (pintype "bidirectional"))
      (node (ref "B19") (pin "J1") (pinfunction "P$2_J1") (pintype "bidirectional"))
    )
    (net (code "341") (name "~{DA05}") (class "Default")
      (node (ref "A19") (pin "L1") (pinfunction "P$2_L1") (pintype "bidirectional"))
      (node (ref "B19") (pin "L1") (pinfunction "P$2_L1") (pintype "bidirectional"))
    )
    (net (code "342") (name "~{DA06}") (class "Default")
      (node (ref "A19") (pin "M1") (pinfunction "P$2_M1") (pintype "bidirectional"))
      (node (ref "B19") (pin "M1") (pinfunction "P$2_M1") (pintype "bidirectional"))
    )
    (net (code "343") (name "~{DA07}") (class "Default")
      (node (ref "A19") (pin "P1") (pinfunction "P$2_P1") (pintype "bidirectional"))
      (node (ref "B19") (pin "P1") (pinfunction "P$2_P1") (pintype "bidirectional"))
    )
    (net (code "344") (name "~{DA08}") (class "Default")
      (node (ref "A19") (pin "S1") (pinfunction "P$2_S1") (pintype "bidirectional"))
      (node (ref "B19") (pin "S1") (pinfunction "P$2_S1") (pintype "bidirectional"))
    )
    (net (code "345") (name "~{DA09}") (class "Default")
      (node (ref "A19") (pin "D2") (pinfunction "P$2_D2") (pintype "bidirectional"))
      (node (ref "B19") (pin "D2") (pinfunction "P$2_D2") (pintype "bidirectional"))
    )
    (net (code "346") (name "~{DA10}") (class "Default")
      (node (ref "A19") (pin "E2") (pinfunction "P$2_E2") (pintype "bidirectional"))
      (node (ref "B19") (pin "E2") (pinfunction "P$2_E2") (pintype "bidirectional"))
    )
    (net (code "347") (name "~{DA11}") (class "Default")
      (node (ref "A19") (pin "H2") (pinfunction "P$2_H2") (pintype "bidirectional"))
      (node (ref "B19") (pin "H2") (pinfunction "P$2_H2") (pintype "bidirectional"))
    )
    (net (code "348") (name "~{DATA00}") (class "Default")
      (node (ref "A20") (pin "B1") (pinfunction "P$2_B1") (pintype "bidirectional"))
      (node (ref "B20") (pin "B1") (pinfunction "P$2_B1") (pintype "bidirectional"))
    )
    (net (code "349") (name "~{DATA01}") (class "Default")
      (node (ref "A20") (pin "D1") (pinfunction "P$2_D1") (pintype "bidirectional"))
      (node (ref "B20") (pin "D1") (pinfunction "P$2_D1") (pintype "bidirectional"))
    )
    (net (code "350") (name "~{DATA02}") (class "Default")
      (node (ref "A20") (pin "E1") (pinfunction "P$2_E1") (pintype "bidirectional"))
      (node (ref "B20") (pin "E1") (pinfunction "P$2_E1") (pintype "bidirectional"))
    )
    (net (code "351") (name "~{DATA03}") (class "Default")
      (node (ref "A20") (pin "H1") (pinfunction "P$2_H1") (pintype "bidirectional"))
      (node (ref "B20") (pin "H1") (pinfunction "P$2_H1") (pintype "bidirectional"))
    )
    (net (code "352") (name "~{DATA04}") (class "Default")
      (node (ref "A20") (pin "J1") (pinfunction "P$2_J1") (pintype "bidirectional"))
      (node (ref "B20") (pin "J1") (pinfunction "P$2_J1") (pintype "bidirectional"))
    )
    (net (code "353") (name "~{DATA05}") (class "Default")
      (node (ref "A20") (pin "L1") (pinfunction "P$2_L1") (pintype "bidirectional"))
      (node (ref "B20") (pin "L1") (pinfunction "P$2_L1") (pintype "bidirectional"))
    )
    (net (code "354") (name "~{DATA06}") (class "Default")
      (node (ref "A20") (pin "M1") (pinfunction "P$2_M1") (pintype "bidirectional"))
      (node (ref "B20") (pin "M1") (pinfunction "P$2_M1") (pintype "bidirectional"))
    )
    (net (code "355") (name "~{DATA07}") (class "Default")
      (node (ref "A20") (pin "P1") (pinfunction "P$2_P1") (pintype "bidirectional"))
      (node (ref "B20") (pin "P1") (pinfunction "P$2_P1") (pintype "bidirectional"))
    )
    (net (code "356") (name "~{DATA08}") (class "Default")
      (node (ref "A20") (pin "S1") (pinfunction "P$2_S1") (pintype "bidirectional"))
      (node (ref "B20") (pin "S1") (pinfunction "P$2_S1") (pintype "bidirectional"))
    )
    (net (code "357") (name "~{DATA09}") (class "Default")
      (node (ref "A20") (pin "D2") (pinfunction "P$2_D2") (pintype "bidirectional"))
      (node (ref "B20") (pin "D2") (pinfunction "P$2_D2") (pintype "bidirectional"))
    )
    (net (code "358") (name "~{DATA10}") (class "Default")
      (node (ref "A20") (pin "E2") (pinfunction "P$2_E2") (pintype "bidirectional"))
      (node (ref "B20") (pin "E2") (pinfunction "P$2_E2") (pintype "bidirectional"))
    )
    (net (code "359") (name "~{DATA11}") (class "Default")
      (node (ref "A20") (pin "H2") (pinfunction "P$2_H2") (pintype "bidirectional"))
      (node (ref "B20") (pin "H2") (pinfunction "P$2_H2") (pintype "bidirectional"))
    )
    (net (code "360") (name "~{DATA_IN}") (class "Default")
      (node (ref "A19") (pin "M2") (pinfunction "P$2_M2") (pintype "bidirectional"))
      (node (ref "B19") (pin "M2") (pinfunction "P$2_M2") (pintype "bidirectional"))
    )
    (net (code "361") (name "~{DEL1}") (class "Default")
      (node (ref "C09") (pin "D1") (pinfunction "OUT_D1") (pintype "output"))
      (node (ref "D14") (pin "F2") (pinfunction "S_F2") (pintype "input"))
      (node (ref "D14") (pin "K1") (pinfunction "S_K1") (pintype "input"))
    )
    (net (code "362") (name "~{DF0}") (class "Default")
      (node (ref "A14") (pin "F1") (pinfunction "A_F1") (pintype "input"))
      (node (ref "D12") (pin "R2") (pinfunction "0_R2") (pintype "output"))
    )
    (net (code "363") (name "~{DF1}") (class "Default")
      (node (ref "A14") (pin "H1") (pinfunction "B_H1") (pintype "input"))
      (node (ref "D12") (pin "U1") (pinfunction "0_U1") (pintype "output"))
    )
    (net (code "364") (name "~{DF_ENABLE}") (class "Default")
      (node (ref "A09") (pin "K2") (pinfunction "IN_K2") (pintype "input"))
      (node (ref "C09") (pin "H1") (pinfunction "IN3_H1") (pintype "input"))
      (node (ref "C18") (pin "B1") (pinfunction "P$2_B1") (pintype "bidirectional"))
      (node (ref "D18") (pin "B1") (pinfunction "P$2_B1") (pintype "bidirectional"))
    )
    (net (code "365") (name "~{DONE}") (class "Default")
      (node (ref "B15") (pin "S2") (pinfunction "B_S2") (pintype "input"))
      (node (ref "D12") (pin "M1") (pinfunction "0_M1") (pintype "output"))
    )
    (net (code "366") (name "~{EA0}") (class "Default")
      (node (ref "C09") (pin "K1") (pinfunction "IN1_K1") (pintype "input"))
      (node (ref "C16") (pin "K1") (pinfunction "IN1_K1") (pintype "input"))
      (node (ref "C17") (pin "L2") (pinfunction "P$2_L2") (pintype "bidirectional"))
      (node (ref "D10") (pin "F1") (pinfunction "0_F1") (pintype "output"))
    )
    (net (code "367") (name "~{EA1}") (class "Default")
      (node (ref "C09") (pin "L1") (pinfunction "IN2_L1") (pintype "input"))
      (node (ref "C16") (pin "L1") (pinfunction "IN2_L1") (pintype "input"))
      (node (ref "C17") (pin "R2") (pinfunction "P$2_R2") (pintype "bidirectional"))
      (node (ref "D10") (pin "J2") (pinfunction "0_J2") (pintype "output"))
    )
    (net (code "368") (name "~{EA2}") (class "Default")
      (node (ref "C09") (pin "M1") (pinfunction "IN3_M1") (pintype "input"))
      (node (ref "C17") (pin "V2") (pinfunction "P$2_V2") (pintype "bidirectional"))
      (node (ref "D10") (pin "M1") (pinfunction "0_M1") (pintype "output"))
    )
    (net (code "369") (name "~{EA_OK}") (class "Default")
      (node (ref "C16") (pin "D1") (pinfunction "OUT_D1") (pintype "output"))
      (node (ref "C16") (pin "E1") (pinfunction "IN1_E1") (pintype "input"))
    )
    (net (code "370") (name "~{EA}") (class "Default")
      (node (ref "C14") (pin "J2") (pinfunction "OUT_J2") (pintype "output"))
      (node (ref "C20") (pin "B1") (pinfunction "P$2_B1") (pintype "bidirectional"))
      (node (ref "D20") (pin "B1") (pinfunction "P$2_B1") (pintype "bidirectional"))
    )
    (net (code "371") (name "~{EMA00}") (class "Default")
      (node (ref "AB02") (pin "AD2") (pinfunction "P$2_AD2") (pintype "bidirectional"))
      (node (ref "AB03") (pin "AD2") (pinfunction "P$2_AD2") (pintype "bidirectional"))
      (node (ref "AB04") (pin "AD2") (pinfunction "P$2_AD2") (pintype "bidirectional"))
      (node (ref "AB05") (pin "AD2") (pinfunction "P$2_AD2") (pintype "bidirectional"))
      (node (ref "AB06") (pin "AD2") (pinfunction "P$2_AD2") (pintype "bidirectional"))
      (node (ref "AB07") (pin "AD2") (pinfunction "P$2_AD2") (pintype "bidirectional"))
      (node (ref "B12") (pin "E1") (pinfunction "OUT_E1") (pintype "output"))
    )
    (net (code "372") (name "~{EMA01}") (class "Default")
      (node (ref "AB02") (pin "AE2") (pinfunction "P$2_AE2") (pintype "bidirectional"))
      (node (ref "AB03") (pin "AE2") (pinfunction "P$2_AE2") (pintype "bidirectional"))
      (node (ref "AB04") (pin "AE2") (pinfunction "P$2_AE2") (pintype "bidirectional"))
      (node (ref "AB05") (pin "AE2") (pinfunction "P$2_AE2") (pintype "bidirectional"))
      (node (ref "AB06") (pin "AE2") (pinfunction "P$2_AE2") (pintype "bidirectional"))
      (node (ref "AB07") (pin "AE2") (pinfunction "P$2_AE2") (pintype "bidirectional"))
      (node (ref "B12") (pin "L1") (pinfunction "OUT_L1") (pintype "output"))
    )
    (net (code "373") (name "~{EMA02}") (class "Default")
      (node (ref "AB02") (pin "AH2") (pinfunction "P$2_AH2") (pintype "bidirectional"))
      (node (ref "AB03") (pin "AH2") (pinfunction "P$2_AH2") (pintype "bidirectional"))
      (node (ref "AB04") (pin "AH2") (pinfunction "P$2_AH2") (pintype "bidirectional"))
      (node (ref "AB05") (pin "AH2") (pinfunction "P$2_AH2") (pintype "bidirectional"))
      (node (ref "AB06") (pin "AH2") (pinfunction "P$2_AH2") (pintype "bidirectional"))
      (node (ref "AB07") (pin "AH2") (pinfunction "P$2_AH2") (pintype "bidirectional"))
      (node (ref "B12") (pin "S1") (pinfunction "OUT_S1") (pintype "output"))
    )
    (net (code "374") (name "~{EMA}") (class "Default")
      (node (ref "C14") (pin "P2") (pinfunction "OUT_P2") (pintype "output"))
      (node (ref "C19") (pin "V2") (pinfunction "P$2_V2") (pintype "bidirectional"))
      (node (ref "D19") (pin "V2") (pinfunction "P$2_V2") (pintype "bidirectional"))
    )
    (net (code "375") (name "~{EX_DA0}") (class "Default")
      (node (ref "A20") (pin "V2") (pinfunction "P$2_V2") (pintype "bidirectional"))
      (node (ref "B20") (pin "V2") (pinfunction "P$2_V2") (pintype "bidirectional"))
      (node (ref "D11") (pin "D1") (pinfunction "S_D1") (pintype "input"))
    )
    (net (code "376") (name "~{EX_DA1}") (class "Default")
      (node (ref "A20") (pin "T2") (pinfunction "P$2_T2") (pintype "bidirectional"))
      (node (ref "B20") (pin "T2") (pinfunction "P$2_T2") (pintype "bidirectional"))
      (node (ref "D11") (pin "F2") (pinfunction "S_F2") (pintype "input"))
    )
    (net (code "377") (name "~{EX_DA2}") (class "Default")
      (node (ref "A20") (pin "S2") (pinfunction "P$2_S2") (pintype "bidirectional"))
      (node (ref "B20") (pin "S2") (pinfunction "P$2_S2") (pintype "bidirectional"))
      (node (ref "D11") (pin "K1") (pinfunction "S_K1") (pintype "input"))
    )
    (net (code "378") (name "~{FIELD1}") (class "Default")
      (node (ref "B10") (pin "S2") (pinfunction "IN_S2") (pintype "input"))
      (node (ref "C16") (pin "N1") (pinfunction "OUT_N1") (pintype "output"))
      (node (ref "C17") (pin "F2") (pinfunction "P$2_F2") (pintype "bidirectional"))
    )
    (net (code "379") (name "~{IF0}") (class "Default")
      (node (ref "A14") (pin "A1") (pinfunction "A_A1") (pintype "input"))
      (node (ref "D10") (pin "R2") (pinfunction "0_R2") (pintype "output"))
    )
    (net (code "380") (name "~{IF1}") (class "Default")
      (node (ref "A14") (pin "B1") (pinfunction "B_B1") (pintype "input"))
      (node (ref "D10") (pin "U1") (pinfunction "0_U1") (pintype "output"))
    )
    (net (code "381") (name "~{INH}") (class "Default")
      (node (ref "C08") (pin "R1") (pinfunction "IN4_R1") (pintype "input"))
      (node (ref "D14") (pin "V1") (pinfunction "0_V1") (pintype "output"))
    )
    (net (code "382") (name "~{INIT}") (class "Default")
      (node (ref "C14") (pin "S1") (pinfunction "OUT_S1") (pintype "output"))
      (node (ref "C15") (pin "A1") (pinfunction "R_A1") (pintype "input"))
      (node (ref "D12") (pin "A1") (pinfunction "R_A1") (pintype "input"))
      (node (ref "D14") (pin "A1") (pinfunction "R_A1") (pintype "input"))
      (node (ref "D14") (pin "K2") (pinfunction "R_K2") (pintype "input"))
    )
    (net (code "383") (name "~{INT_INHIBIT}") (class "Default")
      (node (ref "C18") (pin "L1") (pinfunction "P$2_L1") (pintype "bidirectional"))
      (node (ref "D08") (pin "M1") (pinfunction "OUT_M1") (pintype "output"))
      (node (ref "D18") (pin "L1") (pinfunction "P$2_L1") (pintype "bidirectional"))
    )
    (net (code "384") (name "~{IRQ_BUS}") (class "Default")
      (node (ref "A18") (pin "M2") (pinfunction "P$2_M2") (pintype "bidirectional"))
      (node (ref "B18") (pin "M2") (pinfunction "P$2_M2") (pintype "bidirectional"))
    )
    (net (code "385") (name "~{KEY_CLR}") (class "Default")
      (node (ref "B14") (pin "S2") (pinfunction "IN2_S2") (pintype "input"))
      (node (ref "C13") (pin "U2") (pinfunction "IN2_U2") (pintype "input"))
      (node (ref "C18") (pin "J1") (pinfunction "P$2_J1") (pintype "bidirectional"))
      (node (ref "D18") (pin "J1") (pinfunction "P$2_J1") (pintype "bidirectional"))
    )
    (net (code "386") (name "~{KEY_DF2}") (class "Default")
      (node (ref "A09") (pin "J1") (pinfunction "IN_J1") (pintype "input"))
      (node (ref "C18") (pin "S1") (pinfunction "P$2_S1") (pintype "bidirectional"))
      (node (ref "D18") (pin "S1") (pinfunction "P$2_S1") (pintype "bidirectional"))
    )
    (net (code "387") (name "~{KEY_IF2}") (class "Default")
      (node (ref "A09") (pin "E2") (pinfunction "IN_E2") (pintype "input"))
      (node (ref "C18") (pin "P1") (pinfunction "P$2_P1") (pintype "bidirectional"))
      (node (ref "D18") (pin "P1") (pinfunction "P$2_P1") (pintype "bidirectional"))
    )
    (net (code "388") (name "~{KEY_LOAD}") (class "Default")
      (node (ref "A09") (pin "F1") (pinfunction "IN_F1") (pintype "input"))
      (node (ref "C18") (pin "H2") (pinfunction "P$2_H2") (pintype "bidirectional"))
      (node (ref "D18") (pin "H2") (pinfunction "P$2_H2") (pintype "bidirectional"))
    )
    (net (code "389") (name "~{LOAD_INH}") (class "Default")
      (node (ref "C09") (pin "V1") (pinfunction "OUT_V1") (pintype "output"))
      (node (ref "C13") (pin "T2") (pinfunction "IN1_T2") (pintype "input"))
      (node (ref "D08") (pin "K2") (pinfunction "IN_K2") (pintype "input"))
    )
    (net (code "390") (name "~{LOAD_MD}") (class "Default")
      (node (ref "C14") (pin "A1") (pinfunction "IN1_A1") (pintype "input"))
      (node (ref "C16") (pin "U1") (pinfunction "OUT_U1") (pintype "output"))
    )
    (net (code "391") (name "~{LOAD_SF}") (class "Default")
      (node (ref "B14") (pin "R2") (pinfunction "IN1_R2") (pintype "input"))
      (node (ref "C18") (pin "M1") (pinfunction "P$2_M1") (pintype "bidirectional"))
      (node (ref "D18") (pin "M1") (pinfunction "P$2_M1") (pintype "bidirectional"))
    )
    (net (code "392") (name "~{MA00}") (class "Default")
      (node (ref "AB02") (pin "AD1") (pinfunction "P$2_AD1") (pintype "bidirectional"))
      (node (ref "AB03") (pin "AD1") (pinfunction "P$2_AD1") (pintype "bidirectional"))
      (node (ref "AB04") (pin "AD1") (pinfunction "P$2_AD1") (pintype "bidirectional"))
      (node (ref "AB05") (pin "AD1") (pinfunction "P$2_AD1") (pintype "bidirectional"))
      (node (ref "AB06") (pin "AD1") (pinfunction "P$2_AD1") (pintype "bidirectional"))
      (node (ref "AB07") (pin "AD1") (pinfunction "P$2_AD1") (pintype "bidirectional"))
      (node (ref "B12") (pin "J2") (pinfunction "OUT_J2") (pintype "output"))
    )
    (net (code "393") (name "~{MA01}") (class "Default")
      (node (ref "AB02") (pin "AE1") (pinfunction "P$2_AE1") (pintype "bidirectional"))
      (node (ref "AB03") (pin "AE1") (pinfunction "P$2_AE1") (pintype "bidirectional"))
      (node (ref "AB04") (pin "AE1") (pinfunction "P$2_AE1") (pintype "bidirectional"))
      (node (ref "AB05") (pin "AE1") (pinfunction "P$2_AE1") (pintype "bidirectional"))
      (node (ref "AB06") (pin "AE1") (pinfunction "P$2_AE1") (pintype "bidirectional"))
      (node (ref "AB07") (pin "AE1") (pinfunction "P$2_AE1") (pintype "bidirectional"))
      (node (ref "B12") (pin "P2") (pinfunction "OUT_P2") (pintype "output"))
    )
    (net (code "394") (name "~{MA02}") (class "Default")
      (node (ref "AB02") (pin "AH1") (pinfunction "P$2_AH1") (pintype "bidirectional"))
      (node (ref "AB03") (pin "AH1") (pinfunction "P$2_AH1") (pintype "bidirectional"))
      (node (ref "AB04") (pin "AH1") (pinfunction "P$2_AH1") (pintype "bidirectional"))
      (node (ref "AB05") (pin "AH1") (pinfunction "P$2_AH1") (pintype "bidirectional"))
      (node (ref "AB06") (pin "AH1") (pinfunction "P$2_AH1") (pintype "bidirectional"))
      (node (ref "AB07") (pin "AH1") (pinfunction "P$2_AH1") (pintype "bidirectional"))
      (node (ref "B12") (pin "V2") (pinfunction "OUT_V2") (pintype "output"))
    )
    (net (code "395") (name "~{MA03}") (class "Default")
      (node (ref "AB02") (pin "AJ1") (pinfunction "P$2_AJ1") (pintype "bidirectional"))
      (node (ref "AB03") (pin "AJ1") (pinfunction "P$2_AJ1") (pintype "bidirectional"))
      (node (ref "AB04") (pin "AJ1") (pinfunction "P$2_AJ1") (pintype "bidirectional"))
      (node (ref "AB05") (pin "AJ1") (pinfunction "P$2_AJ1") (pintype "bidirectional"))
      (node (ref "AB06") (pin "AJ1") (pinfunction "P$2_AJ1") (pintype "bidirectional"))
      (node (ref "AB07") (pin "AJ1") (pinfunction "P$2_AJ1") (pintype "bidirectional"))
      (node (ref "B13") (pin "E1") (pinfunction "OUT_E1") (pintype "output"))
    )
    (net (code "396") (name "~{MA04}") (class "Default")
      (node (ref "AB02") (pin "BD1") (pinfunction "P$2_BD1") (pintype "bidirectional"))
      (node (ref "AB03") (pin "BD1") (pinfunction "P$2_BD1") (pintype "bidirectional"))
      (node (ref "AB04") (pin "BD1") (pinfunction "P$2_BD1") (pintype "bidirectional"))
      (node (ref "AB05") (pin "BD1") (pinfunction "P$2_BD1") (pintype "bidirectional"))
      (node (ref "AB06") (pin "BD1") (pinfunction "P$2_BD1") (pintype "bidirectional"))
      (node (ref "AB07") (pin "BD1") (pinfunction "P$2_BD1") (pintype "bidirectional"))
      (node (ref "B13") (pin "L1") (pinfunction "OUT_L1") (pintype "output"))
    )
    (net (code "397") (name "~{MA05}") (class "Default")
      (node (ref "AB02") (pin "BE1") (pinfunction "P$2_BE1") (pintype "bidirectional"))
      (node (ref "AB03") (pin "BE1") (pinfunction "P$2_BE1") (pintype "bidirectional"))
      (node (ref "AB04") (pin "BE1") (pinfunction "P$2_BE1") (pintype "bidirectional"))
      (node (ref "AB05") (pin "BE1") (pinfunction "P$2_BE1") (pintype "bidirectional"))
      (node (ref "AB06") (pin "BE1") (pinfunction "P$2_BE1") (pintype "bidirectional"))
      (node (ref "AB07") (pin "BE1") (pinfunction "P$2_BE1") (pintype "bidirectional"))
      (node (ref "B13") (pin "S1") (pinfunction "OUT_S1") (pintype "output"))
    )
    (net (code "398") (name "~{MA06}") (class "Default")
      (node (ref "AB02") (pin "BH1") (pinfunction "P$2_BH1") (pintype "bidirectional"))
      (node (ref "AB03") (pin "BH1") (pinfunction "P$2_BH1") (pintype "bidirectional"))
      (node (ref "AB04") (pin "BH1") (pinfunction "P$2_BH1") (pintype "bidirectional"))
      (node (ref "AB05") (pin "BH1") (pinfunction "P$2_BH1") (pintype "bidirectional"))
      (node (ref "AB06") (pin "BH1") (pinfunction "P$2_BH1") (pintype "bidirectional"))
      (node (ref "AB07") (pin "BH1") (pinfunction "P$2_BH1") (pintype "bidirectional"))
      (node (ref "B13") (pin "J2") (pinfunction "OUT_J2") (pintype "output"))
    )
    (net (code "399") (name "~{MA07}") (class "Default")
      (node (ref "AB02") (pin "BJ1") (pinfunction "P$2_BJ1") (pintype "bidirectional"))
      (node (ref "AB03") (pin "BJ1") (pinfunction "P$2_BJ1") (pintype "bidirectional"))
      (node (ref "AB04") (pin "BJ1") (pinfunction "P$2_BJ1") (pintype "bidirectional"))
      (node (ref "AB05") (pin "BJ1") (pinfunction "P$2_BJ1") (pintype "bidirectional"))
      (node (ref "AB06") (pin "BJ1") (pinfunction "P$2_BJ1") (pintype "bidirectional"))
      (node (ref "AB07") (pin "BJ1") (pinfunction "P$2_BJ1") (pintype "bidirectional"))
      (node (ref "B13") (pin "P2") (pinfunction "OUT_P2") (pintype "output"))
    )
    (net (code "400") (name "~{MA08}") (class "Default")
      (node (ref "B13") (pin "V2") (pinfunction "OUT_V2") (pintype "output"))
      (node (ref "CD02") (pin "BD1") (pinfunction "P$2_BD1") (pintype "bidirectional"))
      (node (ref "CD03") (pin "BD1") (pinfunction "P$2_BD1") (pintype "bidirectional"))
      (node (ref "CD04") (pin "BD1") (pinfunction "P$2_BD1") (pintype "bidirectional"))
      (node (ref "CD05") (pin "BD1") (pinfunction "P$2_BD1") (pintype "bidirectional"))
      (node (ref "CD06") (pin "BD1") (pinfunction "P$2_BD1") (pintype "bidirectional"))
      (node (ref "CD07") (pin "BD1") (pinfunction "P$2_BD1") (pintype "bidirectional"))
    )
    (net (code "401") (name "~{MA09}") (class "Default")
      (node (ref "B14") (pin "E1") (pinfunction "OUT_E1") (pintype "output"))
      (node (ref "CD02") (pin "BE1") (pinfunction "P$2_BE1") (pintype "bidirectional"))
      (node (ref "CD03") (pin "BE1") (pinfunction "P$2_BE1") (pintype "bidirectional"))
      (node (ref "CD04") (pin "BE1") (pinfunction "P$2_BE1") (pintype "bidirectional"))
      (node (ref "CD05") (pin "BE1") (pinfunction "P$2_BE1") (pintype "bidirectional"))
      (node (ref "CD06") (pin "BE1") (pinfunction "P$2_BE1") (pintype "bidirectional"))
      (node (ref "CD07") (pin "BE1") (pinfunction "P$2_BE1") (pintype "bidirectional"))
    )
    (net (code "402") (name "~{MA10}") (class "Default")
      (node (ref "B14") (pin "L1") (pinfunction "OUT_L1") (pintype "output"))
      (node (ref "CD02") (pin "BH1") (pinfunction "P$2_BH1") (pintype "bidirectional"))
      (node (ref "CD03") (pin "BH1") (pinfunction "P$2_BH1") (pintype "bidirectional"))
      (node (ref "CD04") (pin "BH1") (pinfunction "P$2_BH1") (pintype "bidirectional"))
      (node (ref "CD05") (pin "BH1") (pinfunction "P$2_BH1") (pintype "bidirectional"))
      (node (ref "CD06") (pin "BH1") (pinfunction "P$2_BH1") (pintype "bidirectional"))
      (node (ref "CD07") (pin "BH1") (pinfunction "P$2_BH1") (pintype "bidirectional"))
    )
    (net (code "403") (name "~{MA11}") (class "Default")
      (node (ref "B14") (pin "S1") (pinfunction "OUT_S1") (pintype "output"))
      (node (ref "CD02") (pin "BJ1") (pinfunction "P$2_BJ1") (pintype "bidirectional"))
      (node (ref "CD03") (pin "BJ1") (pinfunction "P$2_BJ1") (pintype "bidirectional"))
      (node (ref "CD04") (pin "BJ1") (pinfunction "P$2_BJ1") (pintype "bidirectional"))
      (node (ref "CD05") (pin "BJ1") (pinfunction "P$2_BJ1") (pintype "bidirectional"))
      (node (ref "CD06") (pin "BJ1") (pinfunction "P$2_BJ1") (pintype "bidirectional"))
      (node (ref "CD07") (pin "BJ1") (pinfunction "P$2_BJ1") (pintype "bidirectional"))
    )
    (net (code "404") (name "~{MB_INCR}") (class "Default")
      (node (ref "A19") (pin "T2") (pinfunction "P$2_T2") (pintype "bidirectional"))
      (node (ref "B19") (pin "T2") (pinfunction "P$2_T2") (pintype "bidirectional"))
    )
    (net (code "405") (name "~{MD00}") (class "Default")
      (node (ref "AB02") (pin "AK1") (pinfunction "P$2_AK1") (pintype "bidirectional"))
      (node (ref "AB03") (pin "AK1") (pinfunction "P$2_AK1") (pintype "bidirectional"))
      (node (ref "AB04") (pin "AK1") (pinfunction "P$2_AK1") (pintype "bidirectional"))
      (node (ref "AB05") (pin "AK1") (pinfunction "P$2_AK1") (pintype "bidirectional"))
      (node (ref "AB06") (pin "AK1") (pinfunction "P$2_AK1") (pintype "bidirectional"))
      (node (ref "AB07") (pin "AK1") (pinfunction "P$2_AK1") (pintype "bidirectional"))
    )
    (net (code "406") (name "~{MD01}") (class "Default")
      (node (ref "AB02") (pin "AL1") (pinfunction "P$2_AL1") (pintype "bidirectional"))
      (node (ref "AB03") (pin "AL1") (pinfunction "P$2_AL1") (pintype "bidirectional"))
      (node (ref "AB04") (pin "AL1") (pinfunction "P$2_AL1") (pintype "bidirectional"))
      (node (ref "AB05") (pin "AL1") (pinfunction "P$2_AL1") (pintype "bidirectional"))
      (node (ref "AB06") (pin "AL1") (pinfunction "P$2_AL1") (pintype "bidirectional"))
      (node (ref "AB07") (pin "AL1") (pinfunction "P$2_AL1") (pintype "bidirectional"))
    )
    (net (code "407") (name "~{MD02}") (class "Default")
      (node (ref "AB02") (pin "AM1") (pinfunction "P$2_AM1") (pintype "bidirectional"))
      (node (ref "AB03") (pin "AM1") (pinfunction "P$2_AM1") (pintype "bidirectional"))
      (node (ref "AB04") (pin "AM1") (pinfunction "P$2_AM1") (pintype "bidirectional"))
      (node (ref "AB05") (pin "AM1") (pinfunction "P$2_AM1") (pintype "bidirectional"))
      (node (ref "AB06") (pin "AM1") (pinfunction "P$2_AM1") (pintype "bidirectional"))
      (node (ref "AB07") (pin "AM1") (pinfunction "P$2_AM1") (pintype "bidirectional"))
    )
    (net (code "408") (name "~{MD03}") (class "Default")
      (node (ref "AB02") (pin "AP1") (pinfunction "P$2_AP1") (pintype "bidirectional"))
      (node (ref "AB03") (pin "AP1") (pinfunction "P$2_AP1") (pintype "bidirectional"))
      (node (ref "AB04") (pin "AP1") (pinfunction "P$2_AP1") (pintype "bidirectional"))
      (node (ref "AB05") (pin "AP1") (pinfunction "P$2_AP1") (pintype "bidirectional"))
      (node (ref "AB06") (pin "AP1") (pinfunction "P$2_AP1") (pintype "bidirectional"))
      (node (ref "AB07") (pin "AP1") (pinfunction "P$2_AP1") (pintype "bidirectional"))
    )
    (net (code "409") (name "~{MD04}") (class "Default")
      (node (ref "AB02") (pin "BK1") (pinfunction "P$2_BK1") (pintype "bidirectional"))
      (node (ref "AB03") (pin "BK1") (pinfunction "P$2_BK1") (pintype "bidirectional"))
      (node (ref "AB04") (pin "BK1") (pinfunction "P$2_BK1") (pintype "bidirectional"))
      (node (ref "AB05") (pin "BK1") (pinfunction "P$2_BK1") (pintype "bidirectional"))
      (node (ref "AB06") (pin "BK1") (pinfunction "P$2_BK1") (pintype "bidirectional"))
      (node (ref "AB07") (pin "BK1") (pinfunction "P$2_BK1") (pintype "bidirectional"))
    )
    (net (code "410") (name "~{MD05}") (class "Default")
      (node (ref "AB02") (pin "BL1") (pinfunction "P$2_BL1") (pintype "bidirectional"))
      (node (ref "AB03") (pin "BL1") (pinfunction "P$2_BL1") (pintype "bidirectional"))
      (node (ref "AB04") (pin "BL1") (pinfunction "P$2_BL1") (pintype "bidirectional"))
      (node (ref "AB05") (pin "BL1") (pinfunction "P$2_BL1") (pintype "bidirectional"))
      (node (ref "AB06") (pin "BL1") (pinfunction "P$2_BL1") (pintype "bidirectional"))
      (node (ref "AB07") (pin "BL1") (pinfunction "P$2_BL1") (pintype "bidirectional"))
    )
    (net (code "411") (name "~{MD06}") (class "Default")
      (node (ref "AB02") (pin "BM1") (pinfunction "P$2_BM1") (pintype "bidirectional"))
      (node (ref "AB03") (pin "BM1") (pinfunction "P$2_BM1") (pintype "bidirectional"))
      (node (ref "AB04") (pin "BM1") (pinfunction "P$2_BM1") (pintype "bidirectional"))
      (node (ref "AB05") (pin "BM1") (pinfunction "P$2_BM1") (pintype "bidirectional"))
      (node (ref "AB06") (pin "BM1") (pinfunction "P$2_BM1") (pintype "bidirectional"))
      (node (ref "AB07") (pin "BM1") (pinfunction "P$2_BM1") (pintype "bidirectional"))
    )
    (net (code "412") (name "~{MD07}") (class "Default")
      (node (ref "AB02") (pin "BP1") (pinfunction "P$2_BP1") (pintype "bidirectional"))
      (node (ref "AB03") (pin "BP1") (pinfunction "P$2_BP1") (pintype "bidirectional"))
      (node (ref "AB04") (pin "BP1") (pinfunction "P$2_BP1") (pintype "bidirectional"))
      (node (ref "AB05") (pin "BP1") (pinfunction "P$2_BP1") (pintype "bidirectional"))
      (node (ref "AB06") (pin "BP1") (pinfunction "P$2_BP1") (pintype "bidirectional"))
      (node (ref "AB07") (pin "BP1") (pinfunction "P$2_BP1") (pintype "bidirectional"))
    )
    (net (code "413") (name "~{MD08}") (class "Default")
      (node (ref "CD02") (pin "BK1") (pinfunction "P$2_BK1") (pintype "bidirectional"))
      (node (ref "CD03") (pin "BK1") (pinfunction "P$2_BK1") (pintype "bidirectional"))
      (node (ref "CD04") (pin "BK1") (pinfunction "P$2_BK1") (pintype "bidirectional"))
      (node (ref "CD05") (pin "BK1") (pinfunction "P$2_BK1") (pintype "bidirectional"))
      (node (ref "CD06") (pin "BK1") (pinfunction "P$2_BK1") (pintype "bidirectional"))
      (node (ref "CD07") (pin "BK1") (pinfunction "P$2_BK1") (pintype "bidirectional"))
    )
    (net (code "414") (name "~{MD09}") (class "Default")
      (node (ref "CD02") (pin "BL1") (pinfunction "P$2_BL1") (pintype "bidirectional"))
      (node (ref "CD03") (pin "BL1") (pinfunction "P$2_BL1") (pintype "bidirectional"))
      (node (ref "CD04") (pin "BL1") (pinfunction "P$2_BL1") (pintype "bidirectional"))
      (node (ref "CD05") (pin "BL1") (pinfunction "P$2_BL1") (pintype "bidirectional"))
      (node (ref "CD06") (pin "BL1") (pinfunction "P$2_BL1") (pintype "bidirectional"))
      (node (ref "CD07") (pin "BL1") (pinfunction "P$2_BL1") (pintype "bidirectional"))
    )
    (net (code "415") (name "~{MD10}") (class "Default")
      (node (ref "CD02") (pin "BM1") (pinfunction "P$2_BM1") (pintype "bidirectional"))
      (node (ref "CD03") (pin "BM1") (pinfunction "P$2_BM1") (pintype "bidirectional"))
      (node (ref "CD04") (pin "BM1") (pinfunction "P$2_BM1") (pintype "bidirectional"))
      (node (ref "CD05") (pin "BM1") (pinfunction "P$2_BM1") (pintype "bidirectional"))
      (node (ref "CD06") (pin "BM1") (pinfunction "P$2_BM1") (pintype "bidirectional"))
      (node (ref "CD07") (pin "BM1") (pinfunction "P$2_BM1") (pintype "bidirectional"))
    )
    (net (code "416") (name "~{MD11}") (class "Default")
      (node (ref "CD02") (pin "BP1") (pinfunction "P$2_BP1") (pintype "bidirectional"))
      (node (ref "CD03") (pin "BP1") (pinfunction "P$2_BP1") (pintype "bidirectional"))
      (node (ref "CD04") (pin "BP1") (pinfunction "P$2_BP1") (pintype "bidirectional"))
      (node (ref "CD05") (pin "BP1") (pinfunction "P$2_BP1") (pintype "bidirectional"))
      (node (ref "CD06") (pin "BP1") (pinfunction "P$2_BP1") (pintype "bidirectional"))
      (node (ref "CD07") (pin "BP1") (pinfunction "P$2_BP1") (pintype "bidirectional"))
    )
    (net (code "417") (name "~{MEM_DONE}") (class "Default")
      (node (ref "B15") (pin "V2") (pinfunction "E_V2") (pintype "open_collector"))
      (node (ref "C20") (pin "V2") (pinfunction "P$2_V2") (pintype "bidirectional"))
      (node (ref "D20") (pin "V2") (pinfunction "P$2_V2") (pintype "bidirectional"))
    )
    (net (code "418") (name "~{MEM_START}") (class "Default")
      (node (ref "C13") (pin "H2") (pinfunction "IN1_H2") (pintype "input"))
      (node (ref "D08") (pin "T2") (pinfunction "OUT_T2") (pintype "output"))
      (node (ref "D14") (pin "D1") (pinfunction "S_D1") (pintype "input"))
    )
    (net (code "419") (name "~{RDF}") (class "Default")
      (node (ref "A08") (pin "P2") (pinfunction "OUT_P2") (pintype "output"))
      (node (ref "A09") (pin "C1") (pinfunction "IN_C1") (pintype "input"))
      (node (ref "A14") (pin "J1") (pinfunction "C_J1") (pintype "input"))
    )
    (net (code "420") (name "~{READ}") (class "Default")
      (node (ref "AB02") (pin "AK2") (pinfunction "P$2_AK2") (pintype "bidirectional"))
      (node (ref "AB03") (pin "AK2") (pinfunction "P$2_AK2") (pintype "bidirectional"))
      (node (ref "AB04") (pin "AK2") (pinfunction "P$2_AK2") (pintype "bidirectional"))
      (node (ref "AB05") (pin "AK2") (pinfunction "P$2_AK2") (pintype "bidirectional"))
      (node (ref "AB06") (pin "AK2") (pinfunction "P$2_AK2") (pintype "bidirectional"))
      (node (ref "AB07") (pin "AK2") (pinfunction "P$2_AK2") (pintype "bidirectional"))
      (node (ref "D14") (pin "F1") (pinfunction "0_F1") (pintype "output"))
    )
    (net (code "421") (name "~{RET}") (class "Default")
      (node (ref "C08") (pin "D1") (pinfunction "IN4_D1") (pintype "input"))
      (node (ref "D14") (pin "J2") (pinfunction "0_J2") (pintype "output"))
    )
    (net (code "422") (name "~{RIB}") (class "Default")
      (node (ref "A08") (pin "S1") (pinfunction "OUT_S1") (pintype "output"))
      (node (ref "A14") (pin "F2") (pinfunction "C_F2") (pintype "input"))
      (node (ref "A14") (pin "M2") (pinfunction "C_M2") (pintype "input"))
      (node (ref "A14") (pin "T2") (pinfunction "C_T2") (pintype "input"))
    )
    (net (code "423") (name "~{RIF}") (class "Default")
      (node (ref "A08") (pin "J2") (pinfunction "OUT_J2") (pintype "output"))
      (node (ref "A09") (pin "A1") (pinfunction "IN_A1") (pintype "input"))
      (node (ref "A14") (pin "C1") (pinfunction "C_C1") (pintype "input"))
    )
    (net (code "424") (name "~{RMF}") (class "Default")
      (node (ref "A08") (pin "V2") (pinfunction "OUT_V2") (pintype "output"))
      (node (ref "C13") (pin "P1") (pinfunction "IN1_P1") (pintype "input"))
      (node (ref "C13") (pin "P2") (pinfunction "IN1_P2") (pintype "input"))
    )
    (net (code "425") (name "~{SELECT}") (class "Default")
      (node (ref "B15") (pin "T2") (pinfunction "C_T2") (pintype "input"))
      (node (ref "D12") (pin "J2") (pinfunction "0_J2") (pintype "output"))
    )
    (net (code "426") (name "~{SET_DF0}") (class "Default")
      (node (ref "C12") (pin "N2") (pinfunction "OUT_N2") (pintype "output"))
      (node (ref "D12") (pin "N2") (pinfunction "S_N2") (pintype "input"))
    )
    (net (code "427") (name "~{SET_DF1}") (class "Default")
      (node (ref "C12") (pin "S2") (pinfunction "OUT_S2") (pintype "output"))
      (node (ref "D12") (pin "R1") (pinfunction "S_R1") (pintype "input"))
    )
    (net (code "428") (name "~{SET_DF2}") (class "Default")
      (node (ref "C13") (pin "F2") (pinfunction "OUT_F2") (pintype "output"))
      (node (ref "D12") (pin "U2") (pinfunction "S_U2") (pintype "input"))
    )
    (net (code "429") (name "~{SET_F0}") (class "Default")
      (node (ref "C12") (pin "N1") (pinfunction "OUT_N1") (pintype "output"))
      (node (ref "C15") (pin "D1") (pinfunction "S_D1") (pintype "input"))
      (node (ref "D10") (pin "D1") (pinfunction "S_D1") (pintype "input"))
      (node (ref "D10") (pin "N2") (pinfunction "S_N2") (pintype "input"))
      (node (ref "D11") (pin "N2") (pinfunction "S_N2") (pintype "input"))
    )
    (net (code "430") (name "~{SET_F1}") (class "Default")
      (node (ref "C12") (pin "S1") (pinfunction "OUT_S1") (pintype "output"))
      (node (ref "C15") (pin "F2") (pinfunction "S_F2") (pintype "input"))
      (node (ref "D10") (pin "F2") (pinfunction "S_F2") (pintype "input"))
      (node (ref "D10") (pin "R1") (pinfunction "S_R1") (pintype "input"))
      (node (ref "D11") (pin "R1") (pinfunction "S_R1") (pintype "input"))
    )
    (net (code "431") (name "~{SET_F2}") (class "Default")
      (node (ref "C12") (pin "V2") (pinfunction "OUT_V2") (pintype "output"))
      (node (ref "C15") (pin "K1") (pinfunction "S_K1") (pintype "input"))
      (node (ref "D10") (pin "K1") (pinfunction "S_K1") (pintype "input"))
      (node (ref "D10") (pin "U2") (pinfunction "S_U2") (pintype "input"))
      (node (ref "D11") (pin "U2") (pinfunction "S_U2") (pintype "input"))
    )
    (net (code "432") (name "~{SET_INT}") (class "Default")
      (node (ref "D08") (pin "K1") (pinfunction "OUT_K1") (pintype "output"))
      (node (ref "D12") (pin "D1") (pinfunction "S_D1") (pintype "input"))
    )
    (net (code "433") (name "~{SF0}") (class "Default")
      (node (ref "A14") (pin "D2") (pinfunction "A_D2") (pintype "input"))
      (node (ref "D13") (pin "F1") (pinfunction "0_F1") (pintype "output"))
    )
    (net (code "434") (name "~{SF1}") (class "Default")
      (node (ref "A14") (pin "E2") (pinfunction "B_E2") (pintype "input"))
      (node (ref "D13") (pin "J2") (pinfunction "0_J2") (pintype "output"))
    )
    (net (code "435") (name "~{SF2}") (class "Default")
      (node (ref "A14") (pin "K2") (pinfunction "A_K2") (pintype "input"))
      (node (ref "D13") (pin "M1") (pinfunction "0_M1") (pintype "output"))
    )
    (net (code "436") (name "~{SF3}") (class "Default")
      (node (ref "A14") (pin "L2") (pinfunction "B_L2") (pintype "input"))
      (node (ref "D13") (pin "R2") (pinfunction "0_R2") (pintype "output"))
    )
    (net (code "437") (name "~{SF4}") (class "Default")
      (node (ref "A14") (pin "R2") (pinfunction "A_R2") (pintype "input"))
      (node (ref "D13") (pin "U1") (pinfunction "0_U1") (pintype "output"))
    )
    (net (code "438") (name "~{SF5}") (class "Default")
      (node (ref "A14") (pin "S2") (pinfunction "B_S2") (pintype "input"))
      (node (ref "D13") (pin "V1") (pinfunction "0_V1") (pintype "output"))
    )
    (net (code "439") (name "~{SKIP_BUS}") (class "Default")
      (node (ref "A18") (pin "K2") (pinfunction "P$2_K2") (pintype "bidirectional"))
      (node (ref "B18") (pin "K2") (pinfunction "P$2_K2") (pintype "bidirectional"))
    )
    (net (code "440") (name "~{SORC}") (class "Default")
      (node (ref "C08") (pin "K1") (pinfunction "IN4_K1") (pintype "input"))
      (node (ref "D14") (pin "M1") (pinfunction "0_M1") (pintype "output"))
    )
    (net (code "441") (name "~{SP_CYC_NEXT}") (class "Default")
      (node (ref "C09") (pin "F1") (pinfunction "IN2_F1") (pintype "input"))
      (node (ref "C18") (pin "D1") (pinfunction "P$2_D1") (pintype "bidirectional"))
      (node (ref "D18") (pin "D1") (pinfunction "P$2_D1") (pintype "bidirectional"))
    )
    (net (code "442") (name "~{STROBE}") (class "Default")
      (node (ref "B15") (pin "U2") (pinfunction "D_U2") (pintype "open_collector"))
      (node (ref "C13") (pin "U1") (pinfunction "P$1_U1") (pintype "passive"))
      (node (ref "C20") (pin "S2") (pinfunction "P$2_S2") (pintype "bidirectional"))
      (node (ref "D20") (pin "S2") (pinfunction "P$2_S2") (pintype "bidirectional"))
    )
    (net (code "443") (name "~{STROB}") (class "Default")
      (node (ref "C08") (pin "N2") (pinfunction "IN4_N2") (pintype "input"))
      (node (ref "D14") (pin "R2") (pinfunction "0_R2") (pintype "output"))
    )
    (net (code "444") (name "~{WC_OVFL}") (class "Default")
      (node (ref "A20") (pin "P2") (pinfunction "P$2_P2") (pintype "bidirectional"))
      (node (ref "B20") (pin "P2") (pinfunction "P$2_P2") (pintype "bidirectional"))
    )
    (net (code "445") (name "~{WRT}") (class "Default")
      (node (ref "C08") (pin "H2") (pinfunction "IN4_H2") (pintype "input"))
      (node (ref "D14") (pin "U1") (pinfunction "0_U1") (pintype "output"))
    )
  )
)
